# untitled.net
KiCad netlist of a schematic drawn in EAGLE
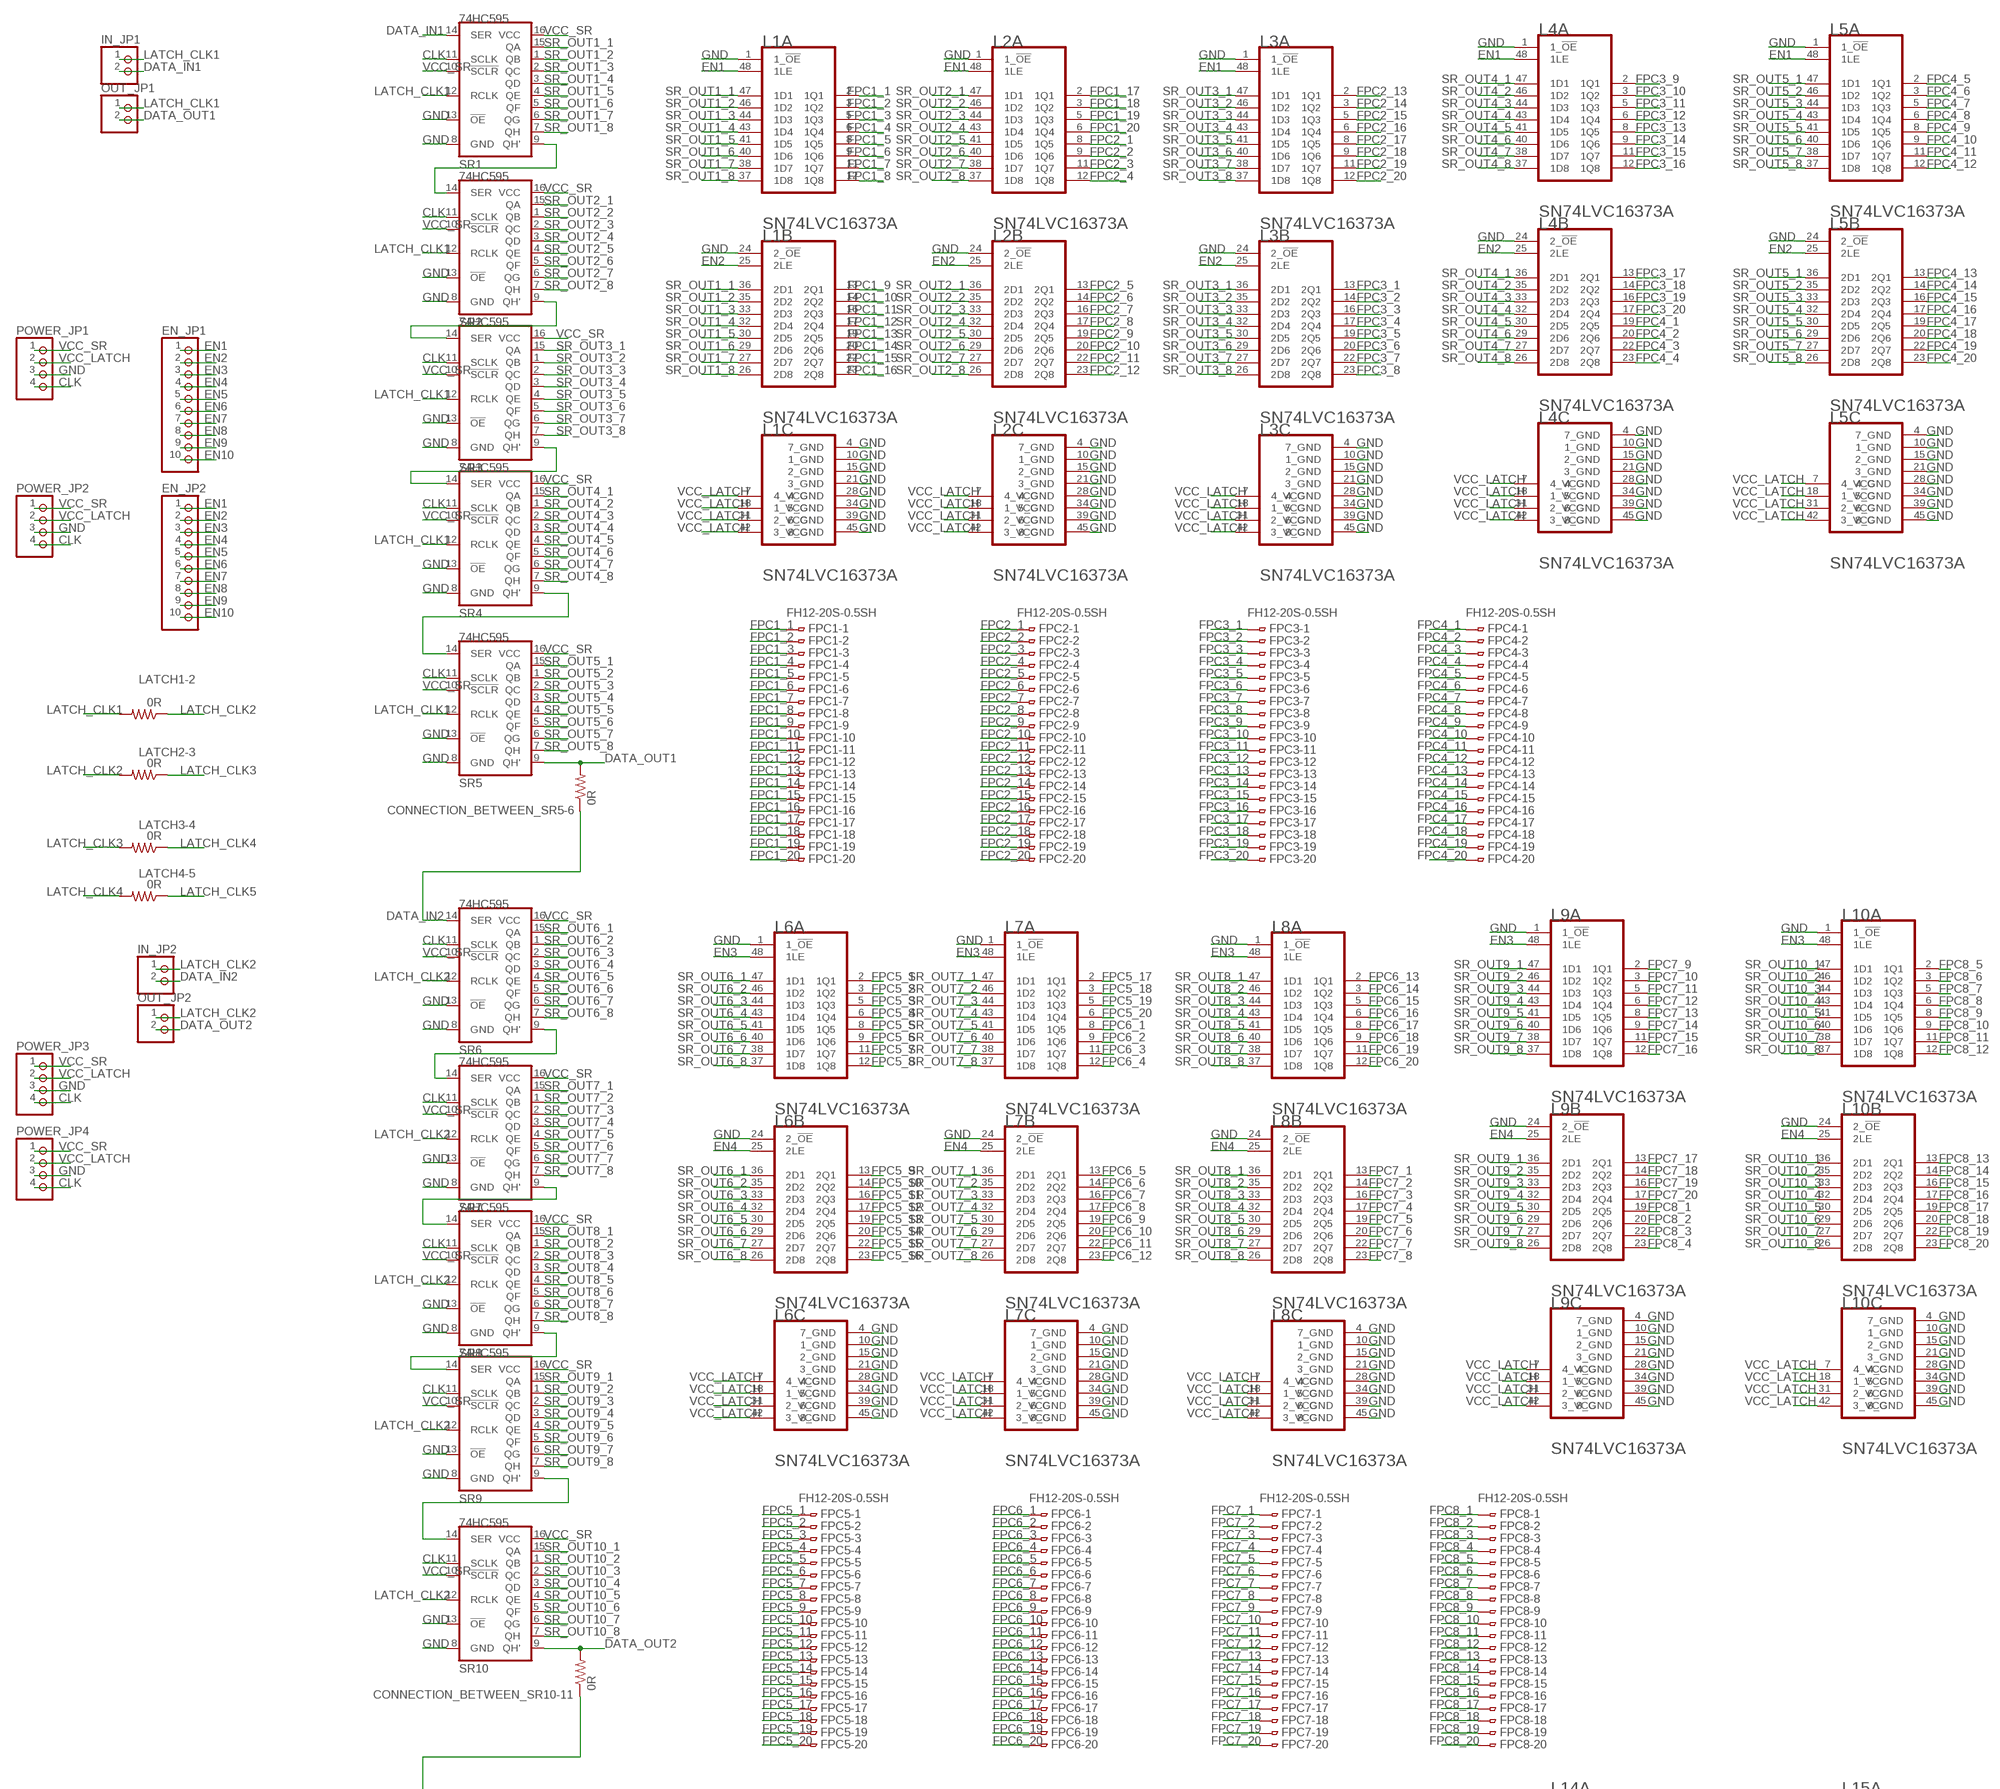
[diagram p0: schematic, sheet 1, part 1 of 3]
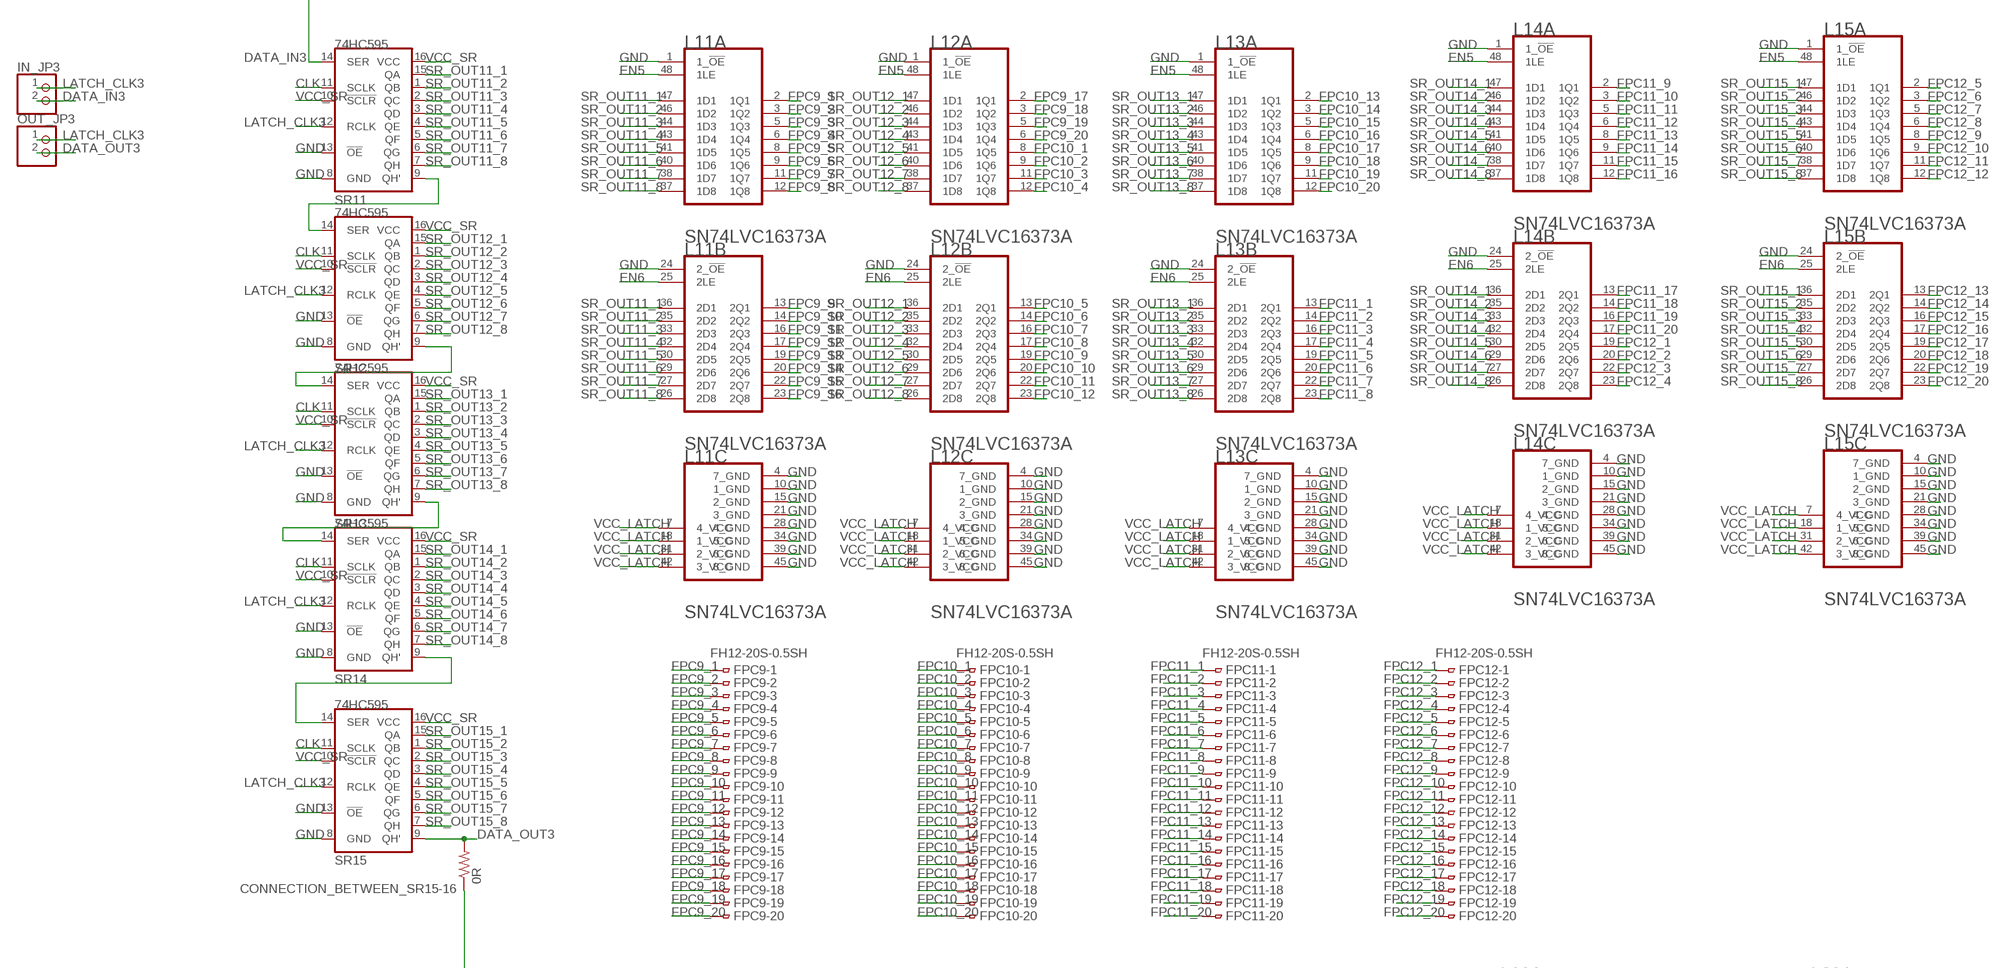
[diagram p1: schematic, sheet 1, part 2 of 3]
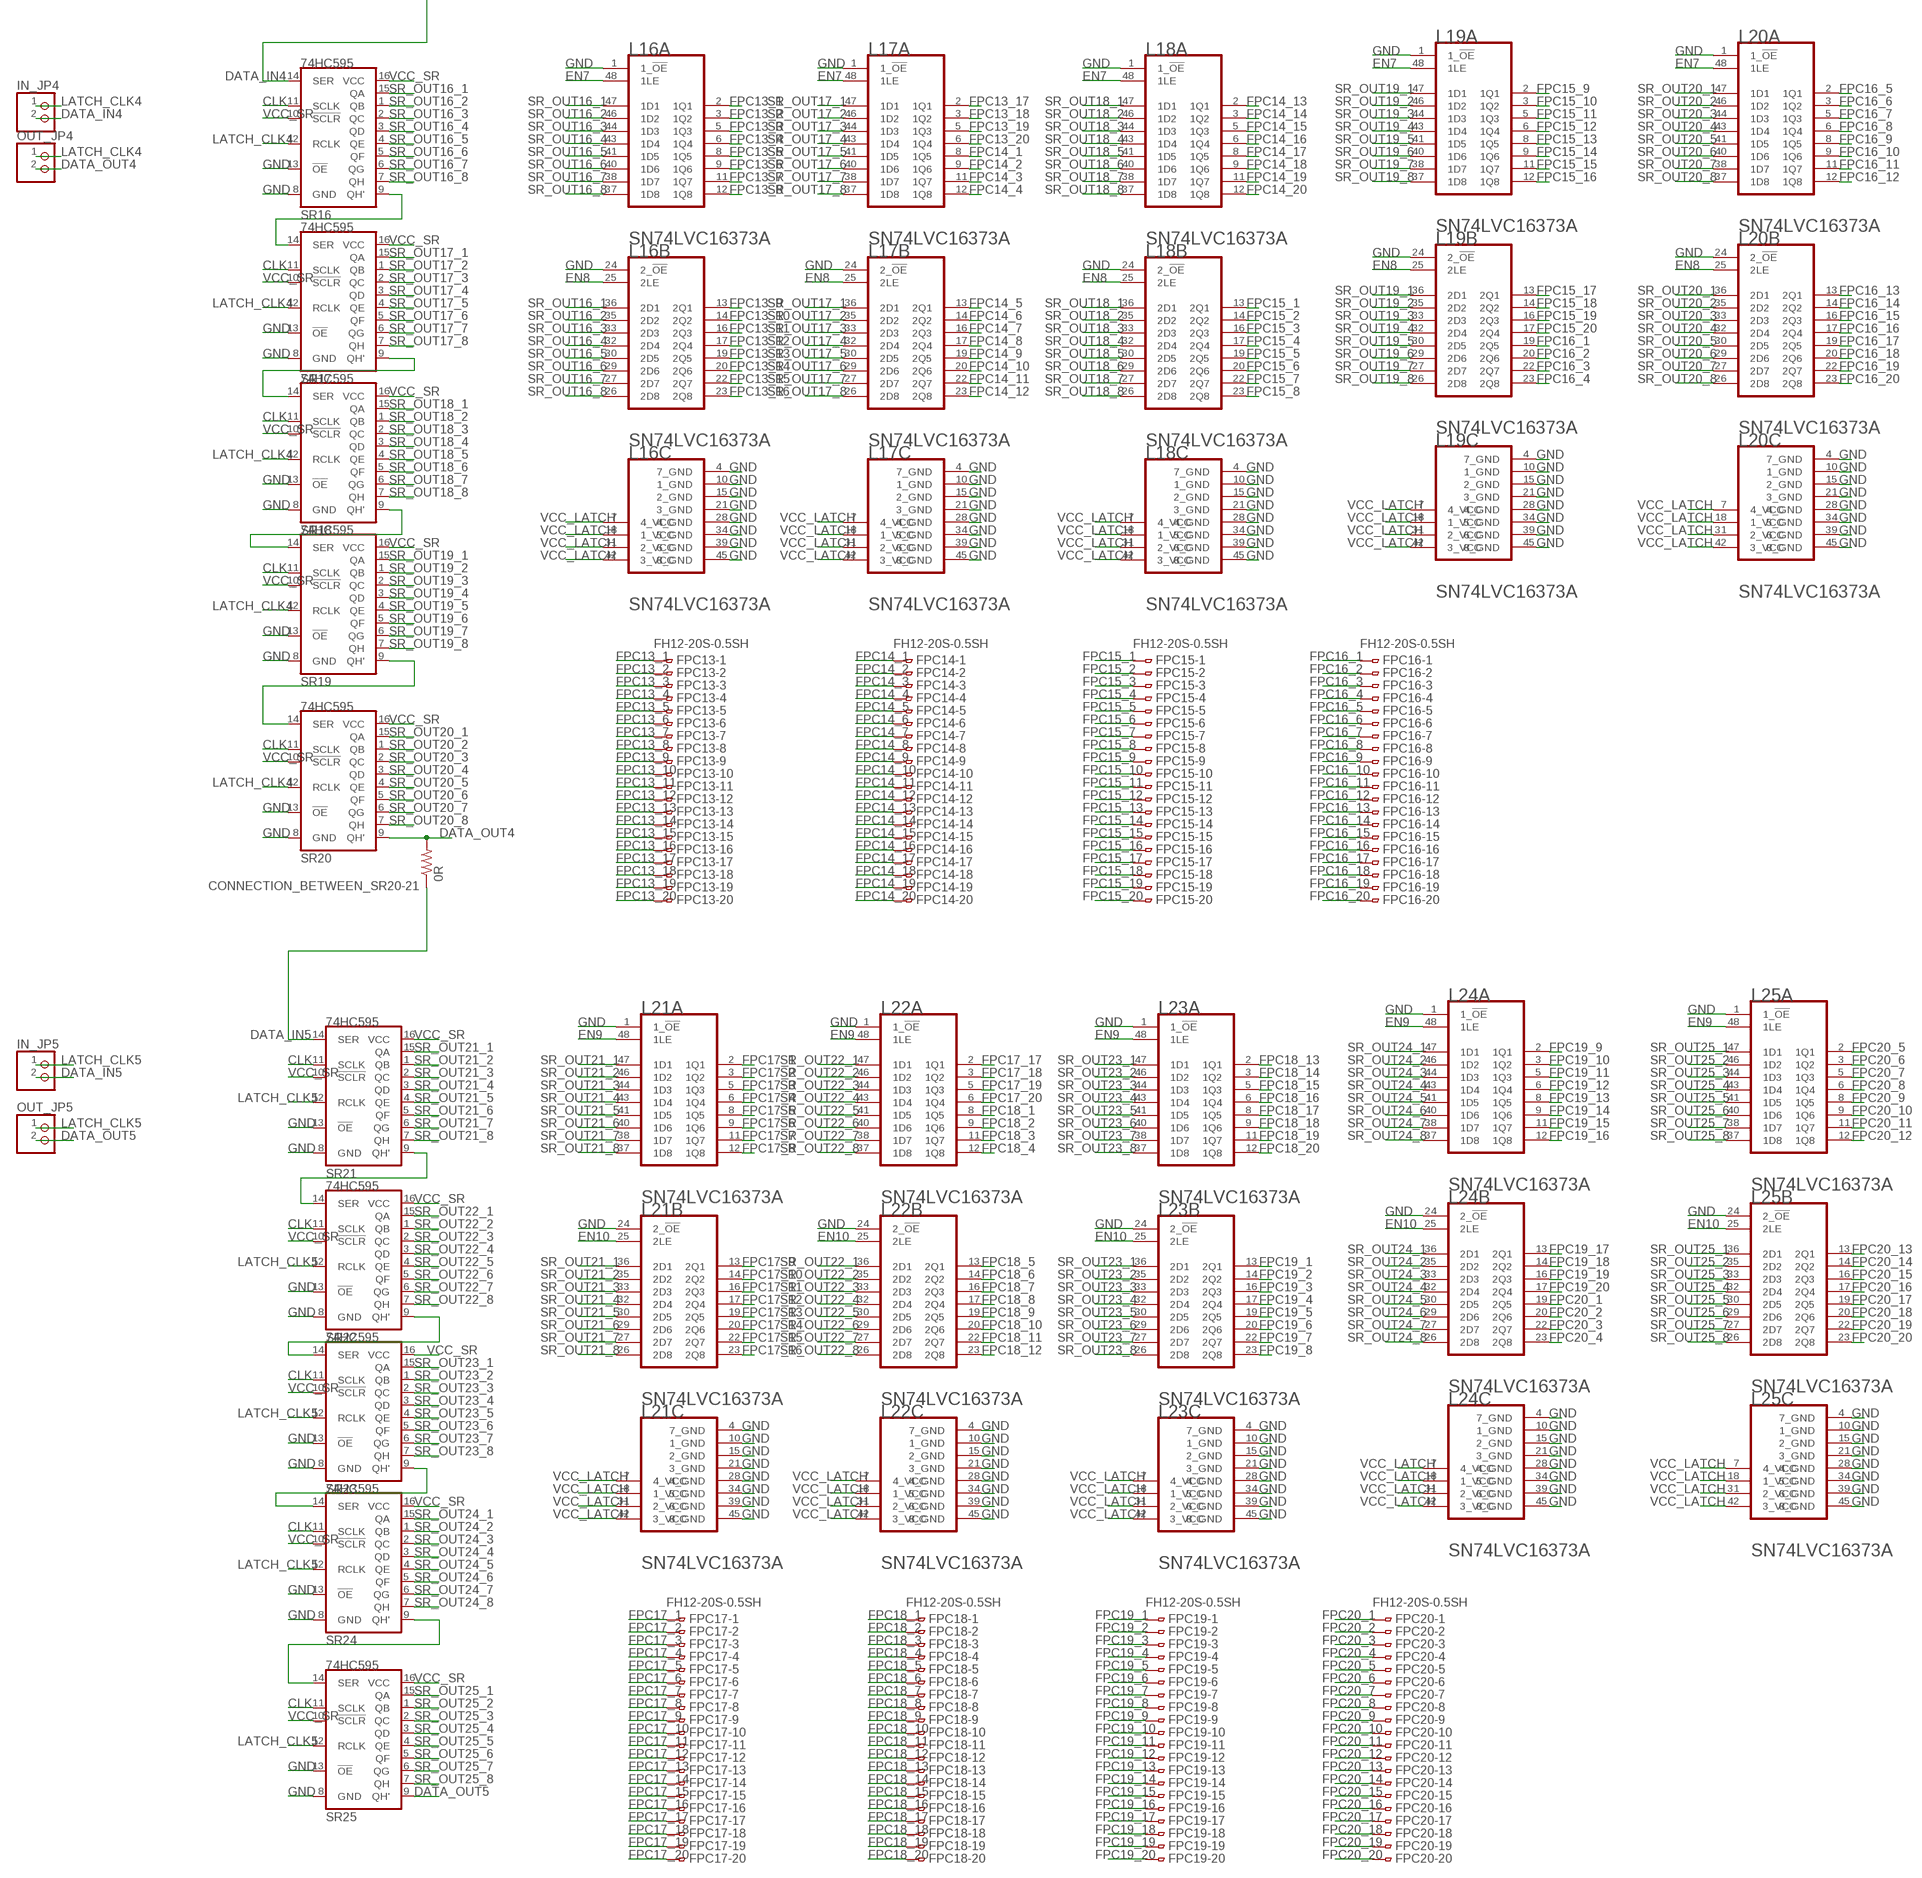
[diagram p2: schematic, sheet 1, part 3 of 3]

(export (version "E")
  (design (tool "Eeschema 10.0.6"))
  (components
    (comp (ref "CONNECTION_BETWEEN_SR5-6")
      (value "0R")
      (footprint "eagle-import:M0805")
      (libsource (lib "eagle-import") (part "R-US_M0805"))
    )
    (comp (ref "CONNECTION_BETWEEN_SR10-11")
      (value "0R")
      (footprint "eagle-import:M0805")
      (libsource (lib "eagle-import") (part "R-US_M0805"))
    )
    (comp (ref "CONNECTION_BETWEEN_SR15-16")
      (value "0R")
      (footprint "eagle-import:M0805")
      (libsource (lib "eagle-import") (part "R-US_M0805"))
    )
    (comp (ref "CONNECTION_BETWEEN_SR20-21")
      (value "0R")
      (footprint "eagle-import:M0805")
      (libsource (lib "eagle-import") (part "R-US_M0805"))
    )
    (comp (ref "EN_JP1")
      (value "PINHD-1X10")
      (footprint "eagle-import:1X10")
      (libsource (lib "eagle-import") (part "PINHD-1X10"))
    )
    (comp (ref "EN_JP2")
      (value "PINHD-1X10")
      (footprint "eagle-import:1X10")
      (libsource (lib "eagle-import") (part "PINHD-1X10"))
    )
    (comp (ref "FPC1")
      (value "FH12-20S-0.5SH")
      (footprint "eagle-import:FH12-20S-0.5SH")
      (fields (field (name "MPN") "FH12-20S-0.5SH(55)"))
      (libsource (lib "eagle-import") (part "FH12-20S-0.5SH"))
    )
    (comp (ref "FPC2")
      (value "FH12-20S-0.5SH")
      (footprint "eagle-import:FH12-20S-0.5SH")
      (fields (field (name "MPN") "FH12-20S-0.5SH(55)"))
      (libsource (lib "eagle-import") (part "FH12-20S-0.5SH"))
    )
    (comp (ref "FPC3")
      (value "FH12-20S-0.5SH")
      (footprint "eagle-import:FH12-20S-0.5SH")
      (fields (field (name "MPN") "FH12-20S-0.5SH(55)"))
      (libsource (lib "eagle-import") (part "FH12-20S-0.5SH"))
    )
    (comp (ref "FPC4")
      (value "FH12-20S-0.5SH")
      (footprint "eagle-import:FH12-20S-0.5SH")
      (fields (field (name "MPN") "FH12-20S-0.5SH(55)"))
      (libsource (lib "eagle-import") (part "FH12-20S-0.5SH"))
    )
    (comp (ref "FPC5")
      (value "FH12-20S-0.5SH")
      (footprint "eagle-import:FH12-20S-0.5SH")
      (fields (field (name "MPN") "FH12-20S-0.5SH(55)"))
      (libsource (lib "eagle-import") (part "FH12-20S-0.5SH"))
    )
    (comp (ref "FPC6")
      (value "FH12-20S-0.5SH")
      (footprint "eagle-import:FH12-20S-0.5SH")
      (fields (field (name "MPN") "FH12-20S-0.5SH(55)"))
      (libsource (lib "eagle-import") (part "FH12-20S-0.5SH"))
    )
    (comp (ref "FPC7")
      (value "FH12-20S-0.5SH")
      (footprint "eagle-import:FH12-20S-0.5SH")
      (fields (field (name "MPN") "FH12-20S-0.5SH(55)"))
      (libsource (lib "eagle-import") (part "FH12-20S-0.5SH"))
    )
    (comp (ref "FPC8")
      (value "FH12-20S-0.5SH")
      (footprint "eagle-import:FH12-20S-0.5SH")
      (fields (field (name "MPN") "FH12-20S-0.5SH(55)"))
      (libsource (lib "eagle-import") (part "FH12-20S-0.5SH"))
    )
    (comp (ref "FPC9")
      (value "FH12-20S-0.5SH")
      (footprint "eagle-import:FH12-20S-0.5SH")
      (fields (field (name "MPN") "FH12-20S-0.5SH(55)"))
      (libsource (lib "eagle-import") (part "FH12-20S-0.5SH"))
    )
    (comp (ref "FPC10")
      (value "FH12-20S-0.5SH")
      (footprint "eagle-import:FH12-20S-0.5SH")
      (fields (field (name "MPN") "FH12-20S-0.5SH(55)"))
      (libsource (lib "eagle-import") (part "FH12-20S-0.5SH"))
    )
    (comp (ref "FPC11")
      (value "FH12-20S-0.5SH")
      (footprint "eagle-import:FH12-20S-0.5SH")
      (fields (field (name "MPN") "FH12-20S-0.5SH(55)"))
      (libsource (lib "eagle-import") (part "FH12-20S-0.5SH"))
    )
    (comp (ref "FPC12")
      (value "FH12-20S-0.5SH")
      (footprint "eagle-import:FH12-20S-0.5SH")
      (fields (field (name "MPN") "FH12-20S-0.5SH(55)"))
      (libsource (lib "eagle-import") (part "FH12-20S-0.5SH"))
    )
    (comp (ref "FPC13")
      (value "FH12-20S-0.5SH")
      (footprint "eagle-import:FH12-20S-0.5SH")
      (fields (field (name "MPN") "FH12-20S-0.5SH(55)"))
      (libsource (lib "eagle-import") (part "FH12-20S-0.5SH"))
    )
    (comp (ref "FPC14")
      (value "FH12-20S-0.5SH")
      (footprint "eagle-import:FH12-20S-0.5SH")
      (fields (field (name "MPN") "FH12-20S-0.5SH(55)"))
      (libsource (lib "eagle-import") (part "FH12-20S-0.5SH"))
    )
    (comp (ref "FPC15")
      (value "FH12-20S-0.5SH")
      (footprint "eagle-import:FH12-20S-0.5SH")
      (fields (field (name "MPN") "FH12-20S-0.5SH(55)"))
      (libsource (lib "eagle-import") (part "FH12-20S-0.5SH"))
    )
    (comp (ref "FPC16")
      (value "FH12-20S-0.5SH")
      (footprint "eagle-import:FH12-20S-0.5SH")
      (fields (field (name "MPN") "FH12-20S-0.5SH(55)"))
      (libsource (lib "eagle-import") (part "FH12-20S-0.5SH"))
    )
    (comp (ref "FPC17")
      (value "FH12-20S-0.5SH")
      (footprint "eagle-import:FH12-20S-0.5SH")
      (fields (field (name "MPN") "FH12-20S-0.5SH(55)"))
      (libsource (lib "eagle-import") (part "FH12-20S-0.5SH"))
    )
    (comp (ref "FPC18")
      (value "FH12-20S-0.5SH")
      (footprint "eagle-import:FH12-20S-0.5SH")
      (fields (field (name "MPN") "FH12-20S-0.5SH(55)"))
      (libsource (lib "eagle-import") (part "FH12-20S-0.5SH"))
    )
    (comp (ref "FPC19")
      (value "FH12-20S-0.5SH")
      (footprint "eagle-import:FH12-20S-0.5SH")
      (fields (field (name "MPN") "FH12-20S-0.5SH(55)"))
      (libsource (lib "eagle-import") (part "FH12-20S-0.5SH"))
    )
    (comp (ref "FPC20")
      (value "FH12-20S-0.5SH")
      (footprint "eagle-import:FH12-20S-0.5SH")
      (fields (field (name "MPN") "FH12-20S-0.5SH(55)"))
      (libsource (lib "eagle-import") (part "FH12-20S-0.5SH"))
    )
    (comp (ref "IN_JP1")
      (value "PINHD-1X2")
      (footprint "eagle-import:1X02")
      (libsource (lib "eagle-import") (part "PINHD-1X2"))
    )
    (comp (ref "IN_JP2")
      (value "PINHD-1X2")
      (footprint "eagle-import:1X02")
      (libsource (lib "eagle-import") (part "PINHD-1X2"))
    )
    (comp (ref "IN_JP3")
      (value "PINHD-1X2")
      (footprint "eagle-import:1X02")
      (libsource (lib "eagle-import") (part "PINHD-1X2"))
    )
    (comp (ref "IN_JP4")
      (value "PINHD-1X2")
      (footprint "eagle-import:1X02")
      (libsource (lib "eagle-import") (part "PINHD-1X2"))
    )
    (comp (ref "IN_JP5")
      (value "PINHD-1X2")
      (footprint "eagle-import:1X02")
      (libsource (lib "eagle-import") (part "PINHD-1X2"))
    )
    (comp (ref "L1")
      (value "TEXAS_INSTRUMENTS_SN74LVC16373ATEXAS_INSTRUMENTS_SN74LVC16373A_0_2")
      (footprint "eagle-import:TEXAS_INSTRUMENTS_SN74LVC16373A_2")
      (fields (field (name "MF") "Texas Instruments") (field (name "MPN") "SN74LVC16373A"))
      (libsource (lib "eagle-import") (part "TEXAS_INSTRUMENTS_SN74LVC16373ATEXAS_INSTRUMENTS_SN74LVC16373A_0_2"))
    )
    (comp (ref "L2")
      (value "TEXAS_INSTRUMENTS_SN74LVC16373ATEXAS_INSTRUMENTS_SN74LVC16373A_0_2")
      (footprint "eagle-import:TEXAS_INSTRUMENTS_SN74LVC16373A_2")
      (fields (field (name "MF") "Texas Instruments") (field (name "MPN") "SN74LVC16373A"))
      (libsource (lib "eagle-import") (part "TEXAS_INSTRUMENTS_SN74LVC16373ATEXAS_INSTRUMENTS_SN74LVC16373A_0_2"))
    )
    (comp (ref "L3")
      (value "TEXAS_INSTRUMENTS_SN74LVC16373ATEXAS_INSTRUMENTS_SN74LVC16373A_0_2")
      (footprint "eagle-import:TEXAS_INSTRUMENTS_SN74LVC16373A_2")
      (fields (field (name "MF") "Texas Instruments") (field (name "MPN") "SN74LVC16373A"))
      (libsource (lib "eagle-import") (part "TEXAS_INSTRUMENTS_SN74LVC16373ATEXAS_INSTRUMENTS_SN74LVC16373A_0_2"))
    )
    (comp (ref "L4")
      (value "TEXAS_INSTRUMENTS_SN74LVC16373ATEXAS_INSTRUMENTS_SN74LVC16373A_0_2")
      (footprint "eagle-import:TEXAS_INSTRUMENTS_SN74LVC16373A_2")
      (fields (field (name "MF") "Texas Instruments") (field (name "MPN") "SN74LVC16373A"))
      (libsource (lib "eagle-import") (part "TEXAS_INSTRUMENTS_SN74LVC16373ATEXAS_INSTRUMENTS_SN74LVC16373A_0_2"))
    )
    (comp (ref "L5")
      (value "TEXAS_INSTRUMENTS_SN74LVC16373ATEXAS_INSTRUMENTS_SN74LVC16373A_0_2")
      (footprint "eagle-import:TEXAS_INSTRUMENTS_SN74LVC16373A_2")
      (fields (field (name "MF") "Texas Instruments") (field (name "MPN") "SN74LVC16373A"))
      (libsource (lib "eagle-import") (part "TEXAS_INSTRUMENTS_SN74LVC16373ATEXAS_INSTRUMENTS_SN74LVC16373A_0_2"))
    )
    (comp (ref "L6")
      (value "TEXAS_INSTRUMENTS_SN74LVC16373ATEXAS_INSTRUMENTS_SN74LVC16373A_0_2")
      (footprint "eagle-import:TEXAS_INSTRUMENTS_SN74LVC16373A_2")
      (fields (field (name "MF") "Texas Instruments") (field (name "MPN") "SN74LVC16373A"))
      (libsource (lib "eagle-import") (part "TEXAS_INSTRUMENTS_SN74LVC16373ATEXAS_INSTRUMENTS_SN74LVC16373A_0_2"))
    )
    (comp (ref "L7")
      (value "TEXAS_INSTRUMENTS_SN74LVC16373ATEXAS_INSTRUMENTS_SN74LVC16373A_0_2")
      (footprint "eagle-import:TEXAS_INSTRUMENTS_SN74LVC16373A_2")
      (fields (field (name "MF") "Texas Instruments") (field (name "MPN") "SN74LVC16373A"))
      (libsource (lib "eagle-import") (part "TEXAS_INSTRUMENTS_SN74LVC16373ATEXAS_INSTRUMENTS_SN74LVC16373A_0_2"))
    )
    (comp (ref "L8")
      (value "TEXAS_INSTRUMENTS_SN74LVC16373ATEXAS_INSTRUMENTS_SN74LVC16373A_0_2")
      (footprint "eagle-import:TEXAS_INSTRUMENTS_SN74LVC16373A_2")
      (fields (field (name "MF") "Texas Instruments") (field (name "MPN") "SN74LVC16373A"))
      (libsource (lib "eagle-import") (part "TEXAS_INSTRUMENTS_SN74LVC16373ATEXAS_INSTRUMENTS_SN74LVC16373A_0_2"))
    )
    (comp (ref "L9")
      (value "TEXAS_INSTRUMENTS_SN74LVC16373ATEXAS_INSTRUMENTS_SN74LVC16373A_0_2")
      (footprint "eagle-import:TEXAS_INSTRUMENTS_SN74LVC16373A_2")
      (fields (field (name "MF") "Texas Instruments") (field (name "MPN") "SN74LVC16373A"))
      (libsource (lib "eagle-import") (part "TEXAS_INSTRUMENTS_SN74LVC16373ATEXAS_INSTRUMENTS_SN74LVC16373A_0_2"))
    )
    (comp (ref "L10")
      (value "TEXAS_INSTRUMENTS_SN74LVC16373ATEXAS_INSTRUMENTS_SN74LVC16373A_0_2")
      (footprint "eagle-import:TEXAS_INSTRUMENTS_SN74LVC16373A_2")
      (fields (field (name "MF") "Texas Instruments") (field (name "MPN") "SN74LVC16373A"))
      (libsource (lib "eagle-import") (part "TEXAS_INSTRUMENTS_SN74LVC16373ATEXAS_INSTRUMENTS_SN74LVC16373A_0_2"))
    )
    (comp (ref "L11")
      (value "TEXAS_INSTRUMENTS_SN74LVC16373ATEXAS_INSTRUMENTS_SN74LVC16373A_0_2")
      (footprint "eagle-import:TEXAS_INSTRUMENTS_SN74LVC16373A_2")
      (fields (field (name "MF") "Texas Instruments") (field (name "MPN") "SN74LVC16373A"))
      (libsource (lib "eagle-import") (part "TEXAS_INSTRUMENTS_SN74LVC16373ATEXAS_INSTRUMENTS_SN74LVC16373A_0_2"))
    )
    (comp (ref "L12")
      (value "TEXAS_INSTRUMENTS_SN74LVC16373ATEXAS_INSTRUMENTS_SN74LVC16373A_0_2")
      (footprint "eagle-import:TEXAS_INSTRUMENTS_SN74LVC16373A_2")
      (fields (field (name "MF") "Texas Instruments") (field (name "MPN") "SN74LVC16373A"))
      (libsource (lib "eagle-import") (part "TEXAS_INSTRUMENTS_SN74LVC16373ATEXAS_INSTRUMENTS_SN74LVC16373A_0_2"))
    )
    (comp (ref "L13")
      (value "TEXAS_INSTRUMENTS_SN74LVC16373ATEXAS_INSTRUMENTS_SN74LVC16373A_0_2")
      (footprint "eagle-import:TEXAS_INSTRUMENTS_SN74LVC16373A_2")
      (fields (field (name "MF") "Texas Instruments") (field (name "MPN") "SN74LVC16373A"))
      (libsource (lib "eagle-import") (part "TEXAS_INSTRUMENTS_SN74LVC16373ATEXAS_INSTRUMENTS_SN74LVC16373A_0_2"))
    )
    (comp (ref "L14")
      (value "TEXAS_INSTRUMENTS_SN74LVC16373ATEXAS_INSTRUMENTS_SN74LVC16373A_0_2")
      (footprint "eagle-import:TEXAS_INSTRUMENTS_SN74LVC16373A_2")
      (fields (field (name "MF") "Texas Instruments") (field (name "MPN") "SN74LVC16373A"))
      (libsource (lib "eagle-import") (part "TEXAS_INSTRUMENTS_SN74LVC16373ATEXAS_INSTRUMENTS_SN74LVC16373A_0_2"))
    )
    (comp (ref "L15")
      (value "TEXAS_INSTRUMENTS_SN74LVC16373ATEXAS_INSTRUMENTS_SN74LVC16373A_0_2")
      (footprint "eagle-import:TEXAS_INSTRUMENTS_SN74LVC16373A_2")
      (fields (field (name "MF") "Texas Instruments") (field (name "MPN") "SN74LVC16373A"))
      (libsource (lib "eagle-import") (part "TEXAS_INSTRUMENTS_SN74LVC16373ATEXAS_INSTRUMENTS_SN74LVC16373A_0_2"))
    )
    (comp (ref "L16")
      (value "TEXAS_INSTRUMENTS_SN74LVC16373ATEXAS_INSTRUMENTS_SN74LVC16373A_0_2")
      (footprint "eagle-import:TEXAS_INSTRUMENTS_SN74LVC16373A_2")
      (fields (field (name "MF") "Texas Instruments") (field (name "MPN") "SN74LVC16373A"))
      (libsource (lib "eagle-import") (part "TEXAS_INSTRUMENTS_SN74LVC16373ATEXAS_INSTRUMENTS_SN74LVC16373A_0_2"))
    )
    (comp (ref "L17")
      (value "TEXAS_INSTRUMENTS_SN74LVC16373ATEXAS_INSTRUMENTS_SN74LVC16373A_0_2")
      (footprint "eagle-import:TEXAS_INSTRUMENTS_SN74LVC16373A_2")
      (fields (field (name "MF") "Texas Instruments") (field (name "MPN") "SN74LVC16373A"))
      (libsource (lib "eagle-import") (part "TEXAS_INSTRUMENTS_SN74LVC16373ATEXAS_INSTRUMENTS_SN74LVC16373A_0_2"))
    )
    (comp (ref "L18")
      (value "TEXAS_INSTRUMENTS_SN74LVC16373ATEXAS_INSTRUMENTS_SN74LVC16373A_0_2")
      (footprint "eagle-import:TEXAS_INSTRUMENTS_SN74LVC16373A_2")
      (fields (field (name "MF") "Texas Instruments") (field (name "MPN") "SN74LVC16373A"))
      (libsource (lib "eagle-import") (part "TEXAS_INSTRUMENTS_SN74LVC16373ATEXAS_INSTRUMENTS_SN74LVC16373A_0_2"))
    )
    (comp (ref "L19")
      (value "TEXAS_INSTRUMENTS_SN74LVC16373ATEXAS_INSTRUMENTS_SN74LVC16373A_0_2")
      (footprint "eagle-import:TEXAS_INSTRUMENTS_SN74LVC16373A_2")
      (fields (field (name "MF") "Texas Instruments") (field (name "MPN") "SN74LVC16373A"))
      (libsource (lib "eagle-import") (part "TEXAS_INSTRUMENTS_SN74LVC16373ATEXAS_INSTRUMENTS_SN74LVC16373A_0_2"))
    )
    (comp (ref "L20")
      (value "TEXAS_INSTRUMENTS_SN74LVC16373ATEXAS_INSTRUMENTS_SN74LVC16373A_0_2")
      (footprint "eagle-import:TEXAS_INSTRUMENTS_SN74LVC16373A_2")
      (fields (field (name "MF") "Texas Instruments") (field (name "MPN") "SN74LVC16373A"))
      (libsource (lib "eagle-import") (part "TEXAS_INSTRUMENTS_SN74LVC16373ATEXAS_INSTRUMENTS_SN74LVC16373A_0_2"))
    )
    (comp (ref "L21")
      (value "TEXAS_INSTRUMENTS_SN74LVC16373ATEXAS_INSTRUMENTS_SN74LVC16373A_0_2")
      (footprint "eagle-import:TEXAS_INSTRUMENTS_SN74LVC16373A_2")
      (fields (field (name "MF") "Texas Instruments") (field (name "MPN") "SN74LVC16373A"))
      (libsource (lib "eagle-import") (part "TEXAS_INSTRUMENTS_SN74LVC16373ATEXAS_INSTRUMENTS_SN74LVC16373A_0_2"))
    )
    (comp (ref "L22")
      (value "TEXAS_INSTRUMENTS_SN74LVC16373ATEXAS_INSTRUMENTS_SN74LVC16373A_0_2")
      (footprint "eagle-import:TEXAS_INSTRUMENTS_SN74LVC16373A_2")
      (fields (field (name "MF") "Texas Instruments") (field (name "MPN") "SN74LVC16373A"))
      (libsource (lib "eagle-import") (part "TEXAS_INSTRUMENTS_SN74LVC16373ATEXAS_INSTRUMENTS_SN74LVC16373A_0_2"))
    )
    (comp (ref "L23")
      (value "TEXAS_INSTRUMENTS_SN74LVC16373ATEXAS_INSTRUMENTS_SN74LVC16373A_0_2")
      (footprint "eagle-import:TEXAS_INSTRUMENTS_SN74LVC16373A_2")
      (fields (field (name "MF") "Texas Instruments") (field (name "MPN") "SN74LVC16373A"))
      (libsource (lib "eagle-import") (part "TEXAS_INSTRUMENTS_SN74LVC16373ATEXAS_INSTRUMENTS_SN74LVC16373A_0_2"))
    )
    (comp (ref "L24")
      (value "TEXAS_INSTRUMENTS_SN74LVC16373ATEXAS_INSTRUMENTS_SN74LVC16373A_0_2")
      (footprint "eagle-import:TEXAS_INSTRUMENTS_SN74LVC16373A_2")
      (fields (field (name "MF") "Texas Instruments") (field (name "MPN") "SN74LVC16373A"))
      (libsource (lib "eagle-import") (part "TEXAS_INSTRUMENTS_SN74LVC16373ATEXAS_INSTRUMENTS_SN74LVC16373A_0_2"))
    )
    (comp (ref "L25")
      (value "TEXAS_INSTRUMENTS_SN74LVC16373ATEXAS_INSTRUMENTS_SN74LVC16373A_0_2")
      (footprint "eagle-import:TEXAS_INSTRUMENTS_SN74LVC16373A_2")
      (fields (field (name "MF") "Texas Instruments") (field (name "MPN") "SN74LVC16373A"))
      (libsource (lib "eagle-import") (part "TEXAS_INSTRUMENTS_SN74LVC16373ATEXAS_INSTRUMENTS_SN74LVC16373A_0_2"))
    )
    (comp (ref "LATCH1-2")
      (value "0R")
      (footprint "eagle-import:M0805")
      (libsource (lib "eagle-import") (part "R-US_M0805"))
    )
    (comp (ref "LATCH2-3")
      (value "0R")
      (footprint "eagle-import:M0805")
      (libsource (lib "eagle-import") (part "R-US_M0805"))
    )
    (comp (ref "LATCH3-4")
      (value "0R")
      (footprint "eagle-import:M0805")
      (libsource (lib "eagle-import") (part "R-US_M0805"))
    )
    (comp (ref "LATCH4-5")
      (value "0R")
      (footprint "eagle-import:M0805")
      (libsource (lib "eagle-import") (part "R-US_M0805"))
    )
    (comp (ref "OUT_JP1")
      (value "PINHD-1X2")
      (footprint "eagle-import:1X02")
      (libsource (lib "eagle-import") (part "PINHD-1X2"))
    )
    (comp (ref "OUT_JP2")
      (value "PINHD-1X2")
      (footprint "eagle-import:1X02")
      (libsource (lib "eagle-import") (part "PINHD-1X2"))
    )
    (comp (ref "OUT_JP3")
      (value "PINHD-1X2")
      (footprint "eagle-import:1X02")
      (libsource (lib "eagle-import") (part "PINHD-1X2"))
    )
    (comp (ref "OUT_JP4")
      (value "PINHD-1X2")
      (footprint "eagle-import:1X02")
      (libsource (lib "eagle-import") (part "PINHD-1X2"))
    )
    (comp (ref "OUT_JP5")
      (value "PINHD-1X2")
      (footprint "eagle-import:1X02")
      (libsource (lib "eagle-import") (part "PINHD-1X2"))
    )
    (comp (ref "POWER_JP1")
      (value "PINHD-1X4")
      (footprint "eagle-import:1X04")
      (libsource (lib "eagle-import") (part "PINHD-1X4"))
    )
    (comp (ref "POWER_JP2")
      (value "PINHD-1X4")
      (footprint "eagle-import:1X04")
      (libsource (lib "eagle-import") (part "PINHD-1X4"))
    )
    (comp (ref "POWER_JP3")
      (value "PINHD-1X4")
      (footprint "eagle-import:1X04")
      (libsource (lib "eagle-import") (part "PINHD-1X4"))
    )
    (comp (ref "POWER_JP4")
      (value "PINHD-1X4")
      (footprint "eagle-import:1X04")
      (libsource (lib "eagle-import") (part "PINHD-1X4"))
    )
    (comp (ref "SR1")
      (value "74HC595")
      (footprint "eagle-import:SO16")
      (fields (field (name "MF") "Nexperia"))
      (libsource (lib "eagle-import") (part "74HC595"))
    )
    (comp (ref "SR2")
      (value "74HC595")
      (footprint "eagle-import:SO16")
      (fields (field (name "MF") "Nexperia"))
      (libsource (lib "eagle-import") (part "74HC595"))
    )
    (comp (ref "SR3")
      (value "74HC595")
      (footprint "eagle-import:SO16")
      (fields (field (name "MF") "Nexperia"))
      (libsource (lib "eagle-import") (part "74HC595"))
    )
    (comp (ref "SR4")
      (value "74HC595")
      (footprint "eagle-import:SO16")
      (fields (field (name "MF") "Nexperia"))
      (libsource (lib "eagle-import") (part "74HC595"))
    )
    (comp (ref "SR5")
      (value "74HC595")
      (footprint "eagle-import:SO16")
      (fields (field (name "MF") "Nexperia"))
      (libsource (lib "eagle-import") (part "74HC595"))
    )
    (comp (ref "SR6")
      (value "74HC595")
      (footprint "eagle-import:SO16")
      (fields (field (name "MF") "Nexperia"))
      (libsource (lib "eagle-import") (part "74HC595"))
    )
    (comp (ref "SR7")
      (value "74HC595")
      (footprint "eagle-import:SO16")
      (fields (field (name "MF") "Nexperia"))
      (libsource (lib "eagle-import") (part "74HC595"))
    )
    (comp (ref "SR8")
      (value "74HC595")
      (footprint "eagle-import:SO16")
      (fields (field (name "MF") "Nexperia"))
      (libsource (lib "eagle-import") (part "74HC595"))
    )
    (comp (ref "SR9")
      (value "74HC595")
      (footprint "eagle-import:SO16")
      (fields (field (name "MF") "Nexperia"))
      (libsource (lib "eagle-import") (part "74HC595"))
    )
    (comp (ref "SR10")
      (value "74HC595")
      (footprint "eagle-import:SO16")
      (fields (field (name "MF") "Nexperia"))
      (libsource (lib "eagle-import") (part "74HC595"))
    )
    (comp (ref "SR11")
      (value "74HC595")
      (footprint "eagle-import:SO16")
      (fields (field (name "MF") "Nexperia"))
      (libsource (lib "eagle-import") (part "74HC595"))
    )
    (comp (ref "SR12")
      (value "74HC595")
      (footprint "eagle-import:SO16")
      (fields (field (name "MF") "Nexperia"))
      (libsource (lib "eagle-import") (part "74HC595"))
    )
    (comp (ref "SR13")
      (value "74HC595")
      (footprint "eagle-import:SO16")
      (fields (field (name "MF") "Nexperia"))
      (libsource (lib "eagle-import") (part "74HC595"))
    )
    (comp (ref "SR14")
      (value "74HC595")
      (footprint "eagle-import:SO16")
      (fields (field (name "MF") "Nexperia"))
      (libsource (lib "eagle-import") (part "74HC595"))
    )
    (comp (ref "SR15")
      (value "74HC595")
      (footprint "eagle-import:SO16")
      (fields (field (name "MF") "Nexperia"))
      (libsource (lib "eagle-import") (part "74HC595"))
    )
    (comp (ref "SR16")
      (value "74HC595")
      (footprint "eagle-import:SO16")
      (fields (field (name "MF") "Nexperia"))
      (libsource (lib "eagle-import") (part "74HC595"))
    )
    (comp (ref "SR17")
      (value "74HC595")
      (footprint "eagle-import:SO16")
      (fields (field (name "MF") "Nexperia"))
      (libsource (lib "eagle-import") (part "74HC595"))
    )
    (comp (ref "SR18")
      (value "74HC595")
      (footprint "eagle-import:SO16")
      (fields (field (name "MF") "Nexperia"))
      (libsource (lib "eagle-import") (part "74HC595"))
    )
    (comp (ref "SR19")
      (value "74HC595")
      (footprint "eagle-import:SO16")
      (fields (field (name "MF") "Nexperia"))
      (libsource (lib "eagle-import") (part "74HC595"))
    )
    (comp (ref "SR20")
      (value "74HC595")
      (footprint "eagle-import:SO16")
      (fields (field (name "MF") "Nexperia"))
      (libsource (lib "eagle-import") (part "74HC595"))
    )
    (comp (ref "SR21")
      (value "74HC595")
      (footprint "eagle-import:SO16")
      (fields (field (name "MF") "Nexperia"))
      (libsource (lib "eagle-import") (part "74HC595"))
    )
    (comp (ref "SR22")
      (value "74HC595")
      (footprint "eagle-import:SO16")
      (fields (field (name "MF") "Nexperia"))
      (libsource (lib "eagle-import") (part "74HC595"))
    )
    (comp (ref "SR23")
      (value "74HC595")
      (footprint "eagle-import:SO16")
      (fields (field (name "MF") "Nexperia"))
      (libsource (lib "eagle-import") (part "74HC595"))
    )
    (comp (ref "SR24")
      (value "74HC595")
      (footprint "eagle-import:SO16")
      (fields (field (name "MF") "Nexperia"))
      (libsource (lib "eagle-import") (part "74HC595"))
    )
    (comp (ref "SR25")
      (value "74HC595")
      (footprint "eagle-import:SO16")
      (fields (field (name "MF") "Nexperia"))
      (libsource (lib "eagle-import") (part "74HC595"))
    )
  )
  (nets
    (net (code "1") (name "/CLK") (class "Default")
      (node (ref "POWER_JP1") (pin "4") (pinfunction "4_4") (pintype "passive"))
      (node (ref "POWER_JP2") (pin "4") (pinfunction "4_4") (pintype "passive"))
      (node (ref "POWER_JP3") (pin "4") (pinfunction "4_4") (pintype "passive"))
      (node (ref "POWER_JP4") (pin "4") (pinfunction "4_4") (pintype "passive"))
      (node (ref "SR1") (pin "11") (pinfunction "SCLK_11") (pintype "input"))
      (node (ref "SR10") (pin "11") (pinfunction "SCLK_11") (pintype "input"))
      (node (ref "SR11") (pin "11") (pinfunction "SCLK_11") (pintype "input"))
      (node (ref "SR12") (pin "11") (pinfunction "SCLK_11") (pintype "input"))
      (node (ref "SR13") (pin "11") (pinfunction "SCLK_11") (pintype "input"))
      (node (ref "SR14") (pin "11") (pinfunction "SCLK_11") (pintype "input"))
      (node (ref "SR15") (pin "11") (pinfunction "SCLK_11") (pintype "input"))
      (node (ref "SR16") (pin "11") (pinfunction "SCLK_11") (pintype "input"))
      (node (ref "SR17") (pin "11") (pinfunction "SCLK_11") (pintype "input"))
      (node (ref "SR18") (pin "11") (pinfunction "SCLK_11") (pintype "input"))
      (node (ref "SR19") (pin "11") (pinfunction "SCLK_11") (pintype "input"))
      (node (ref "SR2") (pin "11") (pinfunction "SCLK_11") (pintype "input"))
      (node (ref "SR20") (pin "11") (pinfunction "SCLK_11") (pintype "input"))
      (node (ref "SR21") (pin "11") (pinfunction "SCLK_11") (pintype "input"))
      (node (ref "SR22") (pin "11") (pinfunction "SCLK_11") (pintype "input"))
      (node (ref "SR23") (pin "11") (pinfunction "SCLK_11") (pintype "input"))
      (node (ref "SR24") (pin "11") (pinfunction "SCLK_11") (pintype "input"))
      (node (ref "SR25") (pin "11") (pinfunction "SCLK_11") (pintype "input"))
      (node (ref "SR3") (pin "11") (pinfunction "SCLK_11") (pintype "input"))
      (node (ref "SR4") (pin "11") (pinfunction "SCLK_11") (pintype "input"))
      (node (ref "SR5") (pin "11") (pinfunction "SCLK_11") (pintype "input"))
      (node (ref "SR6") (pin "11") (pinfunction "SCLK_11") (pintype "input"))
      (node (ref "SR7") (pin "11") (pinfunction "SCLK_11") (pintype "input"))
      (node (ref "SR8") (pin "11") (pinfunction "SCLK_11") (pintype "input"))
      (node (ref "SR9") (pin "11") (pinfunction "SCLK_11") (pintype "input"))
    )
    (net (code "2") (name "/DATA_IN1") (class "Default")
      (node (ref "IN_JP1") (pin "2") (pinfunction "2_2") (pintype "passive"))
      (node (ref "SR1") (pin "14") (pinfunction "SER_14") (pintype "input"))
    )
    (net (code "3") (name "/DATA_IN2") (class "Default")
      (node (ref "CONNECTION_BETWEEN_SR5-6") (pin "1") (pinfunction "1_1") (pintype "passive"))
      (node (ref "IN_JP2") (pin "2") (pinfunction "2_2") (pintype "passive"))
      (node (ref "SR6") (pin "14") (pinfunction "SER_14") (pintype "input"))
    )
    (net (code "4") (name "/DATA_IN3") (class "Default")
      (node (ref "CONNECTION_BETWEEN_SR10-11") (pin "1") (pinfunction "1_1") (pintype "passive"))
      (node (ref "IN_JP3") (pin "2") (pinfunction "2_2") (pintype "passive"))
      (node (ref "SR11") (pin "14") (pinfunction "SER_14") (pintype "input"))
    )
    (net (code "5") (name "/DATA_IN4") (class "Default")
      (node (ref "CONNECTION_BETWEEN_SR15-16") (pin "1") (pinfunction "1_1") (pintype "passive"))
      (node (ref "IN_JP4") (pin "2") (pinfunction "2_2") (pintype "passive"))
      (node (ref "SR16") (pin "14") (pinfunction "SER_14") (pintype "input"))
    )
    (net (code "6") (name "/DATA_IN5") (class "Default")
      (node (ref "CONNECTION_BETWEEN_SR20-21") (pin "1") (pinfunction "1_1") (pintype "passive"))
      (node (ref "IN_JP5") (pin "2") (pinfunction "2_2") (pintype "passive"))
      (node (ref "SR21") (pin "14") (pinfunction "SER_14") (pintype "input"))
    )
    (net (code "7") (name "/DATA_OUT1") (class "Default")
      (node (ref "CONNECTION_BETWEEN_SR5-6") (pin "2") (pinfunction "2_2") (pintype "passive"))
      (node (ref "OUT_JP1") (pin "2") (pinfunction "2_2") (pintype "passive"))
      (node (ref "SR5") (pin "9") (pinfunction "QH'_9") (pintype "tri_state"))
    )
    (net (code "8") (name "/DATA_OUT2") (class "Default")
      (node (ref "CONNECTION_BETWEEN_SR10-11") (pin "2") (pinfunction "2_2") (pintype "passive"))
      (node (ref "OUT_JP2") (pin "2") (pinfunction "2_2") (pintype "passive"))
      (node (ref "SR10") (pin "9") (pinfunction "QH'_9") (pintype "tri_state"))
    )
    (net (code "9") (name "/DATA_OUT3") (class "Default")
      (node (ref "CONNECTION_BETWEEN_SR15-16") (pin "2") (pinfunction "2_2") (pintype "passive"))
      (node (ref "OUT_JP3") (pin "2") (pinfunction "2_2") (pintype "passive"))
      (node (ref "SR15") (pin "9") (pinfunction "QH'_9") (pintype "tri_state"))
    )
    (net (code "10") (name "/DATA_OUT4") (class "Default")
      (node (ref "CONNECTION_BETWEEN_SR20-21") (pin "2") (pinfunction "2_2") (pintype "passive"))
      (node (ref "OUT_JP4") (pin "2") (pinfunction "2_2") (pintype "passive"))
      (node (ref "SR20") (pin "9") (pinfunction "QH'_9") (pintype "tri_state"))
    )
    (net (code "11") (name "/DATA_OUT5") (class "Default")
      (node (ref "OUT_JP5") (pin "2") (pinfunction "2_2") (pintype "passive"))
      (node (ref "SR25") (pin "9") (pinfunction "QH'_9") (pintype "tri_state"))
    )
    (net (code "12") (name "/EN1") (class "Default")
      (node (ref "EN_JP1") (pin "1") (pinfunction "1_1") (pintype "passive"))
      (node (ref "EN_JP2") (pin "1") (pinfunction "1_1") (pintype "passive"))
      (node (ref "L1") (pin "48") (pinfunction "1LE_48") (pintype "input"))
      (node (ref "L2") (pin "48") (pinfunction "1LE_48") (pintype "input"))
      (node (ref "L3") (pin "48") (pinfunction "1LE_48") (pintype "input"))
      (node (ref "L4") (pin "48") (pinfunction "1LE_48") (pintype "input"))
      (node (ref "L5") (pin "48") (pinfunction "1LE_48") (pintype "input"))
    )
    (net (code "13") (name "/EN2") (class "Default")
      (node (ref "EN_JP1") (pin "2") (pinfunction "2_2") (pintype "passive"))
      (node (ref "EN_JP2") (pin "2") (pinfunction "2_2") (pintype "passive"))
      (node (ref "L1") (pin "25") (pinfunction "2LE_25") (pintype "input"))
      (node (ref "L2") (pin "25") (pinfunction "2LE_25") (pintype "input"))
      (node (ref "L3") (pin "25") (pinfunction "2LE_25") (pintype "input"))
      (node (ref "L4") (pin "25") (pinfunction "2LE_25") (pintype "input"))
      (node (ref "L5") (pin "25") (pinfunction "2LE_25") (pintype "input"))
    )
    (net (code "14") (name "/EN3") (class "Default")
      (node (ref "EN_JP1") (pin "3") (pinfunction "3_3") (pintype "passive"))
      (node (ref "EN_JP2") (pin "3") (pinfunction "3_3") (pintype "passive"))
      (node (ref "L10") (pin "48") (pinfunction "1LE_48") (pintype "input"))
      (node (ref "L6") (pin "48") (pinfunction "1LE_48") (pintype "input"))
      (node (ref "L7") (pin "48") (pinfunction "1LE_48") (pintype "input"))
      (node (ref "L8") (pin "48") (pinfunction "1LE_48") (pintype "input"))
      (node (ref "L9") (pin "48") (pinfunction "1LE_48") (pintype "input"))
    )
    (net (code "15") (name "/EN4") (class "Default")
      (node (ref "EN_JP1") (pin "4") (pinfunction "4_4") (pintype "passive"))
      (node (ref "EN_JP2") (pin "4") (pinfunction "4_4") (pintype "passive"))
      (node (ref "L10") (pin "25") (pinfunction "2LE_25") (pintype "input"))
      (node (ref "L6") (pin "25") (pinfunction "2LE_25") (pintype "input"))
      (node (ref "L7") (pin "25") (pinfunction "2LE_25") (pintype "input"))
      (node (ref "L8") (pin "25") (pinfunction "2LE_25") (pintype "input"))
      (node (ref "L9") (pin "25") (pinfunction "2LE_25") (pintype "input"))
    )
    (net (code "16") (name "/EN5") (class "Default")
      (node (ref "EN_JP1") (pin "5") (pinfunction "5_5") (pintype "passive"))
      (node (ref "EN_JP2") (pin "5") (pinfunction "5_5") (pintype "passive"))
      (node (ref "L11") (pin "48") (pinfunction "1LE_48") (pintype "input"))
      (node (ref "L12") (pin "48") (pinfunction "1LE_48") (pintype "input"))
      (node (ref "L13") (pin "48") (pinfunction "1LE_48") (pintype "input"))
      (node (ref "L14") (pin "48") (pinfunction "1LE_48") (pintype "input"))
      (node (ref "L15") (pin "48") (pinfunction "1LE_48") (pintype "input"))
    )
    (net (code "17") (name "/EN6") (class "Default")
      (node (ref "EN_JP1") (pin "6") (pinfunction "6_6") (pintype "passive"))
      (node (ref "EN_JP2") (pin "6") (pinfunction "6_6") (pintype "passive"))
      (node (ref "L11") (pin "25") (pinfunction "2LE_25") (pintype "input"))
      (node (ref "L12") (pin "25") (pinfunction "2LE_25") (pintype "input"))
      (node (ref "L13") (pin "25") (pinfunction "2LE_25") (pintype "input"))
      (node (ref "L14") (pin "25") (pinfunction "2LE_25") (pintype "input"))
      (node (ref "L15") (pin "25") (pinfunction "2LE_25") (pintype "input"))
    )
    (net (code "18") (name "/EN7") (class "Default")
      (node (ref "EN_JP1") (pin "7") (pinfunction "7_7") (pintype "passive"))
      (node (ref "EN_JP2") (pin "7") (pinfunction "7_7") (pintype "passive"))
      (node (ref "L16") (pin "48") (pinfunction "1LE_48") (pintype "input"))
      (node (ref "L17") (pin "48") (pinfunction "1LE_48") (pintype "input"))
      (node (ref "L18") (pin "48") (pinfunction "1LE_48") (pintype "input"))
      (node (ref "L19") (pin "48") (pinfunction "1LE_48") (pintype "input"))
      (node (ref "L20") (pin "48") (pinfunction "1LE_48") (pintype "input"))
    )
    (net (code "19") (name "/EN8") (class "Default")
      (node (ref "EN_JP1") (pin "8") (pinfunction "8_8") (pintype "passive"))
      (node (ref "EN_JP2") (pin "8") (pinfunction "8_8") (pintype "passive"))
      (node (ref "L16") (pin "25") (pinfunction "2LE_25") (pintype "input"))
      (node (ref "L17") (pin "25") (pinfunction "2LE_25") (pintype "input"))
      (node (ref "L18") (pin "25") (pinfunction "2LE_25") (pintype "input"))
      (node (ref "L19") (pin "25") (pinfunction "2LE_25") (pintype "input"))
      (node (ref "L20") (pin "25") (pinfunction "2LE_25") (pintype "input"))
    )
    (net (code "20") (name "/EN9") (class "Default")
      (node (ref "EN_JP1") (pin "9") (pinfunction "9_9") (pintype "passive"))
      (node (ref "EN_JP2") (pin "9") (pinfunction "9_9") (pintype "passive"))
      (node (ref "L21") (pin "48") (pinfunction "1LE_48") (pintype "input"))
      (node (ref "L22") (pin "48") (pinfunction "1LE_48") (pintype "input"))
      (node (ref "L23") (pin "48") (pinfunction "1LE_48") (pintype "input"))
      (node (ref "L24") (pin "48") (pinfunction "1LE_48") (pintype "input"))
      (node (ref "L25") (pin "48") (pinfunction "1LE_48") (pintype "input"))
    )
    (net (code "21") (name "/EN10") (class "Default")
      (node (ref "EN_JP1") (pin "10") (pinfunction "10_10") (pintype "passive"))
      (node (ref "EN_JP2") (pin "10") (pinfunction "10_10") (pintype "passive"))
      (node (ref "L21") (pin "25") (pinfunction "2LE_25") (pintype "input"))
      (node (ref "L22") (pin "25") (pinfunction "2LE_25") (pintype "input"))
      (node (ref "L23") (pin "25") (pinfunction "2LE_25") (pintype "input"))
      (node (ref "L24") (pin "25") (pinfunction "2LE_25") (pintype "input"))
      (node (ref "L25") (pin "25") (pinfunction "2LE_25") (pintype "input"))
    )
    (net (code "22") (name "/FPC1_1") (class "Default")
      (node (ref "FPC1") (pin "1") (pinfunction "1_1") (pintype "passive"))
      (node (ref "L1") (pin "2") (pinfunction "1Q1_2") (pintype "tri_state"))
    )
    (net (code "23") (name "/FPC1_2") (class "Default")
      (node (ref "FPC1") (pin "2") (pinfunction "1_2") (pintype "passive"))
      (node (ref "L1") (pin "3") (pinfunction "1Q2_3") (pintype "tri_state"))
    )
    (net (code "24") (name "/FPC1_3") (class "Default")
      (node (ref "FPC1") (pin "3") (pinfunction "1_3") (pintype "passive"))
      (node (ref "L1") (pin "5") (pinfunction "1Q3_5") (pintype "tri_state"))
    )
    (net (code "25") (name "/FPC1_4") (class "Default")
      (node (ref "FPC1") (pin "4") (pinfunction "1_4") (pintype "passive"))
      (node (ref "L1") (pin "6") (pinfunction "1Q4_6") (pintype "tri_state"))
    )
    (net (code "26") (name "/FPC1_5") (class "Default")
      (node (ref "FPC1") (pin "5") (pinfunction "1_5") (pintype "passive"))
      (node (ref "L1") (pin "8") (pinfunction "1Q5_8") (pintype "tri_state"))
    )
    (net (code "27") (name "/FPC1_6") (class "Default")
      (node (ref "FPC1") (pin "6") (pinfunction "1_6") (pintype "passive"))
      (node (ref "L1") (pin "9") (pinfunction "1Q6_9") (pintype "tri_state"))
    )
    (net (code "28") (name "/FPC1_7") (class "Default")
      (node (ref "FPC1") (pin "7") (pinfunction "1_7") (pintype "passive"))
      (node (ref "L1") (pin "11") (pinfunction "1Q7_11") (pintype "tri_state"))
    )
    (net (code "29") (name "/FPC1_8") (class "Default")
      (node (ref "FPC1") (pin "8") (pinfunction "1_8") (pintype "passive"))
      (node (ref "L1") (pin "12") (pinfunction "1Q8_12") (pintype "tri_state"))
    )
    (net (code "30") (name "/FPC1_9") (class "Default")
      (node (ref "FPC1") (pin "9") (pinfunction "1_9") (pintype "passive"))
      (node (ref "L1") (pin "13") (pinfunction "2Q1_13") (pintype "tri_state"))
    )
    (net (code "31") (name "/FPC1_10") (class "Default")
      (node (ref "FPC1") (pin "10") (pinfunction "1_10") (pintype "passive"))
      (node (ref "L1") (pin "14") (pinfunction "2Q2_14") (pintype "tri_state"))
    )
    (net (code "32") (name "/FPC1_11") (class "Default")
      (node (ref "FPC1") (pin "11") (pinfunction "1_11") (pintype "passive"))
      (node (ref "L1") (pin "16") (pinfunction "2Q3_16") (pintype "tri_state"))
    )
    (net (code "33") (name "/FPC1_12") (class "Default")
      (node (ref "FPC1") (pin "12") (pinfunction "1_12") (pintype "passive"))
      (node (ref "L1") (pin "17") (pinfunction "2Q4_17") (pintype "tri_state"))
    )
    (net (code "34") (name "/FPC1_13") (class "Default")
      (node (ref "FPC1") (pin "13") (pinfunction "1_13") (pintype "passive"))
      (node (ref "L1") (pin "19") (pinfunction "2Q5_19") (pintype "tri_state"))
    )
    (net (code "35") (name "/FPC1_14") (class "Default")
      (node (ref "FPC1") (pin "14") (pinfunction "1_14") (pintype "passive"))
      (node (ref "L1") (pin "20") (pinfunction "2Q6_20") (pintype "tri_state"))
    )
    (net (code "36") (name "/FPC1_15") (class "Default")
      (node (ref "FPC1") (pin "15") (pinfunction "1_15") (pintype "passive"))
      (node (ref "L1") (pin "22") (pinfunction "2Q7_22") (pintype "tri_state"))
    )
    (net (code "37") (name "/FPC1_16") (class "Default")
      (node (ref "FPC1") (pin "16") (pinfunction "1_16") (pintype "passive"))
      (node (ref "L1") (pin "23") (pinfunction "2Q8_23") (pintype "tri_state"))
    )
    (net (code "38") (name "/FPC1_17") (class "Default")
      (node (ref "FPC1") (pin "17") (pinfunction "1_17") (pintype "passive"))
      (node (ref "L2") (pin "2") (pinfunction "1Q1_2") (pintype "tri_state"))
    )
    (net (code "39") (name "/FPC1_18") (class "Default")
      (node (ref "FPC1") (pin "18") (pinfunction "1_18") (pintype "passive"))
      (node (ref "L2") (pin "3") (pinfunction "1Q2_3") (pintype "tri_state"))
    )
    (net (code "40") (name "/FPC1_19") (class "Default")
      (node (ref "FPC1") (pin "19") (pinfunction "1_19") (pintype "passive"))
      (node (ref "L2") (pin "5") (pinfunction "1Q3_5") (pintype "tri_state"))
    )
    (net (code "41") (name "/FPC1_20") (class "Default")
      (node (ref "FPC1") (pin "20") (pinfunction "1_20") (pintype "passive"))
      (node (ref "L2") (pin "6") (pinfunction "1Q4_6") (pintype "tri_state"))
    )
    (net (code "42") (name "/FPC2_1") (class "Default")
      (node (ref "FPC2") (pin "1") (pinfunction "1_1") (pintype "passive"))
      (node (ref "L2") (pin "8") (pinfunction "1Q5_8") (pintype "tri_state"))
    )
    (net (code "43") (name "/FPC2_2") (class "Default")
      (node (ref "FPC2") (pin "2") (pinfunction "1_2") (pintype "passive"))
      (node (ref "L2") (pin "9") (pinfunction "1Q6_9") (pintype "tri_state"))
    )
    (net (code "44") (name "/FPC2_3") (class "Default")
      (node (ref "FPC2") (pin "3") (pinfunction "1_3") (pintype "passive"))
      (node (ref "L2") (pin "11") (pinfunction "1Q7_11") (pintype "tri_state"))
    )
    (net (code "45") (name "/FPC2_4") (class "Default")
      (node (ref "FPC2") (pin "4") (pinfunction "1_4") (pintype "passive"))
      (node (ref "L2") (pin "12") (pinfunction "1Q8_12") (pintype "tri_state"))
    )
    (net (code "46") (name "/FPC2_5") (class "Default")
      (node (ref "FPC2") (pin "5") (pinfunction "1_5") (pintype "passive"))
      (node (ref "L2") (pin "13") (pinfunction "2Q1_13") (pintype "tri_state"))
    )
    (net (code "47") (name "/FPC2_6") (class "Default")
      (node (ref "FPC2") (pin "6") (pinfunction "1_6") (pintype "passive"))
      (node (ref "L2") (pin "14") (pinfunction "2Q2_14") (pintype "tri_state"))
    )
    (net (code "48") (name "/FPC2_7") (class "Default")
      (node (ref "FPC2") (pin "7") (pinfunction "1_7") (pintype "passive"))
      (node (ref "L2") (pin "16") (pinfunction "2Q3_16") (pintype "tri_state"))
    )
    (net (code "49") (name "/FPC2_8") (class "Default")
      (node (ref "FPC2") (pin "8") (pinfunction "1_8") (pintype "passive"))
      (node (ref "L2") (pin "17") (pinfunction "2Q4_17") (pintype "tri_state"))
    )
    (net (code "50") (name "/FPC2_9") (class "Default")
      (node (ref "FPC2") (pin "9") (pinfunction "1_9") (pintype "passive"))
      (node (ref "L2") (pin "19") (pinfunction "2Q5_19") (pintype "tri_state"))
    )
    (net (code "51") (name "/FPC2_10") (class "Default")
      (node (ref "FPC2") (pin "10") (pinfunction "1_10") (pintype "passive"))
      (node (ref "L2") (pin "20") (pinfunction "2Q6_20") (pintype "tri_state"))
    )
    (net (code "52") (name "/FPC2_11") (class "Default")
      (node (ref "FPC2") (pin "11") (pinfunction "1_11") (pintype "passive"))
      (node (ref "L2") (pin "22") (pinfunction "2Q7_22") (pintype "tri_state"))
    )
    (net (code "53") (name "/FPC2_12") (class "Default")
      (node (ref "FPC2") (pin "12") (pinfunction "1_12") (pintype "passive"))
      (node (ref "L2") (pin "23") (pinfunction "2Q8_23") (pintype "tri_state"))
    )
    (net (code "54") (name "/FPC2_13") (class "Default")
      (node (ref "FPC2") (pin "13") (pinfunction "1_13") (pintype "passive"))
      (node (ref "L3") (pin "2") (pinfunction "1Q1_2") (pintype "tri_state"))
    )
    (net (code "55") (name "/FPC2_14") (class "Default")
      (node (ref "FPC2") (pin "14") (pinfunction "1_14") (pintype "passive"))
      (node (ref "L3") (pin "3") (pinfunction "1Q2_3") (pintype "tri_state"))
    )
    (net (code "56") (name "/FPC2_15") (class "Default")
      (node (ref "FPC2") (pin "15") (pinfunction "1_15") (pintype "passive"))
      (node (ref "L3") (pin "5") (pinfunction "1Q3_5") (pintype "tri_state"))
    )
    (net (code "57") (name "/FPC2_16") (class "Default")
      (node (ref "FPC2") (pin "16") (pinfunction "1_16") (pintype "passive"))
      (node (ref "L3") (pin "6") (pinfunction "1Q4_6") (pintype "tri_state"))
    )
    (net (code "58") (name "/FPC2_17") (class "Default")
      (node (ref "FPC2") (pin "17") (pinfunction "1_17") (pintype "passive"))
      (node (ref "L3") (pin "8") (pinfunction "1Q5_8") (pintype "tri_state"))
    )
    (net (code "59") (name "/FPC2_18") (class "Default")
      (node (ref "FPC2") (pin "18") (pinfunction "1_18") (pintype "passive"))
      (node (ref "L3") (pin "9") (pinfunction "1Q6_9") (pintype "tri_state"))
    )
    (net (code "60") (name "/FPC2_19") (class "Default")
      (node (ref "FPC2") (pin "19") (pinfunction "1_19") (pintype "passive"))
      (node (ref "L3") (pin "11") (pinfunction "1Q7_11") (pintype "tri_state"))
    )
    (net (code "61") (name "/FPC2_20") (class "Default")
      (node (ref "FPC2") (pin "20") (pinfunction "1_20") (pintype "passive"))
      (node (ref "L3") (pin "12") (pinfunction "1Q8_12") (pintype "tri_state"))
    )
    (net (code "62") (name "/FPC3_1") (class "Default")
      (node (ref "FPC3") (pin "1") (pinfunction "1_1") (pintype "passive"))
      (node (ref "L3") (pin "13") (pinfunction "2Q1_13") (pintype "tri_state"))
    )
    (net (code "63") (name "/FPC3_2") (class "Default")
      (node (ref "FPC3") (pin "2") (pinfunction "1_2") (pintype "passive"))
      (node (ref "L3") (pin "14") (pinfunction "2Q2_14") (pintype "tri_state"))
    )
    (net (code "64") (name "/FPC3_3") (class "Default")
      (node (ref "FPC3") (pin "3") (pinfunction "1_3") (pintype "passive"))
      (node (ref "L3") (pin "16") (pinfunction "2Q3_16") (pintype "tri_state"))
    )
    (net (code "65") (name "/FPC3_4") (class "Default")
      (node (ref "FPC3") (pin "4") (pinfunction "1_4") (pintype "passive"))
      (node (ref "L3") (pin "17") (pinfunction "2Q4_17") (pintype "tri_state"))
    )
    (net (code "66") (name "/FPC3_5") (class "Default")
      (node (ref "FPC3") (pin "5") (pinfunction "1_5") (pintype "passive"))
      (node (ref "L3") (pin "19") (pinfunction "2Q5_19") (pintype "tri_state"))
    )
    (net (code "67") (name "/FPC3_6") (class "Default")
      (node (ref "FPC3") (pin "6") (pinfunction "1_6") (pintype "passive"))
      (node (ref "L3") (pin "20") (pinfunction "2Q6_20") (pintype "tri_state"))
    )
    (net (code "68") (name "/FPC3_7") (class "Default")
      (node (ref "FPC3") (pin "7") (pinfunction "1_7") (pintype "passive"))
      (node (ref "L3") (pin "22") (pinfunction "2Q7_22") (pintype "tri_state"))
    )
    (net (code "69") (name "/FPC3_8") (class "Default")
      (node (ref "FPC3") (pin "8") (pinfunction "1_8") (pintype "passive"))
      (node (ref "L3") (pin "23") (pinfunction "2Q8_23") (pintype "tri_state"))
    )
    (net (code "70") (name "/FPC3_9") (class "Default")
      (node (ref "FPC3") (pin "9") (pinfunction "1_9") (pintype "passive"))
      (node (ref "L4") (pin "2") (pinfunction "1Q1_2") (pintype "tri_state"))
    )
    (net (code "71") (name "/FPC3_10") (class "Default")
      (node (ref "FPC3") (pin "10") (pinfunction "1_10") (pintype "passive"))
      (node (ref "L4") (pin "3") (pinfunction "1Q2_3") (pintype "tri_state"))
    )
    (net (code "72") (name "/FPC3_11") (class "Default")
      (node (ref "FPC3") (pin "11") (pinfunction "1_11") (pintype "passive"))
      (node (ref "L4") (pin "5") (pinfunction "1Q3_5") (pintype "tri_state"))
    )
    (net (code "73") (name "/FPC3_12") (class "Default")
      (node (ref "FPC3") (pin "12") (pinfunction "1_12") (pintype "passive"))
      (node (ref "L4") (pin "6") (pinfunction "1Q4_6") (pintype "tri_state"))
    )
    (net (code "74") (name "/FPC3_13") (class "Default")
      (node (ref "FPC3") (pin "13") (pinfunction "1_13") (pintype "passive"))
      (node (ref "L4") (pin "8") (pinfunction "1Q5_8") (pintype "tri_state"))
    )
    (net (code "75") (name "/FPC3_14") (class "Default")
      (node (ref "FPC3") (pin "14") (pinfunction "1_14") (pintype "passive"))
      (node (ref "L4") (pin "9") (pinfunction "1Q6_9") (pintype "tri_state"))
    )
    (net (code "76") (name "/FPC3_15") (class "Default")
      (node (ref "FPC3") (pin "15") (pinfunction "1_15") (pintype "passive"))
      (node (ref "L4") (pin "11") (pinfunction "1Q7_11") (pintype "tri_state"))
    )
    (net (code "77") (name "/FPC3_16") (class "Default")
      (node (ref "FPC3") (pin "16") (pinfunction "1_16") (pintype "passive"))
      (node (ref "L4") (pin "12") (pinfunction "1Q8_12") (pintype "tri_state"))
    )
    (net (code "78") (name "/FPC3_17") (class "Default")
      (node (ref "FPC3") (pin "17") (pinfunction "1_17") (pintype "passive"))
      (node (ref "L4") (pin "13") (pinfunction "2Q1_13") (pintype "tri_state"))
    )
    (net (code "79") (name "/FPC3_18") (class "Default")
      (node (ref "FPC3") (pin "18") (pinfunction "1_18") (pintype "passive"))
      (node (ref "L4") (pin "14") (pinfunction "2Q2_14") (pintype "tri_state"))
    )
    (net (code "80") (name "/FPC3_19") (class "Default")
      (node (ref "FPC3") (pin "19") (pinfunction "1_19") (pintype "passive"))
      (node (ref "L4") (pin "16") (pinfunction "2Q3_16") (pintype "tri_state"))
    )
    (net (code "81") (name "/FPC3_20") (class "Default")
      (node (ref "FPC3") (pin "20") (pinfunction "1_20") (pintype "passive"))
      (node (ref "L4") (pin "17") (pinfunction "2Q4_17") (pintype "tri_state"))
    )
    (net (code "82") (name "/FPC4_1") (class "Default")
      (node (ref "FPC4") (pin "1") (pinfunction "1_1") (pintype "passive"))
      (node (ref "L4") (pin "19") (pinfunction "2Q5_19") (pintype "tri_state"))
    )
    (net (code "83") (name "/FPC4_2") (class "Default")
      (node (ref "FPC4") (pin "2") (pinfunction "1_2") (pintype "passive"))
      (node (ref "L4") (pin "20") (pinfunction "2Q6_20") (pintype "tri_state"))
    )
    (net (code "84") (name "/FPC4_3") (class "Default")
      (node (ref "FPC4") (pin "3") (pinfunction "1_3") (pintype "passive"))
      (node (ref "L4") (pin "22") (pinfunction "2Q7_22") (pintype "tri_state"))
    )
    (net (code "85") (name "/FPC4_4") (class "Default")
      (node (ref "FPC4") (pin "4") (pinfunction "1_4") (pintype "passive"))
      (node (ref "L4") (pin "23") (pinfunction "2Q8_23") (pintype "tri_state"))
    )
    (net (code "86") (name "/FPC4_5") (class "Default")
      (node (ref "FPC4") (pin "5") (pinfunction "1_5") (pintype "passive"))
      (node (ref "L5") (pin "2") (pinfunction "1Q1_2") (pintype "tri_state"))
    )
    (net (code "87") (name "/FPC4_6") (class "Default")
      (node (ref "FPC4") (pin "6") (pinfunction "1_6") (pintype "passive"))
      (node (ref "L5") (pin "3") (pinfunction "1Q2_3") (pintype "tri_state"))
    )
    (net (code "88") (name "/FPC4_7") (class "Default")
      (node (ref "FPC4") (pin "7") (pinfunction "1_7") (pintype "passive"))
      (node (ref "L5") (pin "5") (pinfunction "1Q3_5") (pintype "tri_state"))
    )
    (net (code "89") (name "/FPC4_8") (class "Default")
      (node (ref "FPC4") (pin "8") (pinfunction "1_8") (pintype "passive"))
      (node (ref "L5") (pin "6") (pinfunction "1Q4_6") (pintype "tri_state"))
    )
    (net (code "90") (name "/FPC4_9") (class "Default")
      (node (ref "FPC4") (pin "9") (pinfunction "1_9") (pintype "passive"))
      (node (ref "L5") (pin "8") (pinfunction "1Q5_8") (pintype "tri_state"))
    )
    (net (code "91") (name "/FPC4_10") (class "Default")
      (node (ref "FPC4") (pin "10") (pinfunction "1_10") (pintype "passive"))
      (node (ref "L5") (pin "9") (pinfunction "1Q6_9") (pintype "tri_state"))
    )
    (net (code "92") (name "/FPC4_11") (class "Default")
      (node (ref "FPC4") (pin "11") (pinfunction "1_11") (pintype "passive"))
      (node (ref "L5") (pin "11") (pinfunction "1Q7_11") (pintype "tri_state"))
    )
    (net (code "93") (name "/FPC4_12") (class "Default")
      (node (ref "FPC4") (pin "12") (pinfunction "1_12") (pintype "passive"))
      (node (ref "L5") (pin "12") (pinfunction "1Q8_12") (pintype "tri_state"))
    )
    (net (code "94") (name "/FPC4_13") (class "Default")
      (node (ref "FPC4") (pin "13") (pinfunction "1_13") (pintype "passive"))
      (node (ref "L5") (pin "13") (pinfunction "2Q1_13") (pintype "tri_state"))
    )
    (net (code "95") (name "/FPC4_14") (class "Default")
      (node (ref "FPC4") (pin "14") (pinfunction "1_14") (pintype "passive"))
      (node (ref "L5") (pin "14") (pinfunction "2Q2_14") (pintype "tri_state"))
    )
    (net (code "96") (name "/FPC4_15") (class "Default")
      (node (ref "FPC4") (pin "15") (pinfunction "1_15") (pintype "passive"))
      (node (ref "L5") (pin "16") (pinfunction "2Q3_16") (pintype "tri_state"))
    )
    (net (code "97") (name "/FPC4_16") (class "Default")
      (node (ref "FPC4") (pin "16") (pinfunction "1_16") (pintype "passive"))
      (node (ref "L5") (pin "17") (pinfunction "2Q4_17") (pintype "tri_state"))
    )
    (net (code "98") (name "/FPC4_17") (class "Default")
      (node (ref "FPC4") (pin "17") (pinfunction "1_17") (pintype "passive"))
      (node (ref "L5") (pin "19") (pinfunction "2Q5_19") (pintype "tri_state"))
    )
    (net (code "99") (name "/FPC4_18") (class "Default")
      (node (ref "FPC4") (pin "18") (pinfunction "1_18") (pintype "passive"))
      (node (ref "L5") (pin "20") (pinfunction "2Q6_20") (pintype "tri_state"))
    )
    (net (code "100") (name "/FPC4_19") (class "Default")
      (node (ref "FPC4") (pin "19") (pinfunction "1_19") (pintype "passive"))
      (node (ref "L5") (pin "22") (pinfunction "2Q7_22") (pintype "tri_state"))
    )
    (net (code "101") (name "/FPC4_20") (class "Default")
      (node (ref "FPC4") (pin "20") (pinfunction "1_20") (pintype "passive"))
      (node (ref "L5") (pin "23") (pinfunction "2Q8_23") (pintype "tri_state"))
    )
    (net (code "102") (name "/FPC5_1") (class "Default")
      (node (ref "FPC5") (pin "1") (pinfunction "1_1") (pintype "passive"))
      (node (ref "L6") (pin "2") (pinfunction "1Q1_2") (pintype "tri_state"))
    )
    (net (code "103") (name "/FPC5_2") (class "Default")
      (node (ref "FPC5") (pin "2") (pinfunction "1_2") (pintype "passive"))
      (node (ref "L6") (pin "3") (pinfunction "1Q2_3") (pintype "tri_state"))
    )
    (net (code "104") (name "/FPC5_3") (class "Default")
      (node (ref "FPC5") (pin "3") (pinfunction "1_3") (pintype "passive"))
      (node (ref "L6") (pin "5") (pinfunction "1Q3_5") (pintype "tri_state"))
    )
    (net (code "105") (name "/FPC5_4") (class "Default")
      (node (ref "FPC5") (pin "4") (pinfunction "1_4") (pintype "passive"))
      (node (ref "L6") (pin "6") (pinfunction "1Q4_6") (pintype "tri_state"))
    )
    (net (code "106") (name "/FPC5_5") (class "Default")
      (node (ref "FPC5") (pin "5") (pinfunction "1_5") (pintype "passive"))
      (node (ref "L6") (pin "8") (pinfunction "1Q5_8") (pintype "tri_state"))
    )
    (net (code "107") (name "/FPC5_6") (class "Default")
      (node (ref "FPC5") (pin "6") (pinfunction "1_6") (pintype "passive"))
      (node (ref "L6") (pin "9") (pinfunction "1Q6_9") (pintype "tri_state"))
    )
    (net (code "108") (name "/FPC5_7") (class "Default")
      (node (ref "FPC5") (pin "7") (pinfunction "1_7") (pintype "passive"))
      (node (ref "L6") (pin "11") (pinfunction "1Q7_11") (pintype "tri_state"))
    )
    (net (code "109") (name "/FPC5_8") (class "Default")
      (node (ref "FPC5") (pin "8") (pinfunction "1_8") (pintype "passive"))
      (node (ref "L6") (pin "12") (pinfunction "1Q8_12") (pintype "tri_state"))
    )
    (net (code "110") (name "/FPC5_9") (class "Default")
      (node (ref "FPC5") (pin "9") (pinfunction "1_9") (pintype "passive"))
      (node (ref "L6") (pin "13") (pinfunction "2Q1_13") (pintype "tri_state"))
    )
    (net (code "111") (name "/FPC5_10") (class "Default")
      (node (ref "FPC5") (pin "10") (pinfunction "1_10") (pintype "passive"))
      (node (ref "L6") (pin "14") (pinfunction "2Q2_14") (pintype "tri_state"))
    )
    (net (code "112") (name "/FPC5_11") (class "Default")
      (node (ref "FPC5") (pin "11") (pinfunction "1_11") (pintype "passive"))
      (node (ref "L6") (pin "16") (pinfunction "2Q3_16") (pintype "tri_state"))
    )
    (net (code "113") (name "/FPC5_12") (class "Default")
      (node (ref "FPC5") (pin "12") (pinfunction "1_12") (pintype "passive"))
      (node (ref "L6") (pin "17") (pinfunction "2Q4_17") (pintype "tri_state"))
    )
    (net (code "114") (name "/FPC5_13") (class "Default")
      (node (ref "FPC5") (pin "13") (pinfunction "1_13") (pintype "passive"))
      (node (ref "L6") (pin "19") (pinfunction "2Q5_19") (pintype "tri_state"))
    )
    (net (code "115") (name "/FPC5_14") (class "Default")
      (node (ref "FPC5") (pin "14") (pinfunction "1_14") (pintype "passive"))
      (node (ref "L6") (pin "20") (pinfunction "2Q6_20") (pintype "tri_state"))
    )
    (net (code "116") (name "/FPC5_15") (class "Default")
      (node (ref "FPC5") (pin "15") (pinfunction "1_15") (pintype "passive"))
      (node (ref "L6") (pin "22") (pinfunction "2Q7_22") (pintype "tri_state"))
    )
    (net (code "117") (name "/FPC5_16") (class "Default")
      (node (ref "FPC5") (pin "16") (pinfunction "1_16") (pintype "passive"))
      (node (ref "L6") (pin "23") (pinfunction "2Q8_23") (pintype "tri_state"))
    )
    (net (code "118") (name "/FPC5_17") (class "Default")
      (node (ref "FPC5") (pin "17") (pinfunction "1_17") (pintype "passive"))
      (node (ref "L7") (pin "2") (pinfunction "1Q1_2") (pintype "tri_state"))
    )
    (net (code "119") (name "/FPC5_18") (class "Default")
      (node (ref "FPC5") (pin "18") (pinfunction "1_18") (pintype "passive"))
      (node (ref "L7") (pin "3") (pinfunction "1Q2_3") (pintype "tri_state"))
    )
    (net (code "120") (name "/FPC5_19") (class "Default")
      (node (ref "FPC5") (pin "19") (pinfunction "1_19") (pintype "passive"))
      (node (ref "L7") (pin "5") (pinfunction "1Q3_5") (pintype "tri_state"))
    )
    (net (code "121") (name "/FPC5_20") (class "Default")
      (node (ref "FPC5") (pin "20") (pinfunction "1_20") (pintype "passive"))
      (node (ref "L7") (pin "6") (pinfunction "1Q4_6") (pintype "tri_state"))
    )
    (net (code "122") (name "/FPC6_1") (class "Default")
      (node (ref "FPC6") (pin "1") (pinfunction "1_1") (pintype "passive"))
      (node (ref "L7") (pin "8") (pinfunction "1Q5_8") (pintype "tri_state"))
    )
    (net (code "123") (name "/FPC6_2") (class "Default")
      (node (ref "FPC6") (pin "2") (pinfunction "1_2") (pintype "passive"))
      (node (ref "L7") (pin "9") (pinfunction "1Q6_9") (pintype "tri_state"))
    )
    (net (code "124") (name "/FPC6_3") (class "Default")
      (node (ref "FPC6") (pin "3") (pinfunction "1_3") (pintype "passive"))
      (node (ref "L7") (pin "11") (pinfunction "1Q7_11") (pintype "tri_state"))
    )
    (net (code "125") (name "/FPC6_4") (class "Default")
      (node (ref "FPC6") (pin "4") (pinfunction "1_4") (pintype "passive"))
      (node (ref "L7") (pin "12") (pinfunction "1Q8_12") (pintype "tri_state"))
    )
    (net (code "126") (name "/FPC6_5") (class "Default")
      (node (ref "FPC6") (pin "5") (pinfunction "1_5") (pintype "passive"))
      (node (ref "L7") (pin "13") (pinfunction "2Q1_13") (pintype "tri_state"))
    )
    (net (code "127") (name "/FPC6_6") (class "Default")
      (node (ref "FPC6") (pin "6") (pinfunction "1_6") (pintype "passive"))
      (node (ref "L7") (pin "14") (pinfunction "2Q2_14") (pintype "tri_state"))
    )
    (net (code "128") (name "/FPC6_7") (class "Default")
      (node (ref "FPC6") (pin "7") (pinfunction "1_7") (pintype "passive"))
      (node (ref "L7") (pin "16") (pinfunction "2Q3_16") (pintype "tri_state"))
    )
    (net (code "129") (name "/FPC6_8") (class "Default")
      (node (ref "FPC6") (pin "8") (pinfunction "1_8") (pintype "passive"))
      (node (ref "L7") (pin "17") (pinfunction "2Q4_17") (pintype "tri_state"))
    )
    (net (code "130") (name "/FPC6_9") (class "Default")
      (node (ref "FPC6") (pin "9") (pinfunction "1_9") (pintype "passive"))
      (node (ref "L7") (pin "19") (pinfunction "2Q5_19") (pintype "tri_state"))
    )
    (net (code "131") (name "/FPC6_10") (class "Default")
      (node (ref "FPC6") (pin "10") (pinfunction "1_10") (pintype "passive"))
      (node (ref "L7") (pin "20") (pinfunction "2Q6_20") (pintype "tri_state"))
    )
    (net (code "132") (name "/FPC6_11") (class "Default")
      (node (ref "FPC6") (pin "11") (pinfunction "1_11") (pintype "passive"))
      (node (ref "L7") (pin "22") (pinfunction "2Q7_22") (pintype "tri_state"))
    )
    (net (code "133") (name "/FPC6_12") (class "Default")
      (node (ref "FPC6") (pin "12") (pinfunction "1_12") (pintype "passive"))
      (node (ref "L7") (pin "23") (pinfunction "2Q8_23") (pintype "tri_state"))
    )
    (net (code "134") (name "/FPC6_13") (class "Default")
      (node (ref "FPC6") (pin "13") (pinfunction "1_13") (pintype "passive"))
      (node (ref "L8") (pin "2") (pinfunction "1Q1_2") (pintype "tri_state"))
    )
    (net (code "135") (name "/FPC6_14") (class "Default")
      (node (ref "FPC6") (pin "14") (pinfunction "1_14") (pintype "passive"))
      (node (ref "L8") (pin "3") (pinfunction "1Q2_3") (pintype "tri_state"))
    )
    (net (code "136") (name "/FPC6_15") (class "Default")
      (node (ref "FPC6") (pin "15") (pinfunction "1_15") (pintype "passive"))
      (node (ref "L8") (pin "5") (pinfunction "1Q3_5") (pintype "tri_state"))
    )
    (net (code "137") (name "/FPC6_16") (class "Default")
      (node (ref "FPC6") (pin "16") (pinfunction "1_16") (pintype "passive"))
      (node (ref "L8") (pin "6") (pinfunction "1Q4_6") (pintype "tri_state"))
    )
    (net (code "138") (name "/FPC6_17") (class "Default")
      (node (ref "FPC6") (pin "17") (pinfunction "1_17") (pintype "passive"))
      (node (ref "L8") (pin "8") (pinfunction "1Q5_8") (pintype "tri_state"))
    )
    (net (code "139") (name "/FPC6_18") (class "Default")
      (node (ref "FPC6") (pin "18") (pinfunction "1_18") (pintype "passive"))
      (node (ref "L8") (pin "9") (pinfunction "1Q6_9") (pintype "tri_state"))
    )
    (net (code "140") (name "/FPC6_19") (class "Default")
      (node (ref "FPC6") (pin "19") (pinfunction "1_19") (pintype "passive"))
      (node (ref "L8") (pin "11") (pinfunction "1Q7_11") (pintype "tri_state"))
    )
    (net (code "141") (name "/FPC6_20") (class "Default")
      (node (ref "FPC6") (pin "20") (pinfunction "1_20") (pintype "passive"))
      (node (ref "L8") (pin "12") (pinfunction "1Q8_12") (pintype "tri_state"))
    )
    (net (code "142") (name "/FPC7_1") (class "Default")
      (node (ref "FPC7") (pin "1") (pinfunction "1_1") (pintype "passive"))
      (node (ref "L8") (pin "13") (pinfunction "2Q1_13") (pintype "tri_state"))
    )
    (net (code "143") (name "/FPC7_2") (class "Default")
      (node (ref "FPC7") (pin "2") (pinfunction "1_2") (pintype "passive"))
      (node (ref "L8") (pin "14") (pinfunction "2Q2_14") (pintype "tri_state"))
    )
    (net (code "144") (name "/FPC7_3") (class "Default")
      (node (ref "FPC7") (pin "3") (pinfunction "1_3") (pintype "passive"))
      (node (ref "L8") (pin "16") (pinfunction "2Q3_16") (pintype "tri_state"))
    )
    (net (code "145") (name "/FPC7_4") (class "Default")
      (node (ref "FPC7") (pin "4") (pinfunction "1_4") (pintype "passive"))
      (node (ref "L8") (pin "17") (pinfunction "2Q4_17") (pintype "tri_state"))
    )
    (net (code "146") (name "/FPC7_5") (class "Default")
      (node (ref "FPC7") (pin "5") (pinfunction "1_5") (pintype "passive"))
      (node (ref "L8") (pin "19") (pinfunction "2Q5_19") (pintype "tri_state"))
    )
    (net (code "147") (name "/FPC7_6") (class "Default")
      (node (ref "FPC7") (pin "6") (pinfunction "1_6") (pintype "passive"))
      (node (ref "L8") (pin "20") (pinfunction "2Q6_20") (pintype "tri_state"))
    )
    (net (code "148") (name "/FPC7_7") (class "Default")
      (node (ref "FPC7") (pin "7") (pinfunction "1_7") (pintype "passive"))
      (node (ref "L8") (pin "22") (pinfunction "2Q7_22") (pintype "tri_state"))
    )
    (net (code "149") (name "/FPC7_8") (class "Default")
      (node (ref "FPC7") (pin "8") (pinfunction "1_8") (pintype "passive"))
      (node (ref "L8") (pin "23") (pinfunction "2Q8_23") (pintype "tri_state"))
    )
    (net (code "150") (name "/FPC7_9") (class "Default")
      (node (ref "FPC7") (pin "9") (pinfunction "1_9") (pintype "passive"))
      (node (ref "L9") (pin "2") (pinfunction "1Q1_2") (pintype "tri_state"))
    )
    (net (code "151") (name "/FPC7_10") (class "Default")
      (node (ref "FPC7") (pin "10") (pinfunction "1_10") (pintype "passive"))
      (node (ref "L9") (pin "3") (pinfunction "1Q2_3") (pintype "tri_state"))
    )
    (net (code "152") (name "/FPC7_11") (class "Default")
      (node (ref "FPC7") (pin "11") (pinfunction "1_11") (pintype "passive"))
      (node (ref "L9") (pin "5") (pinfunction "1Q3_5") (pintype "tri_state"))
    )
    (net (code "153") (name "/FPC7_12") (class "Default")
      (node (ref "FPC7") (pin "12") (pinfunction "1_12") (pintype "passive"))
      (node (ref "L9") (pin "6") (pinfunction "1Q4_6") (pintype "tri_state"))
    )
    (net (code "154") (name "/FPC7_13") (class "Default")
      (node (ref "FPC7") (pin "13") (pinfunction "1_13") (pintype "passive"))
      (node (ref "L9") (pin "8") (pinfunction "1Q5_8") (pintype "tri_state"))
    )
    (net (code "155") (name "/FPC7_14") (class "Default")
      (node (ref "FPC7") (pin "14") (pinfunction "1_14") (pintype "passive"))
      (node (ref "L9") (pin "9") (pinfunction "1Q6_9") (pintype "tri_state"))
    )
    (net (code "156") (name "/FPC7_15") (class "Default")
      (node (ref "FPC7") (pin "15") (pinfunction "1_15") (pintype "passive"))
      (node (ref "L9") (pin "11") (pinfunction "1Q7_11") (pintype "tri_state"))
    )
    (net (code "157") (name "/FPC7_16") (class "Default")
      (node (ref "FPC7") (pin "16") (pinfunction "1_16") (pintype "passive"))
      (node (ref "L9") (pin "12") (pinfunction "1Q8_12") (pintype "tri_state"))
    )
    (net (code "158") (name "/FPC7_17") (class "Default")
      (node (ref "FPC7") (pin "17") (pinfunction "1_17") (pintype "passive"))
      (node (ref "L9") (pin "13") (pinfunction "2Q1_13") (pintype "tri_state"))
    )
    (net (code "159") (name "/FPC7_18") (class "Default")
      (node (ref "FPC7") (pin "18") (pinfunction "1_18") (pintype "passive"))
      (node (ref "L9") (pin "14") (pinfunction "2Q2_14") (pintype "tri_state"))
    )
    (net (code "160") (name "/FPC7_19") (class "Default")
      (node (ref "FPC7") (pin "19") (pinfunction "1_19") (pintype "passive"))
      (node (ref "L9") (pin "16") (pinfunction "2Q3_16") (pintype "tri_state"))
    )
    (net (code "161") (name "/FPC7_20") (class "Default")
      (node (ref "FPC7") (pin "20") (pinfunction "1_20") (pintype "passive"))
      (node (ref "L9") (pin "17") (pinfunction "2Q4_17") (pintype "tri_state"))
    )
    (net (code "162") (name "/FPC8_1") (class "Default")
      (node (ref "FPC8") (pin "1") (pinfunction "1_1") (pintype "passive"))
      (node (ref "L9") (pin "19") (pinfunction "2Q5_19") (pintype "tri_state"))
    )
    (net (code "163") (name "/FPC8_2") (class "Default")
      (node (ref "FPC8") (pin "2") (pinfunction "1_2") (pintype "passive"))
      (node (ref "L9") (pin "20") (pinfunction "2Q6_20") (pintype "tri_state"))
    )
    (net (code "164") (name "/FPC8_3") (class "Default")
      (node (ref "FPC8") (pin "3") (pinfunction "1_3") (pintype "passive"))
      (node (ref "L9") (pin "22") (pinfunction "2Q7_22") (pintype "tri_state"))
    )
    (net (code "165") (name "/FPC8_4") (class "Default")
      (node (ref "FPC8") (pin "4") (pinfunction "1_4") (pintype "passive"))
      (node (ref "L9") (pin "23") (pinfunction "2Q8_23") (pintype "tri_state"))
    )
    (net (code "166") (name "/FPC8_5") (class "Default")
      (node (ref "FPC8") (pin "5") (pinfunction "1_5") (pintype "passive"))
      (node (ref "L10") (pin "2") (pinfunction "1Q1_2") (pintype "tri_state"))
    )
    (net (code "167") (name "/FPC8_6") (class "Default")
      (node (ref "FPC8") (pin "6") (pinfunction "1_6") (pintype "passive"))
      (node (ref "L10") (pin "3") (pinfunction "1Q2_3") (pintype "tri_state"))
    )
    (net (code "168") (name "/FPC8_7") (class "Default")
      (node (ref "FPC8") (pin "7") (pinfunction "1_7") (pintype "passive"))
      (node (ref "L10") (pin "5") (pinfunction "1Q3_5") (pintype "tri_state"))
    )
    (net (code "169") (name "/FPC8_8") (class "Default")
      (node (ref "FPC8") (pin "8") (pinfunction "1_8") (pintype "passive"))
      (node (ref "L10") (pin "6") (pinfunction "1Q4_6") (pintype "tri_state"))
    )
    (net (code "170") (name "/FPC8_9") (class "Default")
      (node (ref "FPC8") (pin "9") (pinfunction "1_9") (pintype "passive"))
      (node (ref "L10") (pin "8") (pinfunction "1Q5_8") (pintype "tri_state"))
    )
    (net (code "171") (name "/FPC8_10") (class "Default")
      (node (ref "FPC8") (pin "10") (pinfunction "1_10") (pintype "passive"))
      (node (ref "L10") (pin "9") (pinfunction "1Q6_9") (pintype "tri_state"))
    )
    (net (code "172") (name "/FPC8_11") (class "Default")
      (node (ref "FPC8") (pin "11") (pinfunction "1_11") (pintype "passive"))
      (node (ref "L10") (pin "11") (pinfunction "1Q7_11") (pintype "tri_state"))
    )
    (net (code "173") (name "/FPC8_12") (class "Default")
      (node (ref "FPC8") (pin "12") (pinfunction "1_12") (pintype "passive"))
      (node (ref "L10") (pin "12") (pinfunction "1Q8_12") (pintype "tri_state"))
    )
    (net (code "174") (name "/FPC8_13") (class "Default")
      (node (ref "FPC8") (pin "13") (pinfunction "1_13") (pintype "passive"))
      (node (ref "L10") (pin "13") (pinfunction "2Q1_13") (pintype "tri_state"))
    )
    (net (code "175") (name "/FPC8_14") (class "Default")
      (node (ref "FPC8") (pin "14") (pinfunction "1_14") (pintype "passive"))
      (node (ref "L10") (pin "14") (pinfunction "2Q2_14") (pintype "tri_state"))
    )
    (net (code "176") (name "/FPC8_15") (class "Default")
      (node (ref "FPC8") (pin "15") (pinfunction "1_15") (pintype "passive"))
      (node (ref "L10") (pin "16") (pinfunction "2Q3_16") (pintype "tri_state"))
    )
    (net (code "177") (name "/FPC8_16") (class "Default")
      (node (ref "FPC8") (pin "16") (pinfunction "1_16") (pintype "passive"))
      (node (ref "L10") (pin "17") (pinfunction "2Q4_17") (pintype "tri_state"))
    )
    (net (code "178") (name "/FPC8_17") (class "Default")
      (node (ref "FPC8") (pin "17") (pinfunction "1_17") (pintype "passive"))
      (node (ref "L10") (pin "19") (pinfunction "2Q5_19") (pintype "tri_state"))
    )
    (net (code "179") (name "/FPC8_18") (class "Default")
      (node (ref "FPC8") (pin "18") (pinfunction "1_18") (pintype "passive"))
      (node (ref "L10") (pin "20") (pinfunction "2Q6_20") (pintype "tri_state"))
    )
    (net (code "180") (name "/FPC8_19") (class "Default")
      (node (ref "FPC8") (pin "19") (pinfunction "1_19") (pintype "passive"))
      (node (ref "L10") (pin "22") (pinfunction "2Q7_22") (pintype "tri_state"))
    )
    (net (code "181") (name "/FPC8_20") (class "Default")
      (node (ref "FPC8") (pin "20") (pinfunction "1_20") (pintype "passive"))
      (node (ref "L10") (pin "23") (pinfunction "2Q8_23") (pintype "tri_state"))
    )
    (net (code "182") (name "/FPC9_1") (class "Default")
      (node (ref "FPC9") (pin "1") (pinfunction "1_1") (pintype "passive"))
      (node (ref "L11") (pin "2") (pinfunction "1Q1_2") (pintype "tri_state"))
    )
    (net (code "183") (name "/FPC9_2") (class "Default")
      (node (ref "FPC9") (pin "2") (pinfunction "1_2") (pintype "passive"))
      (node (ref "L11") (pin "3") (pinfunction "1Q2_3") (pintype "tri_state"))
    )
    (net (code "184") (name "/FPC9_3") (class "Default")
      (node (ref "FPC9") (pin "3") (pinfunction "1_3") (pintype "passive"))
      (node (ref "L11") (pin "5") (pinfunction "1Q3_5") (pintype "tri_state"))
    )
    (net (code "185") (name "/FPC9_4") (class "Default")
      (node (ref "FPC9") (pin "4") (pinfunction "1_4") (pintype "passive"))
      (node (ref "L11") (pin "6") (pinfunction "1Q4_6") (pintype "tri_state"))
    )
    (net (code "186") (name "/FPC9_5") (class "Default")
      (node (ref "FPC9") (pin "5") (pinfunction "1_5") (pintype "passive"))
      (node (ref "L11") (pin "8") (pinfunction "1Q5_8") (pintype "tri_state"))
    )
    (net (code "187") (name "/FPC9_6") (class "Default")
      (node (ref "FPC9") (pin "6") (pinfunction "1_6") (pintype "passive"))
      (node (ref "L11") (pin "9") (pinfunction "1Q6_9") (pintype "tri_state"))
    )
    (net (code "188") (name "/FPC9_7") (class "Default")
      (node (ref "FPC9") (pin "7") (pinfunction "1_7") (pintype "passive"))
      (node (ref "L11") (pin "11") (pinfunction "1Q7_11") (pintype "tri_state"))
    )
    (net (code "189") (name "/FPC9_8") (class "Default")
      (node (ref "FPC9") (pin "8") (pinfunction "1_8") (pintype "passive"))
      (node (ref "L11") (pin "12") (pinfunction "1Q8_12") (pintype "tri_state"))
    )
    (net (code "190") (name "/FPC9_9") (class "Default")
      (node (ref "FPC9") (pin "9") (pinfunction "1_9") (pintype "passive"))
      (node (ref "L11") (pin "13") (pinfunction "2Q1_13") (pintype "tri_state"))
    )
    (net (code "191") (name "/FPC9_10") (class "Default")
      (node (ref "FPC9") (pin "10") (pinfunction "1_10") (pintype "passive"))
      (node (ref "L11") (pin "14") (pinfunction "2Q2_14") (pintype "tri_state"))
    )
    (net (code "192") (name "/FPC9_11") (class "Default")
      (node (ref "FPC9") (pin "11") (pinfunction "1_11") (pintype "passive"))
      (node (ref "L11") (pin "16") (pinfunction "2Q3_16") (pintype "tri_state"))
    )
    (net (code "193") (name "/FPC9_12") (class "Default")
      (node (ref "FPC9") (pin "12") (pinfunction "1_12") (pintype "passive"))
      (node (ref "L11") (pin "17") (pinfunction "2Q4_17") (pintype "tri_state"))
    )
    (net (code "194") (name "/FPC9_13") (class "Default")
      (node (ref "FPC9") (pin "13") (pinfunction "1_13") (pintype "passive"))
      (node (ref "L11") (pin "19") (pinfunction "2Q5_19") (pintype "tri_state"))
    )
    (net (code "195") (name "/FPC9_14") (class "Default")
      (node (ref "FPC9") (pin "14") (pinfunction "1_14") (pintype "passive"))
      (node (ref "L11") (pin "20") (pinfunction "2Q6_20") (pintype "tri_state"))
    )
    (net (code "196") (name "/FPC9_15") (class "Default")
      (node (ref "FPC9") (pin "15") (pinfunction "1_15") (pintype "passive"))
      (node (ref "L11") (pin "22") (pinfunction "2Q7_22") (pintype "tri_state"))
    )
    (net (code "197") (name "/FPC9_16") (class "Default")
      (node (ref "FPC9") (pin "16") (pinfunction "1_16") (pintype "passive"))
      (node (ref "L11") (pin "23") (pinfunction "2Q8_23") (pintype "tri_state"))
    )
    (net (code "198") (name "/FPC9_17") (class "Default")
      (node (ref "FPC9") (pin "17") (pinfunction "1_17") (pintype "passive"))
      (node (ref "L12") (pin "2") (pinfunction "1Q1_2") (pintype "tri_state"))
    )
    (net (code "199") (name "/FPC9_18") (class "Default")
      (node (ref "FPC9") (pin "18") (pinfunction "1_18") (pintype "passive"))
      (node (ref "L12") (pin "3") (pinfunction "1Q2_3") (pintype "tri_state"))
    )
    (net (code "200") (name "/FPC9_19") (class "Default")
      (node (ref "FPC9") (pin "19") (pinfunction "1_19") (pintype "passive"))
      (node (ref "L12") (pin "5") (pinfunction "1Q3_5") (pintype "tri_state"))
    )
    (net (code "201") (name "/FPC9_20") (class "Default")
      (node (ref "FPC9") (pin "20") (pinfunction "1_20") (pintype "passive"))
      (node (ref "L12") (pin "6") (pinfunction "1Q4_6") (pintype "tri_state"))
    )
    (net (code "202") (name "/FPC10_1") (class "Default")
      (node (ref "FPC10") (pin "1") (pinfunction "1_1") (pintype "passive"))
      (node (ref "L12") (pin "8") (pinfunction "1Q5_8") (pintype "tri_state"))
    )
    (net (code "203") (name "/FPC10_2") (class "Default")
      (node (ref "FPC10") (pin "2") (pinfunction "1_2") (pintype "passive"))
      (node (ref "L12") (pin "9") (pinfunction "1Q6_9") (pintype "tri_state"))
    )
    (net (code "204") (name "/FPC10_3") (class "Default")
      (node (ref "FPC10") (pin "3") (pinfunction "1_3") (pintype "passive"))
      (node (ref "L12") (pin "11") (pinfunction "1Q7_11") (pintype "tri_state"))
    )
    (net (code "205") (name "/FPC10_4") (class "Default")
      (node (ref "FPC10") (pin "4") (pinfunction "1_4") (pintype "passive"))
      (node (ref "L12") (pin "12") (pinfunction "1Q8_12") (pintype "tri_state"))
    )
    (net (code "206") (name "/FPC10_5") (class "Default")
      (node (ref "FPC10") (pin "5") (pinfunction "1_5") (pintype "passive"))
      (node (ref "L12") (pin "13") (pinfunction "2Q1_13") (pintype "tri_state"))
    )
    (net (code "207") (name "/FPC10_6") (class "Default")
      (node (ref "FPC10") (pin "6") (pinfunction "1_6") (pintype "passive"))
      (node (ref "L12") (pin "14") (pinfunction "2Q2_14") (pintype "tri_state"))
    )
    (net (code "208") (name "/FPC10_7") (class "Default")
      (node (ref "FPC10") (pin "7") (pinfunction "1_7") (pintype "passive"))
      (node (ref "L12") (pin "16") (pinfunction "2Q3_16") (pintype "tri_state"))
    )
    (net (code "209") (name "/FPC10_8") (class "Default")
      (node (ref "FPC10") (pin "8") (pinfunction "1_8") (pintype "passive"))
      (node (ref "L12") (pin "17") (pinfunction "2Q4_17") (pintype "tri_state"))
    )
    (net (code "210") (name "/FPC10_9") (class "Default")
      (node (ref "FPC10") (pin "9") (pinfunction "1_9") (pintype "passive"))
      (node (ref "L12") (pin "19") (pinfunction "2Q5_19") (pintype "tri_state"))
    )
    (net (code "211") (name "/FPC10_10") (class "Default")
      (node (ref "FPC10") (pin "10") (pinfunction "1_10") (pintype "passive"))
      (node (ref "L12") (pin "20") (pinfunction "2Q6_20") (pintype "tri_state"))
    )
    (net (code "212") (name "/FPC10_11") (class "Default")
      (node (ref "FPC10") (pin "11") (pinfunction "1_11") (pintype "passive"))
      (node (ref "L12") (pin "22") (pinfunction "2Q7_22") (pintype "tri_state"))
    )
    (net (code "213") (name "/FPC10_12") (class "Default")
      (node (ref "FPC10") (pin "12") (pinfunction "1_12") (pintype "passive"))
      (node (ref "L12") (pin "23") (pinfunction "2Q8_23") (pintype "tri_state"))
    )
    (net (code "214") (name "/FPC10_13") (class "Default")
      (node (ref "FPC10") (pin "13") (pinfunction "1_13") (pintype "passive"))
      (node (ref "L13") (pin "2") (pinfunction "1Q1_2") (pintype "tri_state"))
    )
    (net (code "215") (name "/FPC10_14") (class "Default")
      (node (ref "FPC10") (pin "14") (pinfunction "1_14") (pintype "passive"))
      (node (ref "L13") (pin "3") (pinfunction "1Q2_3") (pintype "tri_state"))
    )
    (net (code "216") (name "/FPC10_15") (class "Default")
      (node (ref "FPC10") (pin "15") (pinfunction "1_15") (pintype "passive"))
      (node (ref "L13") (pin "5") (pinfunction "1Q3_5") (pintype "tri_state"))
    )
    (net (code "217") (name "/FPC10_16") (class "Default")
      (node (ref "FPC10") (pin "16") (pinfunction "1_16") (pintype "passive"))
      (node (ref "L13") (pin "6") (pinfunction "1Q4_6") (pintype "tri_state"))
    )
    (net (code "218") (name "/FPC10_17") (class "Default")
      (node (ref "FPC10") (pin "17") (pinfunction "1_17") (pintype "passive"))
      (node (ref "L13") (pin "8") (pinfunction "1Q5_8") (pintype "tri_state"))
    )
    (net (code "219") (name "/FPC10_18") (class "Default")
      (node (ref "FPC10") (pin "18") (pinfunction "1_18") (pintype "passive"))
      (node (ref "L13") (pin "9") (pinfunction "1Q6_9") (pintype "tri_state"))
    )
    (net (code "220") (name "/FPC10_19") (class "Default")
      (node (ref "FPC10") (pin "19") (pinfunction "1_19") (pintype "passive"))
      (node (ref "L13") (pin "11") (pinfunction "1Q7_11") (pintype "tri_state"))
    )
    (net (code "221") (name "/FPC10_20") (class "Default")
      (node (ref "FPC10") (pin "20") (pinfunction "1_20") (pintype "passive"))
      (node (ref "L13") (pin "12") (pinfunction "1Q8_12") (pintype "tri_state"))
    )
    (net (code "222") (name "/FPC11_1") (class "Default")
      (node (ref "FPC11") (pin "1") (pinfunction "1_1") (pintype "passive"))
      (node (ref "L13") (pin "13") (pinfunction "2Q1_13") (pintype "tri_state"))
    )
    (net (code "223") (name "/FPC11_2") (class "Default")
      (node (ref "FPC11") (pin "2") (pinfunction "1_2") (pintype "passive"))
      (node (ref "L13") (pin "14") (pinfunction "2Q2_14") (pintype "tri_state"))
    )
    (net (code "224") (name "/FPC11_3") (class "Default")
      (node (ref "FPC11") (pin "3") (pinfunction "1_3") (pintype "passive"))
      (node (ref "L13") (pin "16") (pinfunction "2Q3_16") (pintype "tri_state"))
    )
    (net (code "225") (name "/FPC11_4") (class "Default")
      (node (ref "FPC11") (pin "4") (pinfunction "1_4") (pintype "passive"))
      (node (ref "L13") (pin "17") (pinfunction "2Q4_17") (pintype "tri_state"))
    )
    (net (code "226") (name "/FPC11_5") (class "Default")
      (node (ref "FPC11") (pin "5") (pinfunction "1_5") (pintype "passive"))
      (node (ref "L13") (pin "19") (pinfunction "2Q5_19") (pintype "tri_state"))
    )
    (net (code "227") (name "/FPC11_6") (class "Default")
      (node (ref "FPC11") (pin "6") (pinfunction "1_6") (pintype "passive"))
      (node (ref "L13") (pin "20") (pinfunction "2Q6_20") (pintype "tri_state"))
    )
    (net (code "228") (name "/FPC11_7") (class "Default")
      (node (ref "FPC11") (pin "7") (pinfunction "1_7") (pintype "passive"))
      (node (ref "L13") (pin "22") (pinfunction "2Q7_22") (pintype "tri_state"))
    )
    (net (code "229") (name "/FPC11_8") (class "Default")
      (node (ref "FPC11") (pin "8") (pinfunction "1_8") (pintype "passive"))
      (node (ref "L13") (pin "23") (pinfunction "2Q8_23") (pintype "tri_state"))
    )
    (net (code "230") (name "/FPC11_9") (class "Default")
      (node (ref "FPC11") (pin "9") (pinfunction "1_9") (pintype "passive"))
      (node (ref "L14") (pin "2") (pinfunction "1Q1_2") (pintype "tri_state"))
    )
    (net (code "231") (name "/FPC11_10") (class "Default")
      (node (ref "FPC11") (pin "10") (pinfunction "1_10") (pintype "passive"))
      (node (ref "L14") (pin "3") (pinfunction "1Q2_3") (pintype "tri_state"))
    )
    (net (code "232") (name "/FPC11_11") (class "Default")
      (node (ref "FPC11") (pin "11") (pinfunction "1_11") (pintype "passive"))
      (node (ref "L14") (pin "5") (pinfunction "1Q3_5") (pintype "tri_state"))
    )
    (net (code "233") (name "/FPC11_12") (class "Default")
      (node (ref "FPC11") (pin "12") (pinfunction "1_12") (pintype "passive"))
      (node (ref "L14") (pin "6") (pinfunction "1Q4_6") (pintype "tri_state"))
    )
    (net (code "234") (name "/FPC11_13") (class "Default")
      (node (ref "FPC11") (pin "13") (pinfunction "1_13") (pintype "passive"))
      (node (ref "L14") (pin "8") (pinfunction "1Q5_8") (pintype "tri_state"))
    )
    (net (code "235") (name "/FPC11_14") (class "Default")
      (node (ref "FPC11") (pin "14") (pinfunction "1_14") (pintype "passive"))
      (node (ref "L14") (pin "9") (pinfunction "1Q6_9") (pintype "tri_state"))
    )
    (net (code "236") (name "/FPC11_15") (class "Default")
      (node (ref "FPC11") (pin "15") (pinfunction "1_15") (pintype "passive"))
      (node (ref "L14") (pin "11") (pinfunction "1Q7_11") (pintype "tri_state"))
    )
    (net (code "237") (name "/FPC11_16") (class "Default")
      (node (ref "FPC11") (pin "16") (pinfunction "1_16") (pintype "passive"))
      (node (ref "L14") (pin "12") (pinfunction "1Q8_12") (pintype "tri_state"))
    )
    (net (code "238") (name "/FPC11_17") (class "Default")
      (node (ref "FPC11") (pin "17") (pinfunction "1_17") (pintype "passive"))
      (node (ref "L14") (pin "13") (pinfunction "2Q1_13") (pintype "tri_state"))
    )
    (net (code "239") (name "/FPC11_18") (class "Default")
      (node (ref "FPC11") (pin "18") (pinfunction "1_18") (pintype "passive"))
      (node (ref "L14") (pin "14") (pinfunction "2Q2_14") (pintype "tri_state"))
    )
    (net (code "240") (name "/FPC11_19") (class "Default")
      (node (ref "FPC11") (pin "19") (pinfunction "1_19") (pintype "passive"))
      (node (ref "L14") (pin "16") (pinfunction "2Q3_16") (pintype "tri_state"))
    )
    (net (code "241") (name "/FPC11_20") (class "Default")
      (node (ref "FPC11") (pin "20") (pinfunction "1_20") (pintype "passive"))
      (node (ref "L14") (pin "17") (pinfunction "2Q4_17") (pintype "tri_state"))
    )
    (net (code "242") (name "/FPC12_1") (class "Default")
      (node (ref "FPC12") (pin "1") (pinfunction "1_1") (pintype "passive"))
      (node (ref "L14") (pin "19") (pinfunction "2Q5_19") (pintype "tri_state"))
    )
    (net (code "243") (name "/FPC12_2") (class "Default")
      (node (ref "FPC12") (pin "2") (pinfunction "1_2") (pintype "passive"))
      (node (ref "L14") (pin "20") (pinfunction "2Q6_20") (pintype "tri_state"))
    )
    (net (code "244") (name "/FPC12_3") (class "Default")
      (node (ref "FPC12") (pin "3") (pinfunction "1_3") (pintype "passive"))
      (node (ref "L14") (pin "22") (pinfunction "2Q7_22") (pintype "tri_state"))
    )
    (net (code "245") (name "/FPC12_4") (class "Default")
      (node (ref "FPC12") (pin "4") (pinfunction "1_4") (pintype "passive"))
      (node (ref "L14") (pin "23") (pinfunction "2Q8_23") (pintype "tri_state"))
    )
    (net (code "246") (name "/FPC12_5") (class "Default")
      (node (ref "FPC12") (pin "5") (pinfunction "1_5") (pintype "passive"))
      (node (ref "L15") (pin "2") (pinfunction "1Q1_2") (pintype "tri_state"))
    )
    (net (code "247") (name "/FPC12_6") (class "Default")
      (node (ref "FPC12") (pin "6") (pinfunction "1_6") (pintype "passive"))
      (node (ref "L15") (pin "3") (pinfunction "1Q2_3") (pintype "tri_state"))
    )
    (net (code "248") (name "/FPC12_7") (class "Default")
      (node (ref "FPC12") (pin "7") (pinfunction "1_7") (pintype "passive"))
      (node (ref "L15") (pin "5") (pinfunction "1Q3_5") (pintype "tri_state"))
    )
    (net (code "249") (name "/FPC12_8") (class "Default")
      (node (ref "FPC12") (pin "8") (pinfunction "1_8") (pintype "passive"))
      (node (ref "L15") (pin "6") (pinfunction "1Q4_6") (pintype "tri_state"))
    )
    (net (code "250") (name "/FPC12_9") (class "Default")
      (node (ref "FPC12") (pin "9") (pinfunction "1_9") (pintype "passive"))
      (node (ref "L15") (pin "8") (pinfunction "1Q5_8") (pintype "tri_state"))
    )
    (net (code "251") (name "/FPC12_10") (class "Default")
      (node (ref "FPC12") (pin "10") (pinfunction "1_10") (pintype "passive"))
      (node (ref "L15") (pin "9") (pinfunction "1Q6_9") (pintype "tri_state"))
    )
    (net (code "252") (name "/FPC12_11") (class "Default")
      (node (ref "FPC12") (pin "11") (pinfunction "1_11") (pintype "passive"))
      (node (ref "L15") (pin "11") (pinfunction "1Q7_11") (pintype "tri_state"))
    )
    (net (code "253") (name "/FPC12_12") (class "Default")
      (node (ref "FPC12") (pin "12") (pinfunction "1_12") (pintype "passive"))
      (node (ref "L15") (pin "12") (pinfunction "1Q8_12") (pintype "tri_state"))
    )
    (net (code "254") (name "/FPC12_13") (class "Default")
      (node (ref "FPC12") (pin "13") (pinfunction "1_13") (pintype "passive"))
      (node (ref "L15") (pin "13") (pinfunction "2Q1_13") (pintype "tri_state"))
    )
    (net (code "255") (name "/FPC12_14") (class "Default")
      (node (ref "FPC12") (pin "14") (pinfunction "1_14") (pintype "passive"))
      (node (ref "L15") (pin "14") (pinfunction "2Q2_14") (pintype "tri_state"))
    )
    (net (code "256") (name "/FPC12_15") (class "Default")
      (node (ref "FPC12") (pin "15") (pinfunction "1_15") (pintype "passive"))
      (node (ref "L15") (pin "16") (pinfunction "2Q3_16") (pintype "tri_state"))
    )
    (net (code "257") (name "/FPC12_16") (class "Default")
      (node (ref "FPC12") (pin "16") (pinfunction "1_16") (pintype "passive"))
      (node (ref "L15") (pin "17") (pinfunction "2Q4_17") (pintype "tri_state"))
    )
    (net (code "258") (name "/FPC12_17") (class "Default")
      (node (ref "FPC12") (pin "17") (pinfunction "1_17") (pintype "passive"))
      (node (ref "L15") (pin "19") (pinfunction "2Q5_19") (pintype "tri_state"))
    )
    (net (code "259") (name "/FPC12_18") (class "Default")
      (node (ref "FPC12") (pin "18") (pinfunction "1_18") (pintype "passive"))
      (node (ref "L15") (pin "20") (pinfunction "2Q6_20") (pintype "tri_state"))
    )
    (net (code "260") (name "/FPC12_19") (class "Default")
      (node (ref "FPC12") (pin "19") (pinfunction "1_19") (pintype "passive"))
      (node (ref "L15") (pin "22") (pinfunction "2Q7_22") (pintype "tri_state"))
    )
    (net (code "261") (name "/FPC12_20") (class "Default")
      (node (ref "FPC12") (pin "20") (pinfunction "1_20") (pintype "passive"))
      (node (ref "L15") (pin "23") (pinfunction "2Q8_23") (pintype "tri_state"))
    )
    (net (code "262") (name "/FPC13_1") (class "Default")
      (node (ref "FPC13") (pin "1") (pinfunction "1_1") (pintype "passive"))
      (node (ref "L16") (pin "2") (pinfunction "1Q1_2") (pintype "tri_state"))
    )
    (net (code "263") (name "/FPC13_2") (class "Default")
      (node (ref "FPC13") (pin "2") (pinfunction "1_2") (pintype "passive"))
      (node (ref "L16") (pin "3") (pinfunction "1Q2_3") (pintype "tri_state"))
    )
    (net (code "264") (name "/FPC13_3") (class "Default")
      (node (ref "FPC13") (pin "3") (pinfunction "1_3") (pintype "passive"))
      (node (ref "L16") (pin "5") (pinfunction "1Q3_5") (pintype "tri_state"))
    )
    (net (code "265") (name "/FPC13_4") (class "Default")
      (node (ref "FPC13") (pin "4") (pinfunction "1_4") (pintype "passive"))
      (node (ref "L16") (pin "6") (pinfunction "1Q4_6") (pintype "tri_state"))
    )
    (net (code "266") (name "/FPC13_5") (class "Default")
      (node (ref "FPC13") (pin "5") (pinfunction "1_5") (pintype "passive"))
      (node (ref "L16") (pin "8") (pinfunction "1Q5_8") (pintype "tri_state"))
    )
    (net (code "267") (name "/FPC13_6") (class "Default")
      (node (ref "FPC13") (pin "6") (pinfunction "1_6") (pintype "passive"))
      (node (ref "L16") (pin "9") (pinfunction "1Q6_9") (pintype "tri_state"))
    )
    (net (code "268") (name "/FPC13_7") (class "Default")
      (node (ref "FPC13") (pin "7") (pinfunction "1_7") (pintype "passive"))
      (node (ref "L16") (pin "11") (pinfunction "1Q7_11") (pintype "tri_state"))
    )
    (net (code "269") (name "/FPC13_8") (class "Default")
      (node (ref "FPC13") (pin "8") (pinfunction "1_8") (pintype "passive"))
      (node (ref "L16") (pin "12") (pinfunction "1Q8_12") (pintype "tri_state"))
    )
    (net (code "270") (name "/FPC13_9") (class "Default")
      (node (ref "FPC13") (pin "9") (pinfunction "1_9") (pintype "passive"))
      (node (ref "L16") (pin "13") (pinfunction "2Q1_13") (pintype "tri_state"))
    )
    (net (code "271") (name "/FPC13_10") (class "Default")
      (node (ref "FPC13") (pin "10") (pinfunction "1_10") (pintype "passive"))
      (node (ref "L16") (pin "14") (pinfunction "2Q2_14") (pintype "tri_state"))
    )
    (net (code "272") (name "/FPC13_11") (class "Default")
      (node (ref "FPC13") (pin "11") (pinfunction "1_11") (pintype "passive"))
      (node (ref "L16") (pin "16") (pinfunction "2Q3_16") (pintype "tri_state"))
    )
    (net (code "273") (name "/FPC13_12") (class "Default")
      (node (ref "FPC13") (pin "12") (pinfunction "1_12") (pintype "passive"))
      (node (ref "L16") (pin "17") (pinfunction "2Q4_17") (pintype "tri_state"))
    )
    (net (code "274") (name "/FPC13_13") (class "Default")
      (node (ref "FPC13") (pin "13") (pinfunction "1_13") (pintype "passive"))
      (node (ref "L16") (pin "19") (pinfunction "2Q5_19") (pintype "tri_state"))
    )
    (net (code "275") (name "/FPC13_14") (class "Default")
      (node (ref "FPC13") (pin "14") (pinfunction "1_14") (pintype "passive"))
      (node (ref "L16") (pin "20") (pinfunction "2Q6_20") (pintype "tri_state"))
    )
    (net (code "276") (name "/FPC13_15") (class "Default")
      (node (ref "FPC13") (pin "15") (pinfunction "1_15") (pintype "passive"))
      (node (ref "L16") (pin "22") (pinfunction "2Q7_22") (pintype "tri_state"))
    )
    (net (code "277") (name "/FPC13_16") (class "Default")
      (node (ref "FPC13") (pin "16") (pinfunction "1_16") (pintype "passive"))
      (node (ref "L16") (pin "23") (pinfunction "2Q8_23") (pintype "tri_state"))
    )
    (net (code "278") (name "/FPC13_17") (class "Default")
      (node (ref "FPC13") (pin "17") (pinfunction "1_17") (pintype "passive"))
      (node (ref "L17") (pin "2") (pinfunction "1Q1_2") (pintype "tri_state"))
    )
    (net (code "279") (name "/FPC13_18") (class "Default")
      (node (ref "FPC13") (pin "18") (pinfunction "1_18") (pintype "passive"))
      (node (ref "L17") (pin "3") (pinfunction "1Q2_3") (pintype "tri_state"))
    )
    (net (code "280") (name "/FPC13_19") (class "Default")
      (node (ref "FPC13") (pin "19") (pinfunction "1_19") (pintype "passive"))
      (node (ref "L17") (pin "5") (pinfunction "1Q3_5") (pintype "tri_state"))
    )
    (net (code "281") (name "/FPC13_20") (class "Default")
      (node (ref "FPC13") (pin "20") (pinfunction "1_20") (pintype "passive"))
      (node (ref "L17") (pin "6") (pinfunction "1Q4_6") (pintype "tri_state"))
    )
    (net (code "282") (name "/FPC14_1") (class "Default")
      (node (ref "FPC14") (pin "1") (pinfunction "1_1") (pintype "passive"))
      (node (ref "L17") (pin "8") (pinfunction "1Q5_8") (pintype "tri_state"))
    )
    (net (code "283") (name "/FPC14_2") (class "Default")
      (node (ref "FPC14") (pin "2") (pinfunction "1_2") (pintype "passive"))
      (node (ref "L17") (pin "9") (pinfunction "1Q6_9") (pintype "tri_state"))
    )
    (net (code "284") (name "/FPC14_3") (class "Default")
      (node (ref "FPC14") (pin "3") (pinfunction "1_3") (pintype "passive"))
      (node (ref "L17") (pin "11") (pinfunction "1Q7_11") (pintype "tri_state"))
    )
    (net (code "285") (name "/FPC14_4") (class "Default")
      (node (ref "FPC14") (pin "4") (pinfunction "1_4") (pintype "passive"))
      (node (ref "L17") (pin "12") (pinfunction "1Q8_12") (pintype "tri_state"))
    )
    (net (code "286") (name "/FPC14_5") (class "Default")
      (node (ref "FPC14") (pin "5") (pinfunction "1_5") (pintype "passive"))
      (node (ref "L17") (pin "13") (pinfunction "2Q1_13") (pintype "tri_state"))
    )
    (net (code "287") (name "/FPC14_6") (class "Default")
      (node (ref "FPC14") (pin "6") (pinfunction "1_6") (pintype "passive"))
      (node (ref "L17") (pin "14") (pinfunction "2Q2_14") (pintype "tri_state"))
    )
    (net (code "288") (name "/FPC14_7") (class "Default")
      (node (ref "FPC14") (pin "7") (pinfunction "1_7") (pintype "passive"))
      (node (ref "L17") (pin "16") (pinfunction "2Q3_16") (pintype "tri_state"))
    )
    (net (code "289") (name "/FPC14_8") (class "Default")
      (node (ref "FPC14") (pin "8") (pinfunction "1_8") (pintype "passive"))
      (node (ref "L17") (pin "17") (pinfunction "2Q4_17") (pintype "tri_state"))
    )
    (net (code "290") (name "/FPC14_9") (class "Default")
      (node (ref "FPC14") (pin "9") (pinfunction "1_9") (pintype "passive"))
      (node (ref "L17") (pin "19") (pinfunction "2Q5_19") (pintype "tri_state"))
    )
    (net (code "291") (name "/FPC14_10") (class "Default")
      (node (ref "FPC14") (pin "10") (pinfunction "1_10") (pintype "passive"))
      (node (ref "L17") (pin "20") (pinfunction "2Q6_20") (pintype "tri_state"))
    )
    (net (code "292") (name "/FPC14_11") (class "Default")
      (node (ref "FPC14") (pin "11") (pinfunction "1_11") (pintype "passive"))
      (node (ref "L17") (pin "22") (pinfunction "2Q7_22") (pintype "tri_state"))
    )
    (net (code "293") (name "/FPC14_12") (class "Default")
      (node (ref "FPC14") (pin "12") (pinfunction "1_12") (pintype "passive"))
      (node (ref "L17") (pin "23") (pinfunction "2Q8_23") (pintype "tri_state"))
    )
    (net (code "294") (name "/FPC14_13") (class "Default")
      (node (ref "FPC14") (pin "13") (pinfunction "1_13") (pintype "passive"))
      (node (ref "L18") (pin "2") (pinfunction "1Q1_2") (pintype "tri_state"))
    )
    (net (code "295") (name "/FPC14_14") (class "Default")
      (node (ref "FPC14") (pin "14") (pinfunction "1_14") (pintype "passive"))
      (node (ref "L18") (pin "3") (pinfunction "1Q2_3") (pintype "tri_state"))
    )
    (net (code "296") (name "/FPC14_15") (class "Default")
      (node (ref "FPC14") (pin "15") (pinfunction "1_15") (pintype "passive"))
      (node (ref "L18") (pin "5") (pinfunction "1Q3_5") (pintype "tri_state"))
    )
    (net (code "297") (name "/FPC14_16") (class "Default")
      (node (ref "FPC14") (pin "16") (pinfunction "1_16") (pintype "passive"))
      (node (ref "L18") (pin "6") (pinfunction "1Q4_6") (pintype "tri_state"))
    )
    (net (code "298") (name "/FPC14_17") (class "Default")
      (node (ref "FPC14") (pin "17") (pinfunction "1_17") (pintype "passive"))
      (node (ref "L18") (pin "8") (pinfunction "1Q5_8") (pintype "tri_state"))
    )
    (net (code "299") (name "/FPC14_18") (class "Default")
      (node (ref "FPC14") (pin "18") (pinfunction "1_18") (pintype "passive"))
      (node (ref "L18") (pin "9") (pinfunction "1Q6_9") (pintype "tri_state"))
    )
    (net (code "300") (name "/FPC14_19") (class "Default")
      (node (ref "FPC14") (pin "19") (pinfunction "1_19") (pintype "passive"))
      (node (ref "L18") (pin "11") (pinfunction "1Q7_11") (pintype "tri_state"))
    )
    (net (code "301") (name "/FPC14_20") (class "Default")
      (node (ref "FPC14") (pin "20") (pinfunction "1_20") (pintype "passive"))
      (node (ref "L18") (pin "12") (pinfunction "1Q8_12") (pintype "tri_state"))
    )
    (net (code "302") (name "/FPC15_1") (class "Default")
      (node (ref "FPC15") (pin "1") (pinfunction "1_1") (pintype "passive"))
      (node (ref "L18") (pin "13") (pinfunction "2Q1_13") (pintype "tri_state"))
    )
    (net (code "303") (name "/FPC15_2") (class "Default")
      (node (ref "FPC15") (pin "2") (pinfunction "1_2") (pintype "passive"))
      (node (ref "L18") (pin "14") (pinfunction "2Q2_14") (pintype "tri_state"))
    )
    (net (code "304") (name "/FPC15_3") (class "Default")
      (node (ref "FPC15") (pin "3") (pinfunction "1_3") (pintype "passive"))
      (node (ref "L18") (pin "16") (pinfunction "2Q3_16") (pintype "tri_state"))
    )
    (net (code "305") (name "/FPC15_4") (class "Default")
      (node (ref "FPC15") (pin "4") (pinfunction "1_4") (pintype "passive"))
      (node (ref "L18") (pin "17") (pinfunction "2Q4_17") (pintype "tri_state"))
    )
    (net (code "306") (name "/FPC15_5") (class "Default")
      (node (ref "FPC15") (pin "5") (pinfunction "1_5") (pintype "passive"))
      (node (ref "L18") (pin "19") (pinfunction "2Q5_19") (pintype "tri_state"))
    )
    (net (code "307") (name "/FPC15_6") (class "Default")
      (node (ref "FPC15") (pin "6") (pinfunction "1_6") (pintype "passive"))
      (node (ref "L18") (pin "20") (pinfunction "2Q6_20") (pintype "tri_state"))
    )
    (net (code "308") (name "/FPC15_7") (class "Default")
      (node (ref "FPC15") (pin "7") (pinfunction "1_7") (pintype "passive"))
      (node (ref "L18") (pin "22") (pinfunction "2Q7_22") (pintype "tri_state"))
    )
    (net (code "309") (name "/FPC15_8") (class "Default")
      (node (ref "FPC15") (pin "8") (pinfunction "1_8") (pintype "passive"))
      (node (ref "L18") (pin "23") (pinfunction "2Q8_23") (pintype "tri_state"))
    )
    (net (code "310") (name "/FPC15_9") (class "Default")
      (node (ref "FPC15") (pin "9") (pinfunction "1_9") (pintype "passive"))
      (node (ref "L19") (pin "2") (pinfunction "1Q1_2") (pintype "tri_state"))
    )
    (net (code "311") (name "/FPC15_10") (class "Default")
      (node (ref "FPC15") (pin "10") (pinfunction "1_10") (pintype "passive"))
      (node (ref "L19") (pin "3") (pinfunction "1Q2_3") (pintype "tri_state"))
    )
    (net (code "312") (name "/FPC15_11") (class "Default")
      (node (ref "FPC15") (pin "11") (pinfunction "1_11") (pintype "passive"))
      (node (ref "L19") (pin "5") (pinfunction "1Q3_5") (pintype "tri_state"))
    )
    (net (code "313") (name "/FPC15_12") (class "Default")
      (node (ref "FPC15") (pin "12") (pinfunction "1_12") (pintype "passive"))
      (node (ref "L19") (pin "6") (pinfunction "1Q4_6") (pintype "tri_state"))
    )
    (net (code "314") (name "/FPC15_13") (class "Default")
      (node (ref "FPC15") (pin "13") (pinfunction "1_13") (pintype "passive"))
      (node (ref "L19") (pin "8") (pinfunction "1Q5_8") (pintype "tri_state"))
    )
    (net (code "315") (name "/FPC15_14") (class "Default")
      (node (ref "FPC15") (pin "14") (pinfunction "1_14") (pintype "passive"))
      (node (ref "L19") (pin "9") (pinfunction "1Q6_9") (pintype "tri_state"))
    )
    (net (code "316") (name "/FPC15_15") (class "Default")
      (node (ref "FPC15") (pin "15") (pinfunction "1_15") (pintype "passive"))
      (node (ref "L19") (pin "11") (pinfunction "1Q7_11") (pintype "tri_state"))
    )
    (net (code "317") (name "/FPC15_16") (class "Default")
      (node (ref "FPC15") (pin "16") (pinfunction "1_16") (pintype "passive"))
      (node (ref "L19") (pin "12") (pinfunction "1Q8_12") (pintype "tri_state"))
    )
    (net (code "318") (name "/FPC15_17") (class "Default")
      (node (ref "FPC15") (pin "17") (pinfunction "1_17") (pintype "passive"))
      (node (ref "L19") (pin "13") (pinfunction "2Q1_13") (pintype "tri_state"))
    )
    (net (code "319") (name "/FPC15_18") (class "Default")
      (node (ref "FPC15") (pin "18") (pinfunction "1_18") (pintype "passive"))
      (node (ref "L19") (pin "14") (pinfunction "2Q2_14") (pintype "tri_state"))
    )
    (net (code "320") (name "/FPC15_19") (class "Default")
      (node (ref "FPC15") (pin "19") (pinfunction "1_19") (pintype "passive"))
      (node (ref "L19") (pin "16") (pinfunction "2Q3_16") (pintype "tri_state"))
    )
    (net (code "321") (name "/FPC15_20") (class "Default")
      (node (ref "FPC15") (pin "20") (pinfunction "1_20") (pintype "passive"))
      (node (ref "L19") (pin "17") (pinfunction "2Q4_17") (pintype "tri_state"))
    )
    (net (code "322") (name "/FPC16_1") (class "Default")
      (node (ref "FPC16") (pin "1") (pinfunction "1_1") (pintype "passive"))
      (node (ref "L19") (pin "19") (pinfunction "2Q5_19") (pintype "tri_state"))
    )
    (net (code "323") (name "/FPC16_2") (class "Default")
      (node (ref "FPC16") (pin "2") (pinfunction "1_2") (pintype "passive"))
      (node (ref "L19") (pin "20") (pinfunction "2Q6_20") (pintype "tri_state"))
    )
    (net (code "324") (name "/FPC16_3") (class "Default")
      (node (ref "FPC16") (pin "3") (pinfunction "1_3") (pintype "passive"))
      (node (ref "L19") (pin "22") (pinfunction "2Q7_22") (pintype "tri_state"))
    )
    (net (code "325") (name "/FPC16_4") (class "Default")
      (node (ref "FPC16") (pin "4") (pinfunction "1_4") (pintype "passive"))
      (node (ref "L19") (pin "23") (pinfunction "2Q8_23") (pintype "tri_state"))
    )
    (net (code "326") (name "/FPC16_5") (class "Default")
      (node (ref "FPC16") (pin "5") (pinfunction "1_5") (pintype "passive"))
      (node (ref "L20") (pin "2") (pinfunction "1Q1_2") (pintype "tri_state"))
    )
    (net (code "327") (name "/FPC16_6") (class "Default")
      (node (ref "FPC16") (pin "6") (pinfunction "1_6") (pintype "passive"))
      (node (ref "L20") (pin "3") (pinfunction "1Q2_3") (pintype "tri_state"))
    )
    (net (code "328") (name "/FPC16_7") (class "Default")
      (node (ref "FPC16") (pin "7") (pinfunction "1_7") (pintype "passive"))
      (node (ref "L20") (pin "5") (pinfunction "1Q3_5") (pintype "tri_state"))
    )
    (net (code "329") (name "/FPC16_8") (class "Default")
      (node (ref "FPC16") (pin "8") (pinfunction "1_8") (pintype "passive"))
      (node (ref "L20") (pin "6") (pinfunction "1Q4_6") (pintype "tri_state"))
    )
    (net (code "330") (name "/FPC16_9") (class "Default")
      (node (ref "FPC16") (pin "9") (pinfunction "1_9") (pintype "passive"))
      (node (ref "L20") (pin "8") (pinfunction "1Q5_8") (pintype "tri_state"))
    )
    (net (code "331") (name "/FPC16_10") (class "Default")
      (node (ref "FPC16") (pin "10") (pinfunction "1_10") (pintype "passive"))
      (node (ref "L20") (pin "9") (pinfunction "1Q6_9") (pintype "tri_state"))
    )
    (net (code "332") (name "/FPC16_11") (class "Default")
      (node (ref "FPC16") (pin "11") (pinfunction "1_11") (pintype "passive"))
      (node (ref "L20") (pin "11") (pinfunction "1Q7_11") (pintype "tri_state"))
    )
    (net (code "333") (name "/FPC16_12") (class "Default")
      (node (ref "FPC16") (pin "12") (pinfunction "1_12") (pintype "passive"))
      (node (ref "L20") (pin "12") (pinfunction "1Q8_12") (pintype "tri_state"))
    )
    (net (code "334") (name "/FPC16_13") (class "Default")
      (node (ref "FPC16") (pin "13") (pinfunction "1_13") (pintype "passive"))
      (node (ref "L20") (pin "13") (pinfunction "2Q1_13") (pintype "tri_state"))
    )
    (net (code "335") (name "/FPC16_14") (class "Default")
      (node (ref "FPC16") (pin "14") (pinfunction "1_14") (pintype "passive"))
      (node (ref "L20") (pin "14") (pinfunction "2Q2_14") (pintype "tri_state"))
    )
    (net (code "336") (name "/FPC16_15") (class "Default")
      (node (ref "FPC16") (pin "15") (pinfunction "1_15") (pintype "passive"))
      (node (ref "L20") (pin "16") (pinfunction "2Q3_16") (pintype "tri_state"))
    )
    (net (code "337") (name "/FPC16_16") (class "Default")
      (node (ref "FPC16") (pin "16") (pinfunction "1_16") (pintype "passive"))
      (node (ref "L20") (pin "17") (pinfunction "2Q4_17") (pintype "tri_state"))
    )
    (net (code "338") (name "/FPC16_17") (class "Default")
      (node (ref "FPC16") (pin "17") (pinfunction "1_17") (pintype "passive"))
      (node (ref "L20") (pin "19") (pinfunction "2Q5_19") (pintype "tri_state"))
    )
    (net (code "339") (name "/FPC16_18") (class "Default")
      (node (ref "FPC16") (pin "18") (pinfunction "1_18") (pintype "passive"))
      (node (ref "L20") (pin "20") (pinfunction "2Q6_20") (pintype "tri_state"))
    )
    (net (code "340") (name "/FPC16_19") (class "Default")
      (node (ref "FPC16") (pin "19") (pinfunction "1_19") (pintype "passive"))
      (node (ref "L20") (pin "22") (pinfunction "2Q7_22") (pintype "tri_state"))
    )
    (net (code "341") (name "/FPC16_20") (class "Default")
      (node (ref "FPC16") (pin "20") (pinfunction "1_20") (pintype "passive"))
      (node (ref "L20") (pin "23") (pinfunction "2Q8_23") (pintype "tri_state"))
    )
    (net (code "342") (name "/FPC17_1") (class "Default")
      (node (ref "FPC17") (pin "1") (pinfunction "1_1") (pintype "passive"))
      (node (ref "L21") (pin "2") (pinfunction "1Q1_2") (pintype "tri_state"))
    )
    (net (code "343") (name "/FPC17_2") (class "Default")
      (node (ref "FPC17") (pin "2") (pinfunction "1_2") (pintype "passive"))
      (node (ref "L21") (pin "3") (pinfunction "1Q2_3") (pintype "tri_state"))
    )
    (net (code "344") (name "/FPC17_3") (class "Default")
      (node (ref "FPC17") (pin "3") (pinfunction "1_3") (pintype "passive"))
      (node (ref "L21") (pin "5") (pinfunction "1Q3_5") (pintype "tri_state"))
    )
    (net (code "345") (name "/FPC17_4") (class "Default")
      (node (ref "FPC17") (pin "4") (pinfunction "1_4") (pintype "passive"))
      (node (ref "L21") (pin "6") (pinfunction "1Q4_6") (pintype "tri_state"))
    )
    (net (code "346") (name "/FPC17_5") (class "Default")
      (node (ref "FPC17") (pin "5") (pinfunction "1_5") (pintype "passive"))
      (node (ref "L21") (pin "8") (pinfunction "1Q5_8") (pintype "tri_state"))
    )
    (net (code "347") (name "/FPC17_6") (class "Default")
      (node (ref "FPC17") (pin "6") (pinfunction "1_6") (pintype "passive"))
      (node (ref "L21") (pin "9") (pinfunction "1Q6_9") (pintype "tri_state"))
    )
    (net (code "348") (name "/FPC17_7") (class "Default")
      (node (ref "FPC17") (pin "7") (pinfunction "1_7") (pintype "passive"))
      (node (ref "L21") (pin "11") (pinfunction "1Q7_11") (pintype "tri_state"))
    )
    (net (code "349") (name "/FPC17_8") (class "Default")
      (node (ref "FPC17") (pin "8") (pinfunction "1_8") (pintype "passive"))
      (node (ref "L21") (pin "12") (pinfunction "1Q8_12") (pintype "tri_state"))
    )
    (net (code "350") (name "/FPC17_9") (class "Default")
      (node (ref "FPC17") (pin "9") (pinfunction "1_9") (pintype "passive"))
      (node (ref "L21") (pin "13") (pinfunction "2Q1_13") (pintype "tri_state"))
    )
    (net (code "351") (name "/FPC17_10") (class "Default")
      (node (ref "FPC17") (pin "10") (pinfunction "1_10") (pintype "passive"))
      (node (ref "L21") (pin "14") (pinfunction "2Q2_14") (pintype "tri_state"))
    )
    (net (code "352") (name "/FPC17_11") (class "Default")
      (node (ref "FPC17") (pin "11") (pinfunction "1_11") (pintype "passive"))
      (node (ref "L21") (pin "16") (pinfunction "2Q3_16") (pintype "tri_state"))
    )
    (net (code "353") (name "/FPC17_12") (class "Default")
      (node (ref "FPC17") (pin "12") (pinfunction "1_12") (pintype "passive"))
      (node (ref "L21") (pin "17") (pinfunction "2Q4_17") (pintype "tri_state"))
    )
    (net (code "354") (name "/FPC17_13") (class "Default")
      (node (ref "FPC17") (pin "13") (pinfunction "1_13") (pintype "passive"))
      (node (ref "L21") (pin "19") (pinfunction "2Q5_19") (pintype "tri_state"))
    )
    (net (code "355") (name "/FPC17_14") (class "Default")
      (node (ref "FPC17") (pin "14") (pinfunction "1_14") (pintype "passive"))
      (node (ref "L21") (pin "20") (pinfunction "2Q6_20") (pintype "tri_state"))
    )
    (net (code "356") (name "/FPC17_15") (class "Default")
      (node (ref "FPC17") (pin "15") (pinfunction "1_15") (pintype "passive"))
      (node (ref "L21") (pin "22") (pinfunction "2Q7_22") (pintype "tri_state"))
    )
    (net (code "357") (name "/FPC17_16") (class "Default")
      (node (ref "FPC17") (pin "16") (pinfunction "1_16") (pintype "passive"))
      (node (ref "L21") (pin "23") (pinfunction "2Q8_23") (pintype "tri_state"))
    )
    (net (code "358") (name "/FPC17_17") (class "Default")
      (node (ref "FPC17") (pin "17") (pinfunction "1_17") (pintype "passive"))
      (node (ref "L22") (pin "2") (pinfunction "1Q1_2") (pintype "tri_state"))
    )
    (net (code "359") (name "/FPC17_18") (class "Default")
      (node (ref "FPC17") (pin "18") (pinfunction "1_18") (pintype "passive"))
      (node (ref "L22") (pin "3") (pinfunction "1Q2_3") (pintype "tri_state"))
    )
    (net (code "360") (name "/FPC17_19") (class "Default")
      (node (ref "FPC17") (pin "19") (pinfunction "1_19") (pintype "passive"))
      (node (ref "L22") (pin "5") (pinfunction "1Q3_5") (pintype "tri_state"))
    )
    (net (code "361") (name "/FPC17_20") (class "Default")
      (node (ref "FPC17") (pin "20") (pinfunction "1_20") (pintype "passive"))
      (node (ref "L22") (pin "6") (pinfunction "1Q4_6") (pintype "tri_state"))
    )
    (net (code "362") (name "/FPC18_1") (class "Default")
      (node (ref "FPC18") (pin "1") (pinfunction "1_1") (pintype "passive"))
      (node (ref "L22") (pin "8") (pinfunction "1Q5_8") (pintype "tri_state"))
    )
    (net (code "363") (name "/FPC18_2") (class "Default")
      (node (ref "FPC18") (pin "2") (pinfunction "1_2") (pintype "passive"))
      (node (ref "L22") (pin "9") (pinfunction "1Q6_9") (pintype "tri_state"))
    )
    (net (code "364") (name "/FPC18_3") (class "Default")
      (node (ref "FPC18") (pin "3") (pinfunction "1_3") (pintype "passive"))
      (node (ref "L22") (pin "11") (pinfunction "1Q7_11") (pintype "tri_state"))
    )
    (net (code "365") (name "/FPC18_4") (class "Default")
      (node (ref "FPC18") (pin "4") (pinfunction "1_4") (pintype "passive"))
      (node (ref "L22") (pin "12") (pinfunction "1Q8_12") (pintype "tri_state"))
    )
    (net (code "366") (name "/FPC18_5") (class "Default")
      (node (ref "FPC18") (pin "5") (pinfunction "1_5") (pintype "passive"))
      (node (ref "L22") (pin "13") (pinfunction "2Q1_13") (pintype "tri_state"))
    )
    (net (code "367") (name "/FPC18_6") (class "Default")
      (node (ref "FPC18") (pin "6") (pinfunction "1_6") (pintype "passive"))
      (node (ref "L22") (pin "14") (pinfunction "2Q2_14") (pintype "tri_state"))
    )
    (net (code "368") (name "/FPC18_7") (class "Default")
      (node (ref "FPC18") (pin "7") (pinfunction "1_7") (pintype "passive"))
      (node (ref "L22") (pin "16") (pinfunction "2Q3_16") (pintype "tri_state"))
    )
    (net (code "369") (name "/FPC18_8") (class "Default")
      (node (ref "FPC18") (pin "8") (pinfunction "1_8") (pintype "passive"))
      (node (ref "L22") (pin "17") (pinfunction "2Q4_17") (pintype "tri_state"))
    )
    (net (code "370") (name "/FPC18_9") (class "Default")
      (node (ref "FPC18") (pin "9") (pinfunction "1_9") (pintype "passive"))
      (node (ref "L22") (pin "19") (pinfunction "2Q5_19") (pintype "tri_state"))
    )
    (net (code "371") (name "/FPC18_10") (class "Default")
      (node (ref "FPC18") (pin "10") (pinfunction "1_10") (pintype "passive"))
      (node (ref "L22") (pin "20") (pinfunction "2Q6_20") (pintype "tri_state"))
    )
    (net (code "372") (name "/FPC18_11") (class "Default")
      (node (ref "FPC18") (pin "11") (pinfunction "1_11") (pintype "passive"))
      (node (ref "L22") (pin "22") (pinfunction "2Q7_22") (pintype "tri_state"))
    )
    (net (code "373") (name "/FPC18_12") (class "Default")
      (node (ref "FPC18") (pin "12") (pinfunction "1_12") (pintype "passive"))
      (node (ref "L22") (pin "23") (pinfunction "2Q8_23") (pintype "tri_state"))
    )
    (net (code "374") (name "/FPC18_13") (class "Default")
      (node (ref "FPC18") (pin "13") (pinfunction "1_13") (pintype "passive"))
      (node (ref "L23") (pin "2") (pinfunction "1Q1_2") (pintype "tri_state"))
    )
    (net (code "375") (name "/FPC18_14") (class "Default")
      (node (ref "FPC18") (pin "14") (pinfunction "1_14") (pintype "passive"))
      (node (ref "L23") (pin "3") (pinfunction "1Q2_3") (pintype "tri_state"))
    )
    (net (code "376") (name "/FPC18_15") (class "Default")
      (node (ref "FPC18") (pin "15") (pinfunction "1_15") (pintype "passive"))
      (node (ref "L23") (pin "5") (pinfunction "1Q3_5") (pintype "tri_state"))
    )
    (net (code "377") (name "/FPC18_16") (class "Default")
      (node (ref "FPC18") (pin "16") (pinfunction "1_16") (pintype "passive"))
      (node (ref "L23") (pin "6") (pinfunction "1Q4_6") (pintype "tri_state"))
    )
    (net (code "378") (name "/FPC18_17") (class "Default")
      (node (ref "FPC18") (pin "17") (pinfunction "1_17") (pintype "passive"))
      (node (ref "L23") (pin "8") (pinfunction "1Q5_8") (pintype "tri_state"))
    )
    (net (code "379") (name "/FPC18_18") (class "Default")
      (node (ref "FPC18") (pin "18") (pinfunction "1_18") (pintype "passive"))
      (node (ref "L23") (pin "9") (pinfunction "1Q6_9") (pintype "tri_state"))
    )
    (net (code "380") (name "/FPC18_19") (class "Default")
      (node (ref "FPC18") (pin "19") (pinfunction "1_19") (pintype "passive"))
      (node (ref "L23") (pin "11") (pinfunction "1Q7_11") (pintype "tri_state"))
    )
    (net (code "381") (name "/FPC18_20") (class "Default")
      (node (ref "FPC18") (pin "20") (pinfunction "1_20") (pintype "passive"))
      (node (ref "L23") (pin "12") (pinfunction "1Q8_12") (pintype "tri_state"))
    )
    (net (code "382") (name "/FPC19_1") (class "Default")
      (node (ref "FPC19") (pin "1") (pinfunction "1_1") (pintype "passive"))
      (node (ref "L23") (pin "13") (pinfunction "2Q1_13") (pintype "tri_state"))
    )
    (net (code "383") (name "/FPC19_2") (class "Default")
      (node (ref "FPC19") (pin "2") (pinfunction "1_2") (pintype "passive"))
      (node (ref "L23") (pin "14") (pinfunction "2Q2_14") (pintype "tri_state"))
    )
    (net (code "384") (name "/FPC19_3") (class "Default")
      (node (ref "FPC19") (pin "3") (pinfunction "1_3") (pintype "passive"))
      (node (ref "L23") (pin "16") (pinfunction "2Q3_16") (pintype "tri_state"))
    )
    (net (code "385") (name "/FPC19_4") (class "Default")
      (node (ref "FPC19") (pin "4") (pinfunction "1_4") (pintype "passive"))
      (node (ref "L23") (pin "17") (pinfunction "2Q4_17") (pintype "tri_state"))
    )
    (net (code "386") (name "/FPC19_5") (class "Default")
      (node (ref "FPC19") (pin "5") (pinfunction "1_5") (pintype "passive"))
      (node (ref "L23") (pin "19") (pinfunction "2Q5_19") (pintype "tri_state"))
    )
    (net (code "387") (name "/FPC19_6") (class "Default")
      (node (ref "FPC19") (pin "6") (pinfunction "1_6") (pintype "passive"))
      (node (ref "L23") (pin "20") (pinfunction "2Q6_20") (pintype "tri_state"))
    )
    (net (code "388") (name "/FPC19_7") (class "Default")
      (node (ref "FPC19") (pin "7") (pinfunction "1_7") (pintype "passive"))
      (node (ref "L23") (pin "22") (pinfunction "2Q7_22") (pintype "tri_state"))
    )
    (net (code "389") (name "/FPC19_8") (class "Default")
      (node (ref "FPC19") (pin "8") (pinfunction "1_8") (pintype "passive"))
      (node (ref "L23") (pin "23") (pinfunction "2Q8_23") (pintype "tri_state"))
    )
    (net (code "390") (name "/FPC19_9") (class "Default")
      (node (ref "FPC19") (pin "9") (pinfunction "1_9") (pintype "passive"))
      (node (ref "L24") (pin "2") (pinfunction "1Q1_2") (pintype "tri_state"))
    )
    (net (code "391") (name "/FPC19_10") (class "Default")
      (node (ref "FPC19") (pin "10") (pinfunction "1_10") (pintype "passive"))
      (node (ref "L24") (pin "3") (pinfunction "1Q2_3") (pintype "tri_state"))
    )
    (net (code "392") (name "/FPC19_11") (class "Default")
      (node (ref "FPC19") (pin "11") (pinfunction "1_11") (pintype "passive"))
      (node (ref "L24") (pin "5") (pinfunction "1Q3_5") (pintype "tri_state"))
    )
    (net (code "393") (name "/FPC19_12") (class "Default")
      (node (ref "FPC19") (pin "12") (pinfunction "1_12") (pintype "passive"))
      (node (ref "L24") (pin "6") (pinfunction "1Q4_6") (pintype "tri_state"))
    )
    (net (code "394") (name "/FPC19_13") (class "Default")
      (node (ref "FPC19") (pin "13") (pinfunction "1_13") (pintype "passive"))
      (node (ref "L24") (pin "8") (pinfunction "1Q5_8") (pintype "tri_state"))
    )
    (net (code "395") (name "/FPC19_14") (class "Default")
      (node (ref "FPC19") (pin "14") (pinfunction "1_14") (pintype "passive"))
      (node (ref "L24") (pin "9") (pinfunction "1Q6_9") (pintype "tri_state"))
    )
    (net (code "396") (name "/FPC19_15") (class "Default")
      (node (ref "FPC19") (pin "15") (pinfunction "1_15") (pintype "passive"))
      (node (ref "L24") (pin "11") (pinfunction "1Q7_11") (pintype "tri_state"))
    )
    (net (code "397") (name "/FPC19_16") (class "Default")
      (node (ref "FPC19") (pin "16") (pinfunction "1_16") (pintype "passive"))
      (node (ref "L24") (pin "12") (pinfunction "1Q8_12") (pintype "tri_state"))
    )
    (net (code "398") (name "/FPC19_17") (class "Default")
      (node (ref "FPC19") (pin "17") (pinfunction "1_17") (pintype "passive"))
      (node (ref "L24") (pin "13") (pinfunction "2Q1_13") (pintype "tri_state"))
    )
    (net (code "399") (name "/FPC19_18") (class "Default")
      (node (ref "FPC19") (pin "18") (pinfunction "1_18") (pintype "passive"))
      (node (ref "L24") (pin "14") (pinfunction "2Q2_14") (pintype "tri_state"))
    )
    (net (code "400") (name "/FPC19_19") (class "Default")
      (node (ref "FPC19") (pin "19") (pinfunction "1_19") (pintype "passive"))
      (node (ref "L24") (pin "16") (pinfunction "2Q3_16") (pintype "tri_state"))
    )
    (net (code "401") (name "/FPC19_20") (class "Default")
      (node (ref "FPC19") (pin "20") (pinfunction "1_20") (pintype "passive"))
      (node (ref "L24") (pin "17") (pinfunction "2Q4_17") (pintype "tri_state"))
    )
    (net (code "402") (name "/FPC20_1") (class "Default")
      (node (ref "FPC20") (pin "1") (pinfunction "1_1") (pintype "passive"))
      (node (ref "L24") (pin "19") (pinfunction "2Q5_19") (pintype "tri_state"))
    )
    (net (code "403") (name "/FPC20_2") (class "Default")
      (node (ref "FPC20") (pin "2") (pinfunction "1_2") (pintype "passive"))
      (node (ref "L24") (pin "20") (pinfunction "2Q6_20") (pintype "tri_state"))
    )
    (net (code "404") (name "/FPC20_3") (class "Default")
      (node (ref "FPC20") (pin "3") (pinfunction "1_3") (pintype "passive"))
      (node (ref "L24") (pin "22") (pinfunction "2Q7_22") (pintype "tri_state"))
    )
    (net (code "405") (name "/FPC20_4") (class "Default")
      (node (ref "FPC20") (pin "4") (pinfunction "1_4") (pintype "passive"))
      (node (ref "L24") (pin "23") (pinfunction "2Q8_23") (pintype "tri_state"))
    )
    (net (code "406") (name "/FPC20_5") (class "Default")
      (node (ref "FPC20") (pin "5") (pinfunction "1_5") (pintype "passive"))
      (node (ref "L25") (pin "2") (pinfunction "1Q1_2") (pintype "tri_state"))
    )
    (net (code "407") (name "/FPC20_6") (class "Default")
      (node (ref "FPC20") (pin "6") (pinfunction "1_6") (pintype "passive"))
      (node (ref "L25") (pin "3") (pinfunction "1Q2_3") (pintype "tri_state"))
    )
    (net (code "408") (name "/FPC20_7") (class "Default")
      (node (ref "FPC20") (pin "7") (pinfunction "1_7") (pintype "passive"))
      (node (ref "L25") (pin "5") (pinfunction "1Q3_5") (pintype "tri_state"))
    )
    (net (code "409") (name "/FPC20_8") (class "Default")
      (node (ref "FPC20") (pin "8") (pinfunction "1_8") (pintype "passive"))
      (node (ref "L25") (pin "6") (pinfunction "1Q4_6") (pintype "tri_state"))
    )
    (net (code "410") (name "/FPC20_9") (class "Default")
      (node (ref "FPC20") (pin "9") (pinfunction "1_9") (pintype "passive"))
      (node (ref "L25") (pin "8") (pinfunction "1Q5_8") (pintype "tri_state"))
    )
    (net (code "411") (name "/FPC20_10") (class "Default")
      (node (ref "FPC20") (pin "10") (pinfunction "1_10") (pintype "passive"))
      (node (ref "L25") (pin "9") (pinfunction "1Q6_9") (pintype "tri_state"))
    )
    (net (code "412") (name "/FPC20_11") (class "Default")
      (node (ref "FPC20") (pin "11") (pinfunction "1_11") (pintype "passive"))
      (node (ref "L25") (pin "11") (pinfunction "1Q7_11") (pintype "tri_state"))
    )
    (net (code "413") (name "/FPC20_12") (class "Default")
      (node (ref "FPC20") (pin "12") (pinfunction "1_12") (pintype "passive"))
      (node (ref "L25") (pin "12") (pinfunction "1Q8_12") (pintype "tri_state"))
    )
    (net (code "414") (name "/FPC20_13") (class "Default")
      (node (ref "FPC20") (pin "13") (pinfunction "1_13") (pintype "passive"))
      (node (ref "L25") (pin "13") (pinfunction "2Q1_13") (pintype "tri_state"))
    )
    (net (code "415") (name "/FPC20_14") (class "Default")
      (node (ref "FPC20") (pin "14") (pinfunction "1_14") (pintype "passive"))
      (node (ref "L25") (pin "14") (pinfunction "2Q2_14") (pintype "tri_state"))
    )
    (net (code "416") (name "/FPC20_15") (class "Default")
      (node (ref "FPC20") (pin "15") (pinfunction "1_15") (pintype "passive"))
      (node (ref "L25") (pin "16") (pinfunction "2Q3_16") (pintype "tri_state"))
    )
    (net (code "417") (name "/FPC20_16") (class "Default")
      (node (ref "FPC20") (pin "16") (pinfunction "1_16") (pintype "passive"))
      (node (ref "L25") (pin "17") (pinfunction "2Q4_17") (pintype "tri_state"))
    )
    (net (code "418") (name "/FPC20_17") (class "Default")
      (node (ref "FPC20") (pin "17") (pinfunction "1_17") (pintype "passive"))
      (node (ref "L25") (pin "19") (pinfunction "2Q5_19") (pintype "tri_state"))
    )
    (net (code "419") (name "/FPC20_18") (class "Default")
      (node (ref "FPC20") (pin "18") (pinfunction "1_18") (pintype "passive"))
      (node (ref "L25") (pin "20") (pinfunction "2Q6_20") (pintype "tri_state"))
    )
    (net (code "420") (name "/FPC20_19") (class "Default")
      (node (ref "FPC20") (pin "19") (pinfunction "1_19") (pintype "passive"))
      (node (ref "L25") (pin "22") (pinfunction "2Q7_22") (pintype "tri_state"))
    )
    (net (code "421") (name "/FPC20_20") (class "Default")
      (node (ref "FPC20") (pin "20") (pinfunction "1_20") (pintype "passive"))
      (node (ref "L25") (pin "23") (pinfunction "2Q8_23") (pintype "tri_state"))
    )
    (net (code "422") (name "/GND") (class "Default")
      (node (ref "L1") (pin "1") (pinfunction "1_~{OE}_1") (pintype "input"))
      (node (ref "L1") (pin "10") (pinfunction "1_GND_10") (pintype "power_in"))
      (node (ref "L1") (pin "15") (pinfunction "2_GND_15") (pintype "power_in"))
      (node (ref "L1") (pin "21") (pinfunction "3_GND_21") (pintype "power_in"))
      (node (ref "L1") (pin "24") (pinfunction "2_~{OE}_24") (pintype "input"))
      (node (ref "L1") (pin "28") (pinfunction "4_GND_28") (pintype "power_in"))
      (node (ref "L1") (pin "34") (pinfunction "5_GND_34") (pintype "power_in"))
      (node (ref "L1") (pin "39") (pinfunction "6_GND_39") (pintype "power_in"))
      (node (ref "L1") (pin "4") (pinfunction "7_GND_4") (pintype "power_in"))
      (node (ref "L1") (pin "45") (pinfunction "8_GND_45") (pintype "power_in"))
      (node (ref "L10") (pin "1") (pinfunction "1_~{OE}_1") (pintype "input"))
      (node (ref "L10") (pin "10") (pinfunction "1_GND_10") (pintype "power_in"))
      (node (ref "L10") (pin "15") (pinfunction "2_GND_15") (pintype "power_in"))
      (node (ref "L10") (pin "21") (pinfunction "3_GND_21") (pintype "power_in"))
      (node (ref "L10") (pin "24") (pinfunction "2_~{OE}_24") (pintype "input"))
      (node (ref "L10") (pin "28") (pinfunction "4_GND_28") (pintype "power_in"))
      (node (ref "L10") (pin "34") (pinfunction "5_GND_34") (pintype "power_in"))
      (node (ref "L10") (pin "39") (pinfunction "6_GND_39") (pintype "power_in"))
      (node (ref "L10") (pin "4") (pinfunction "7_GND_4") (pintype "power_in"))
      (node (ref "L10") (pin "45") (pinfunction "8_GND_45") (pintype "power_in"))
      (node (ref "L11") (pin "1") (pinfunction "1_~{OE}_1") (pintype "input"))
      (node (ref "L11") (pin "10") (pinfunction "1_GND_10") (pintype "power_in"))
      (node (ref "L11") (pin "15") (pinfunction "2_GND_15") (pintype "power_in"))
      (node (ref "L11") (pin "21") (pinfunction "3_GND_21") (pintype "power_in"))
      (node (ref "L11") (pin "24") (pinfunction "2_~{OE}_24") (pintype "input"))
      (node (ref "L11") (pin "28") (pinfunction "4_GND_28") (pintype "power_in"))
      (node (ref "L11") (pin "34") (pinfunction "5_GND_34") (pintype "power_in"))
      (node (ref "L11") (pin "39") (pinfunction "6_GND_39") (pintype "power_in"))
      (node (ref "L11") (pin "4") (pinfunction "7_GND_4") (pintype "power_in"))
      (node (ref "L11") (pin "45") (pinfunction "8_GND_45") (pintype "power_in"))
      (node (ref "L12") (pin "1") (pinfunction "1_~{OE}_1") (pintype "input"))
      (node (ref "L12") (pin "10") (pinfunction "1_GND_10") (pintype "power_in"))
      (node (ref "L12") (pin "15") (pinfunction "2_GND_15") (pintype "power_in"))
      (node (ref "L12") (pin "21") (pinfunction "3_GND_21") (pintype "power_in"))
      (node (ref "L12") (pin "24") (pinfunction "2_~{OE}_24") (pintype "input"))
      (node (ref "L12") (pin "28") (pinfunction "4_GND_28") (pintype "power_in"))
      (node (ref "L12") (pin "34") (pinfunction "5_GND_34") (pintype "power_in"))
      (node (ref "L12") (pin "39") (pinfunction "6_GND_39") (pintype "power_in"))
      (node (ref "L12") (pin "4") (pinfunction "7_GND_4") (pintype "power_in"))
      (node (ref "L12") (pin "45") (pinfunction "8_GND_45") (pintype "power_in"))
      (node (ref "L13") (pin "1") (pinfunction "1_~{OE}_1") (pintype "input"))
      (node (ref "L13") (pin "10") (pinfunction "1_GND_10") (pintype "power_in"))
      (node (ref "L13") (pin "15") (pinfunction "2_GND_15") (pintype "power_in"))
      (node (ref "L13") (pin "21") (pinfunction "3_GND_21") (pintype "power_in"))
      (node (ref "L13") (pin "24") (pinfunction "2_~{OE}_24") (pintype "input"))
      (node (ref "L13") (pin "28") (pinfunction "4_GND_28") (pintype "power_in"))
      (node (ref "L13") (pin "34") (pinfunction "5_GND_34") (pintype "power_in"))
      (node (ref "L13") (pin "39") (pinfunction "6_GND_39") (pintype "power_in"))
      (node (ref "L13") (pin "4") (pinfunction "7_GND_4") (pintype "power_in"))
      (node (ref "L13") (pin "45") (pinfunction "8_GND_45") (pintype "power_in"))
      (node (ref "L14") (pin "1") (pinfunction "1_~{OE}_1") (pintype "input"))
      (node (ref "L14") (pin "10") (pinfunction "1_GND_10") (pintype "power_in"))
      (node (ref "L14") (pin "15") (pinfunction "2_GND_15") (pintype "power_in"))
      (node (ref "L14") (pin "21") (pinfunction "3_GND_21") (pintype "power_in"))
      (node (ref "L14") (pin "24") (pinfunction "2_~{OE}_24") (pintype "input"))
      (node (ref "L14") (pin "28") (pinfunction "4_GND_28") (pintype "power_in"))
      (node (ref "L14") (pin "34") (pinfunction "5_GND_34") (pintype "power_in"))
      (node (ref "L14") (pin "39") (pinfunction "6_GND_39") (pintype "power_in"))
      (node (ref "L14") (pin "4") (pinfunction "7_GND_4") (pintype "power_in"))
      (node (ref "L14") (pin "45") (pinfunction "8_GND_45") (pintype "power_in"))
      (node (ref "L15") (pin "1") (pinfunction "1_~{OE}_1") (pintype "input"))
      (node (ref "L15") (pin "10") (pinfunction "1_GND_10") (pintype "power_in"))
      (node (ref "L15") (pin "15") (pinfunction "2_GND_15") (pintype "power_in"))
      (node (ref "L15") (pin "21") (pinfunction "3_GND_21") (pintype "power_in"))
      (node (ref "L15") (pin "24") (pinfunction "2_~{OE}_24") (pintype "input"))
      (node (ref "L15") (pin "28") (pinfunction "4_GND_28") (pintype "power_in"))
      (node (ref "L15") (pin "34") (pinfunction "5_GND_34") (pintype "power_in"))
      (node (ref "L15") (pin "39") (pinfunction "6_GND_39") (pintype "power_in"))
      (node (ref "L15") (pin "4") (pinfunction "7_GND_4") (pintype "power_in"))
      (node (ref "L15") (pin "45") (pinfunction "8_GND_45") (pintype "power_in"))
      (node (ref "L16") (pin "1") (pinfunction "1_~{OE}_1") (pintype "input"))
      (node (ref "L16") (pin "10") (pinfunction "1_GND_10") (pintype "power_in"))
      (node (ref "L16") (pin "15") (pinfunction "2_GND_15") (pintype "power_in"))
      (node (ref "L16") (pin "21") (pinfunction "3_GND_21") (pintype "power_in"))
      (node (ref "L16") (pin "24") (pinfunction "2_~{OE}_24") (pintype "input"))
      (node (ref "L16") (pin "28") (pinfunction "4_GND_28") (pintype "power_in"))
      (node (ref "L16") (pin "34") (pinfunction "5_GND_34") (pintype "power_in"))
      (node (ref "L16") (pin "39") (pinfunction "6_GND_39") (pintype "power_in"))
      (node (ref "L16") (pin "4") (pinfunction "7_GND_4") (pintype "power_in"))
      (node (ref "L16") (pin "45") (pinfunction "8_GND_45") (pintype "power_in"))
      (node (ref "L17") (pin "1") (pinfunction "1_~{OE}_1") (pintype "input"))
      (node (ref "L17") (pin "10") (pinfunction "1_GND_10") (pintype "power_in"))
      (node (ref "L17") (pin "15") (pinfunction "2_GND_15") (pintype "power_in"))
      (node (ref "L17") (pin "21") (pinfunction "3_GND_21") (pintype "power_in"))
      (node (ref "L17") (pin "24") (pinfunction "2_~{OE}_24") (pintype "input"))
      (node (ref "L17") (pin "28") (pinfunction "4_GND_28") (pintype "power_in"))
      (node (ref "L17") (pin "34") (pinfunction "5_GND_34") (pintype "power_in"))
      (node (ref "L17") (pin "39") (pinfunction "6_GND_39") (pintype "power_in"))
      (node (ref "L17") (pin "4") (pinfunction "7_GND_4") (pintype "power_in"))
      (node (ref "L17") (pin "45") (pinfunction "8_GND_45") (pintype "power_in"))
      (node (ref "L18") (pin "1") (pinfunction "1_~{OE}_1") (pintype "input"))
      (node (ref "L18") (pin "10") (pinfunction "1_GND_10") (pintype "power_in"))
      (node (ref "L18") (pin "15") (pinfunction "2_GND_15") (pintype "power_in"))
      (node (ref "L18") (pin "21") (pinfunction "3_GND_21") (pintype "power_in"))
      (node (ref "L18") (pin "24") (pinfunction "2_~{OE}_24") (pintype "input"))
      (node (ref "L18") (pin "28") (pinfunction "4_GND_28") (pintype "power_in"))
      (node (ref "L18") (pin "34") (pinfunction "5_GND_34") (pintype "power_in"))
      (node (ref "L18") (pin "39") (pinfunction "6_GND_39") (pintype "power_in"))
      (node (ref "L18") (pin "4") (pinfunction "7_GND_4") (pintype "power_in"))
      (node (ref "L18") (pin "45") (pinfunction "8_GND_45") (pintype "power_in"))
      (node (ref "L19") (pin "1") (pinfunction "1_~{OE}_1") (pintype "input"))
      (node (ref "L19") (pin "10") (pinfunction "1_GND_10") (pintype "power_in"))
      (node (ref "L19") (pin "15") (pinfunction "2_GND_15") (pintype "power_in"))
      (node (ref "L19") (pin "21") (pinfunction "3_GND_21") (pintype "power_in"))
      (node (ref "L19") (pin "24") (pinfunction "2_~{OE}_24") (pintype "input"))
      (node (ref "L19") (pin "28") (pinfunction "4_GND_28") (pintype "power_in"))
      (node (ref "L19") (pin "34") (pinfunction "5_GND_34") (pintype "power_in"))
      (node (ref "L19") (pin "39") (pinfunction "6_GND_39") (pintype "power_in"))
      (node (ref "L19") (pin "4") (pinfunction "7_GND_4") (pintype "power_in"))
      (node (ref "L19") (pin "45") (pinfunction "8_GND_45") (pintype "power_in"))
      (node (ref "L2") (pin "1") (pinfunction "1_~{OE}_1") (pintype "input"))
      (node (ref "L2") (pin "10") (pinfunction "1_GND_10") (pintype "power_in"))
      (node (ref "L2") (pin "15") (pinfunction "2_GND_15") (pintype "power_in"))
      (node (ref "L2") (pin "21") (pinfunction "3_GND_21") (pintype "power_in"))
      (node (ref "L2") (pin "24") (pinfunction "2_~{OE}_24") (pintype "input"))
      (node (ref "L2") (pin "28") (pinfunction "4_GND_28") (pintype "power_in"))
      (node (ref "L2") (pin "34") (pinfunction "5_GND_34") (pintype "power_in"))
      (node (ref "L2") (pin "39") (pinfunction "6_GND_39") (pintype "power_in"))
      (node (ref "L2") (pin "4") (pinfunction "7_GND_4") (pintype "power_in"))
      (node (ref "L2") (pin "45") (pinfunction "8_GND_45") (pintype "power_in"))
      (node (ref "L20") (pin "1") (pinfunction "1_~{OE}_1") (pintype "input"))
      (node (ref "L20") (pin "10") (pinfunction "1_GND_10") (pintype "power_in"))
      (node (ref "L20") (pin "15") (pinfunction "2_GND_15") (pintype "power_in"))
      (node (ref "L20") (pin "21") (pinfunction "3_GND_21") (pintype "power_in"))
      (node (ref "L20") (pin "24") (pinfunction "2_~{OE}_24") (pintype "input"))
      (node (ref "L20") (pin "28") (pinfunction "4_GND_28") (pintype "power_in"))
      (node (ref "L20") (pin "34") (pinfunction "5_GND_34") (pintype "power_in"))
      (node (ref "L20") (pin "39") (pinfunction "6_GND_39") (pintype "power_in"))
      (node (ref "L20") (pin "4") (pinfunction "7_GND_4") (pintype "power_in"))
      (node (ref "L20") (pin "45") (pinfunction "8_GND_45") (pintype "power_in"))
      (node (ref "L21") (pin "1") (pinfunction "1_~{OE}_1") (pintype "input"))
      (node (ref "L21") (pin "10") (pinfunction "1_GND_10") (pintype "power_in"))
      (node (ref "L21") (pin "15") (pinfunction "2_GND_15") (pintype "power_in"))
      (node (ref "L21") (pin "21") (pinfunction "3_GND_21") (pintype "power_in"))
      (node (ref "L21") (pin "24") (pinfunction "2_~{OE}_24") (pintype "input"))
      (node (ref "L21") (pin "28") (pinfunction "4_GND_28") (pintype "power_in"))
      (node (ref "L21") (pin "34") (pinfunction "5_GND_34") (pintype "power_in"))
      (node (ref "L21") (pin "39") (pinfunction "6_GND_39") (pintype "power_in"))
      (node (ref "L21") (pin "4") (pinfunction "7_GND_4") (pintype "power_in"))
      (node (ref "L21") (pin "45") (pinfunction "8_GND_45") (pintype "power_in"))
      (node (ref "L22") (pin "1") (pinfunction "1_~{OE}_1") (pintype "input"))
      (node (ref "L22") (pin "10") (pinfunction "1_GND_10") (pintype "power_in"))
      (node (ref "L22") (pin "15") (pinfunction "2_GND_15") (pintype "power_in"))
      (node (ref "L22") (pin "21") (pinfunction "3_GND_21") (pintype "power_in"))
      (node (ref "L22") (pin "24") (pinfunction "2_~{OE}_24") (pintype "input"))
      (node (ref "L22") (pin "28") (pinfunction "4_GND_28") (pintype "power_in"))
      (node (ref "L22") (pin "34") (pinfunction "5_GND_34") (pintype "power_in"))
      (node (ref "L22") (pin "39") (pinfunction "6_GND_39") (pintype "power_in"))
      (node (ref "L22") (pin "4") (pinfunction "7_GND_4") (pintype "power_in"))
      (node (ref "L22") (pin "45") (pinfunction "8_GND_45") (pintype "power_in"))
      (node (ref "L23") (pin "1") (pinfunction "1_~{OE}_1") (pintype "input"))
      (node (ref "L23") (pin "10") (pinfunction "1_GND_10") (pintype "power_in"))
      (node (ref "L23") (pin "15") (pinfunction "2_GND_15") (pintype "power_in"))
      (node (ref "L23") (pin "21") (pinfunction "3_GND_21") (pintype "power_in"))
      (node (ref "L23") (pin "24") (pinfunction "2_~{OE}_24") (pintype "input"))
      (node (ref "L23") (pin "28") (pinfunction "4_GND_28") (pintype "power_in"))
      (node (ref "L23") (pin "34") (pinfunction "5_GND_34") (pintype "power_in"))
      (node (ref "L23") (pin "39") (pinfunction "6_GND_39") (pintype "power_in"))
      (node (ref "L23") (pin "4") (pinfunction "7_GND_4") (pintype "power_in"))
      (node (ref "L23") (pin "45") (pinfunction "8_GND_45") (pintype "power_in"))
      (node (ref "L24") (pin "1") (pinfunction "1_~{OE}_1") (pintype "input"))
      (node (ref "L24") (pin "10") (pinfunction "1_GND_10") (pintype "power_in"))
      (node (ref "L24") (pin "15") (pinfunction "2_GND_15") (pintype "power_in"))
      (node (ref "L24") (pin "21") (pinfunction "3_GND_21") (pintype "power_in"))
      (node (ref "L24") (pin "24") (pinfunction "2_~{OE}_24") (pintype "input"))
      (node (ref "L24") (pin "28") (pinfunction "4_GND_28") (pintype "power_in"))
      (node (ref "L24") (pin "34") (pinfunction "5_GND_34") (pintype "power_in"))
      (node (ref "L24") (pin "39") (pinfunction "6_GND_39") (pintype "power_in"))
      (node (ref "L24") (pin "4") (pinfunction "7_GND_4") (pintype "power_in"))
      (node (ref "L24") (pin "45") (pinfunction "8_GND_45") (pintype "power_in"))
      (node (ref "L25") (pin "1") (pinfunction "1_~{OE}_1") (pintype "input"))
      (node (ref "L25") (pin "10") (pinfunction "1_GND_10") (pintype "power_in"))
      (node (ref "L25") (pin "15") (pinfunction "2_GND_15") (pintype "power_in"))
      (node (ref "L25") (pin "21") (pinfunction "3_GND_21") (pintype "power_in"))
      (node (ref "L25") (pin "24") (pinfunction "2_~{OE}_24") (pintype "input"))
      (node (ref "L25") (pin "28") (pinfunction "4_GND_28") (pintype "power_in"))
      (node (ref "L25") (pin "34") (pinfunction "5_GND_34") (pintype "power_in"))
      (node (ref "L25") (pin "39") (pinfunction "6_GND_39") (pintype "power_in"))
      (node (ref "L25") (pin "4") (pinfunction "7_GND_4") (pintype "power_in"))
      (node (ref "L25") (pin "45") (pinfunction "8_GND_45") (pintype "power_in"))
      (node (ref "L3") (pin "1") (pinfunction "1_~{OE}_1") (pintype "input"))
      (node (ref "L3") (pin "10") (pinfunction "1_GND_10") (pintype "power_in"))
      (node (ref "L3") (pin "15") (pinfunction "2_GND_15") (pintype "power_in"))
      (node (ref "L3") (pin "21") (pinfunction "3_GND_21") (pintype "power_in"))
      (node (ref "L3") (pin "24") (pinfunction "2_~{OE}_24") (pintype "input"))
      (node (ref "L3") (pin "28") (pinfunction "4_GND_28") (pintype "power_in"))
      (node (ref "L3") (pin "34") (pinfunction "5_GND_34") (pintype "power_in"))
      (node (ref "L3") (pin "39") (pinfunction "6_GND_39") (pintype "power_in"))
      (node (ref "L3") (pin "4") (pinfunction "7_GND_4") (pintype "power_in"))
      (node (ref "L3") (pin "45") (pinfunction "8_GND_45") (pintype "power_in"))
      (node (ref "L4") (pin "1") (pinfunction "1_~{OE}_1") (pintype "input"))
      (node (ref "L4") (pin "10") (pinfunction "1_GND_10") (pintype "power_in"))
      (node (ref "L4") (pin "15") (pinfunction "2_GND_15") (pintype "power_in"))
      (node (ref "L4") (pin "21") (pinfunction "3_GND_21") (pintype "power_in"))
      (node (ref "L4") (pin "24") (pinfunction "2_~{OE}_24") (pintype "input"))
      (node (ref "L4") (pin "28") (pinfunction "4_GND_28") (pintype "power_in"))
      (node (ref "L4") (pin "34") (pinfunction "5_GND_34") (pintype "power_in"))
      (node (ref "L4") (pin "39") (pinfunction "6_GND_39") (pintype "power_in"))
      (node (ref "L4") (pin "4") (pinfunction "7_GND_4") (pintype "power_in"))
      (node (ref "L4") (pin "45") (pinfunction "8_GND_45") (pintype "power_in"))
      (node (ref "L5") (pin "1") (pinfunction "1_~{OE}_1") (pintype "input"))
      (node (ref "L5") (pin "10") (pinfunction "1_GND_10") (pintype "power_in"))
      (node (ref "L5") (pin "15") (pinfunction "2_GND_15") (pintype "power_in"))
      (node (ref "L5") (pin "21") (pinfunction "3_GND_21") (pintype "power_in"))
      (node (ref "L5") (pin "24") (pinfunction "2_~{OE}_24") (pintype "input"))
      (node (ref "L5") (pin "28") (pinfunction "4_GND_28") (pintype "power_in"))
      (node (ref "L5") (pin "34") (pinfunction "5_GND_34") (pintype "power_in"))
      (node (ref "L5") (pin "39") (pinfunction "6_GND_39") (pintype "power_in"))
      (node (ref "L5") (pin "4") (pinfunction "7_GND_4") (pintype "power_in"))
      (node (ref "L5") (pin "45") (pinfunction "8_GND_45") (pintype "power_in"))
      (node (ref "L6") (pin "1") (pinfunction "1_~{OE}_1") (pintype "input"))
      (node (ref "L6") (pin "10") (pinfunction "1_GND_10") (pintype "power_in"))
      (node (ref "L6") (pin "15") (pinfunction "2_GND_15") (pintype "power_in"))
      (node (ref "L6") (pin "21") (pinfunction "3_GND_21") (pintype "power_in"))
      (node (ref "L6") (pin "24") (pinfunction "2_~{OE}_24") (pintype "input"))
      (node (ref "L6") (pin "28") (pinfunction "4_GND_28") (pintype "power_in"))
      (node (ref "L6") (pin "34") (pinfunction "5_GND_34") (pintype "power_in"))
      (node (ref "L6") (pin "39") (pinfunction "6_GND_39") (pintype "power_in"))
      (node (ref "L6") (pin "4") (pinfunction "7_GND_4") (pintype "power_in"))
      (node (ref "L6") (pin "45") (pinfunction "8_GND_45") (pintype "power_in"))
      (node (ref "L7") (pin "1") (pinfunction "1_~{OE}_1") (pintype "input"))
      (node (ref "L7") (pin "10") (pinfunction "1_GND_10") (pintype "power_in"))
      (node (ref "L7") (pin "15") (pinfunction "2_GND_15") (pintype "power_in"))
      (node (ref "L7") (pin "21") (pinfunction "3_GND_21") (pintype "power_in"))
      (node (ref "L7") (pin "24") (pinfunction "2_~{OE}_24") (pintype "input"))
      (node (ref "L7") (pin "28") (pinfunction "4_GND_28") (pintype "power_in"))
      (node (ref "L7") (pin "34") (pinfunction "5_GND_34") (pintype "power_in"))
      (node (ref "L7") (pin "39") (pinfunction "6_GND_39") (pintype "power_in"))
      (node (ref "L7") (pin "4") (pinfunction "7_GND_4") (pintype "power_in"))
      (node (ref "L7") (pin "45") (pinfunction "8_GND_45") (pintype "power_in"))
      (node (ref "L8") (pin "1") (pinfunction "1_~{OE}_1") (pintype "input"))
      (node (ref "L8") (pin "10") (pinfunction "1_GND_10") (pintype "power_in"))
      (node (ref "L8") (pin "15") (pinfunction "2_GND_15") (pintype "power_in"))
      (node (ref "L8") (pin "21") (pinfunction "3_GND_21") (pintype "power_in"))
      (node (ref "L8") (pin "24") (pinfunction "2_~{OE}_24") (pintype "input"))
      (node (ref "L8") (pin "28") (pinfunction "4_GND_28") (pintype "power_in"))
      (node (ref "L8") (pin "34") (pinfunction "5_GND_34") (pintype "power_in"))
      (node (ref "L8") (pin "39") (pinfunction "6_GND_39") (pintype "power_in"))
      (node (ref "L8") (pin "4") (pinfunction "7_GND_4") (pintype "power_in"))
      (node (ref "L8") (pin "45") (pinfunction "8_GND_45") (pintype "power_in"))
      (node (ref "L9") (pin "1") (pinfunction "1_~{OE}_1") (pintype "input"))
      (node (ref "L9") (pin "10") (pinfunction "1_GND_10") (pintype "power_in"))
      (node (ref "L9") (pin "15") (pinfunction "2_GND_15") (pintype "power_in"))
      (node (ref "L9") (pin "21") (pinfunction "3_GND_21") (pintype "power_in"))
      (node (ref "L9") (pin "24") (pinfunction "2_~{OE}_24") (pintype "input"))
      (node (ref "L9") (pin "28") (pinfunction "4_GND_28") (pintype "power_in"))
      (node (ref "L9") (pin "34") (pinfunction "5_GND_34") (pintype "power_in"))
      (node (ref "L9") (pin "39") (pinfunction "6_GND_39") (pintype "power_in"))
      (node (ref "L9") (pin "4") (pinfunction "7_GND_4") (pintype "power_in"))
      (node (ref "L9") (pin "45") (pinfunction "8_GND_45") (pintype "power_in"))
      (node (ref "POWER_JP1") (pin "3") (pinfunction "3_3") (pintype "passive"))
      (node (ref "POWER_JP2") (pin "3") (pinfunction "3_3") (pintype "passive"))
      (node (ref "POWER_JP3") (pin "3") (pinfunction "3_3") (pintype "passive"))
      (node (ref "POWER_JP4") (pin "3") (pinfunction "3_3") (pintype "passive"))
      (node (ref "SR1") (pin "13") (pinfunction "~{OE}_13") (pintype "input"))
      (node (ref "SR1") (pin "8") (pinfunction "GND_8") (pintype "power_in"))
      (node (ref "SR10") (pin "13") (pinfunction "~{OE}_13") (pintype "input"))
      (node (ref "SR10") (pin "8") (pinfunction "GND_8") (pintype "power_in"))
      (node (ref "SR11") (pin "13") (pinfunction "~{OE}_13") (pintype "input"))
      (node (ref "SR11") (pin "8") (pinfunction "GND_8") (pintype "power_in"))
      (node (ref "SR12") (pin "13") (pinfunction "~{OE}_13") (pintype "input"))
      (node (ref "SR12") (pin "8") (pinfunction "GND_8") (pintype "power_in"))
      (node (ref "SR13") (pin "13") (pinfunction "~{OE}_13") (pintype "input"))
      (node (ref "SR13") (pin "8") (pinfunction "GND_8") (pintype "power_in"))
      (node (ref "SR14") (pin "13") (pinfunction "~{OE}_13") (pintype "input"))
      (node (ref "SR14") (pin "8") (pinfunction "GND_8") (pintype "power_in"))
      (node (ref "SR15") (pin "13") (pinfunction "~{OE}_13") (pintype "input"))
      (node (ref "SR15") (pin "8") (pinfunction "GND_8") (pintype "power_in"))
      (node (ref "SR16") (pin "13") (pinfunction "~{OE}_13") (pintype "input"))
      (node (ref "SR16") (pin "8") (pinfunction "GND_8") (pintype "power_in"))
      (node (ref "SR17") (pin "13") (pinfunction "~{OE}_13") (pintype "input"))
      (node (ref "SR17") (pin "8") (pinfunction "GND_8") (pintype "power_in"))
      (node (ref "SR18") (pin "13") (pinfunction "~{OE}_13") (pintype "input"))
      (node (ref "SR18") (pin "8") (pinfunction "GND_8") (pintype "power_in"))
      (node (ref "SR19") (pin "13") (pinfunction "~{OE}_13") (pintype "input"))
      (node (ref "SR19") (pin "8") (pinfunction "GND_8") (pintype "power_in"))
      (node (ref "SR2") (pin "13") (pinfunction "~{OE}_13") (pintype "input"))
      (node (ref "SR2") (pin "8") (pinfunction "GND_8") (pintype "power_in"))
      (node (ref "SR20") (pin "13") (pinfunction "~{OE}_13") (pintype "input"))
      (node (ref "SR20") (pin "8") (pinfunction "GND_8") (pintype "power_in"))
      (node (ref "SR21") (pin "13") (pinfunction "~{OE}_13") (pintype "input"))
      (node (ref "SR21") (pin "8") (pinfunction "GND_8") (pintype "power_in"))
      (node (ref "SR22") (pin "13") (pinfunction "~{OE}_13") (pintype "input"))
      (node (ref "SR22") (pin "8") (pinfunction "GND_8") (pintype "power_in"))
      (node (ref "SR23") (pin "13") (pinfunction "~{OE}_13") (pintype "input"))
      (node (ref "SR23") (pin "8") (pinfunction "GND_8") (pintype "power_in"))
      (node (ref "SR24") (pin "13") (pinfunction "~{OE}_13") (pintype "input"))
      (node (ref "SR24") (pin "8") (pinfunction "GND_8") (pintype "power_in"))
      (node (ref "SR25") (pin "13") (pinfunction "~{OE}_13") (pintype "input"))
      (node (ref "SR25") (pin "8") (pinfunction "GND_8") (pintype "power_in"))
      (node (ref "SR3") (pin "13") (pinfunction "~{OE}_13") (pintype "input"))
      (node (ref "SR3") (pin "8") (pinfunction "GND_8") (pintype "power_in"))
      (node (ref "SR4") (pin "13") (pinfunction "~{OE}_13") (pintype "input"))
      (node (ref "SR4") (pin "8") (pinfunction "GND_8") (pintype "power_in"))
      (node (ref "SR5") (pin "13") (pinfunction "~{OE}_13") (pintype "input"))
      (node (ref "SR5") (pin "8") (pinfunction "GND_8") (pintype "power_in"))
      (node (ref "SR6") (pin "13") (pinfunction "~{OE}_13") (pintype "input"))
      (node (ref "SR6") (pin "8") (pinfunction "GND_8") (pintype "power_in"))
      (node (ref "SR7") (pin "13") (pinfunction "~{OE}_13") (pintype "input"))
      (node (ref "SR7") (pin "8") (pinfunction "GND_8") (pintype "power_in"))
      (node (ref "SR8") (pin "13") (pinfunction "~{OE}_13") (pintype "input"))
      (node (ref "SR8") (pin "8") (pinfunction "GND_8") (pintype "power_in"))
      (node (ref "SR9") (pin "13") (pinfunction "~{OE}_13") (pintype "input"))
      (node (ref "SR9") (pin "8") (pinfunction "GND_8") (pintype "power_in"))
    )
    (net (code "423") (name "/LATCH_CLK1") (class "Default")
      (node (ref "IN_JP1") (pin "1") (pinfunction "1_1") (pintype "passive"))
      (node (ref "LATCH1-2") (pin "2") (pinfunction "2_2") (pintype "passive"))
      (node (ref "OUT_JP1") (pin "1") (pinfunction "1_1") (pintype "passive"))
      (node (ref "SR1") (pin "12") (pinfunction "RCLK_12") (pintype "input"))
      (node (ref "SR2") (pin "12") (pinfunction "RCLK_12") (pintype "input"))
      (node (ref "SR3") (pin "12") (pinfunction "RCLK_12") (pintype "input"))
      (node (ref "SR4") (pin "12") (pinfunction "RCLK_12") (pintype "input"))
      (node (ref "SR5") (pin "12") (pinfunction "RCLK_12") (pintype "input"))
    )
    (net (code "424") (name "/LATCH_CLK2") (class "Default")
      (node (ref "IN_JP2") (pin "1") (pinfunction "1_1") (pintype "passive"))
      (node (ref "LATCH1-2") (pin "1") (pinfunction "1_1") (pintype "passive"))
      (node (ref "LATCH2-3") (pin "2") (pinfunction "2_2") (pintype "passive"))
      (node (ref "OUT_JP2") (pin "1") (pinfunction "1_1") (pintype "passive"))
      (node (ref "SR10") (pin "12") (pinfunction "RCLK_12") (pintype "input"))
      (node (ref "SR6") (pin "12") (pinfunction "RCLK_12") (pintype "input"))
      (node (ref "SR7") (pin "12") (pinfunction "RCLK_12") (pintype "input"))
      (node (ref "SR8") (pin "12") (pinfunction "RCLK_12") (pintype "input"))
      (node (ref "SR9") (pin "12") (pinfunction "RCLK_12") (pintype "input"))
    )
    (net (code "425") (name "/LATCH_CLK3") (class "Default")
      (node (ref "IN_JP3") (pin "1") (pinfunction "1_1") (pintype "passive"))
      (node (ref "LATCH2-3") (pin "1") (pinfunction "1_1") (pintype "passive"))
      (node (ref "LATCH3-4") (pin "2") (pinfunction "2_2") (pintype "passive"))
      (node (ref "OUT_JP3") (pin "1") (pinfunction "1_1") (pintype "passive"))
      (node (ref "SR11") (pin "12") (pinfunction "RCLK_12") (pintype "input"))
      (node (ref "SR12") (pin "12") (pinfunction "RCLK_12") (pintype "input"))
      (node (ref "SR13") (pin "12") (pinfunction "RCLK_12") (pintype "input"))
      (node (ref "SR14") (pin "12") (pinfunction "RCLK_12") (pintype "input"))
      (node (ref "SR15") (pin "12") (pinfunction "RCLK_12") (pintype "input"))
    )
    (net (code "426") (name "/LATCH_CLK4") (class "Default")
      (node (ref "IN_JP4") (pin "1") (pinfunction "1_1") (pintype "passive"))
      (node (ref "LATCH3-4") (pin "1") (pinfunction "1_1") (pintype "passive"))
      (node (ref "LATCH4-5") (pin "2") (pinfunction "2_2") (pintype "passive"))
      (node (ref "OUT_JP4") (pin "1") (pinfunction "1_1") (pintype "passive"))
      (node (ref "SR16") (pin "12") (pinfunction "RCLK_12") (pintype "input"))
      (node (ref "SR17") (pin "12") (pinfunction "RCLK_12") (pintype "input"))
      (node (ref "SR18") (pin "12") (pinfunction "RCLK_12") (pintype "input"))
      (node (ref "SR19") (pin "12") (pinfunction "RCLK_12") (pintype "input"))
      (node (ref "SR20") (pin "12") (pinfunction "RCLK_12") (pintype "input"))
    )
    (net (code "427") (name "/LATCH_CLK5") (class "Default")
      (node (ref "IN_JP5") (pin "1") (pinfunction "1_1") (pintype "passive"))
      (node (ref "LATCH4-5") (pin "1") (pinfunction "1_1") (pintype "passive"))
      (node (ref "OUT_JP5") (pin "1") (pinfunction "1_1") (pintype "passive"))
      (node (ref "SR21") (pin "12") (pinfunction "RCLK_12") (pintype "input"))
      (node (ref "SR22") (pin "12") (pinfunction "RCLK_12") (pintype "input"))
      (node (ref "SR23") (pin "12") (pinfunction "RCLK_12") (pintype "input"))
      (node (ref "SR24") (pin "12") (pinfunction "RCLK_12") (pintype "input"))
      (node (ref "SR25") (pin "12") (pinfunction "RCLK_12") (pintype "input"))
    )
    (net (code "428") (name "/SR_OUT1_1") (class "Default")
      (node (ref "L1") (pin "36") (pinfunction "2D1_36") (pintype "input"))
      (node (ref "L1") (pin "47") (pinfunction "1D1_47") (pintype "input"))
      (node (ref "SR1") (pin "15") (pinfunction "QA_15") (pintype "tri_state"))
    )
    (net (code "429") (name "/SR_OUT1_2") (class "Default")
      (node (ref "L1") (pin "35") (pinfunction "2D2_35") (pintype "input"))
      (node (ref "L1") (pin "46") (pinfunction "1D2_46") (pintype "input"))
      (node (ref "SR1") (pin "1") (pinfunction "QB_1") (pintype "tri_state"))
    )
    (net (code "430") (name "/SR_OUT1_3") (class "Default")
      (node (ref "L1") (pin "33") (pinfunction "2D3_33") (pintype "input"))
      (node (ref "L1") (pin "44") (pinfunction "1D3_44") (pintype "input"))
      (node (ref "SR1") (pin "2") (pinfunction "QC_2") (pintype "tri_state"))
    )
    (net (code "431") (name "/SR_OUT1_4") (class "Default")
      (node (ref "L1") (pin "32") (pinfunction "2D4_32") (pintype "input"))
      (node (ref "L1") (pin "43") (pinfunction "1D4_43") (pintype "input"))
      (node (ref "SR1") (pin "3") (pinfunction "QD_3") (pintype "tri_state"))
    )
    (net (code "432") (name "/SR_OUT1_5") (class "Default")
      (node (ref "L1") (pin "30") (pinfunction "2D5_30") (pintype "input"))
      (node (ref "L1") (pin "41") (pinfunction "1D5_41") (pintype "input"))
      (node (ref "SR1") (pin "4") (pinfunction "QE_4") (pintype "tri_state"))
    )
    (net (code "433") (name "/SR_OUT1_6") (class "Default")
      (node (ref "L1") (pin "29") (pinfunction "2D6_29") (pintype "input"))
      (node (ref "L1") (pin "40") (pinfunction "1D6_40") (pintype "input"))
      (node (ref "SR1") (pin "5") (pinfunction "QF_5") (pintype "tri_state"))
    )
    (net (code "434") (name "/SR_OUT1_7") (class "Default")
      (node (ref "L1") (pin "27") (pinfunction "2D7_27") (pintype "input"))
      (node (ref "L1") (pin "38") (pinfunction "1D7_38") (pintype "input"))
      (node (ref "SR1") (pin "6") (pinfunction "QG_6") (pintype "tri_state"))
    )
    (net (code "435") (name "/SR_OUT1_8") (class "Default")
      (node (ref "L1") (pin "26") (pinfunction "2D8_26") (pintype "input"))
      (node (ref "L1") (pin "37") (pinfunction "1D8_37") (pintype "input"))
      (node (ref "SR1") (pin "7") (pinfunction "QH_7") (pintype "tri_state"))
    )
    (net (code "436") (name "/SR_OUT2_1") (class "Default")
      (node (ref "L2") (pin "36") (pinfunction "2D1_36") (pintype "input"))
      (node (ref "L2") (pin "47") (pinfunction "1D1_47") (pintype "input"))
      (node (ref "SR2") (pin "15") (pinfunction "QA_15") (pintype "tri_state"))
    )
    (net (code "437") (name "/SR_OUT2_2") (class "Default")
      (node (ref "L2") (pin "35") (pinfunction "2D2_35") (pintype "input"))
      (node (ref "L2") (pin "46") (pinfunction "1D2_46") (pintype "input"))
      (node (ref "SR2") (pin "1") (pinfunction "QB_1") (pintype "tri_state"))
    )
    (net (code "438") (name "/SR_OUT2_3") (class "Default")
      (node (ref "L2") (pin "33") (pinfunction "2D3_33") (pintype "input"))
      (node (ref "L2") (pin "44") (pinfunction "1D3_44") (pintype "input"))
      (node (ref "SR2") (pin "2") (pinfunction "QC_2") (pintype "tri_state"))
    )
    (net (code "439") (name "/SR_OUT2_4") (class "Default")
      (node (ref "L2") (pin "32") (pinfunction "2D4_32") (pintype "input"))
      (node (ref "L2") (pin "43") (pinfunction "1D4_43") (pintype "input"))
      (node (ref "SR2") (pin "3") (pinfunction "QD_3") (pintype "tri_state"))
    )
    (net (code "440") (name "/SR_OUT2_5") (class "Default")
      (node (ref "L2") (pin "30") (pinfunction "2D5_30") (pintype "input"))
      (node (ref "L2") (pin "41") (pinfunction "1D5_41") (pintype "input"))
      (node (ref "SR2") (pin "4") (pinfunction "QE_4") (pintype "tri_state"))
    )
    (net (code "441") (name "/SR_OUT2_6") (class "Default")
      (node (ref "L2") (pin "29") (pinfunction "2D6_29") (pintype "input"))
      (node (ref "L2") (pin "40") (pinfunction "1D6_40") (pintype "input"))
      (node (ref "SR2") (pin "5") (pinfunction "QF_5") (pintype "tri_state"))
    )
    (net (code "442") (name "/SR_OUT2_7") (class "Default")
      (node (ref "L2") (pin "27") (pinfunction "2D7_27") (pintype "input"))
      (node (ref "L2") (pin "38") (pinfunction "1D7_38") (pintype "input"))
      (node (ref "SR2") (pin "6") (pinfunction "QG_6") (pintype "tri_state"))
    )
    (net (code "443") (name "/SR_OUT2_8") (class "Default")
      (node (ref "L2") (pin "26") (pinfunction "2D8_26") (pintype "input"))
      (node (ref "L2") (pin "37") (pinfunction "1D8_37") (pintype "input"))
      (node (ref "SR2") (pin "7") (pinfunction "QH_7") (pintype "tri_state"))
    )
    (net (code "444") (name "/SR_OUT3_1") (class "Default")
      (node (ref "L3") (pin "36") (pinfunction "2D1_36") (pintype "input"))
      (node (ref "L3") (pin "47") (pinfunction "1D1_47") (pintype "input"))
      (node (ref "SR3") (pin "15") (pinfunction "QA_15") (pintype "tri_state"))
    )
    (net (code "445") (name "/SR_OUT3_2") (class "Default")
      (node (ref "L3") (pin "35") (pinfunction "2D2_35") (pintype "input"))
      (node (ref "L3") (pin "46") (pinfunction "1D2_46") (pintype "input"))
      (node (ref "SR3") (pin "1") (pinfunction "QB_1") (pintype "tri_state"))
    )
    (net (code "446") (name "/SR_OUT3_3") (class "Default")
      (node (ref "L3") (pin "33") (pinfunction "2D3_33") (pintype "input"))
      (node (ref "L3") (pin "44") (pinfunction "1D3_44") (pintype "input"))
      (node (ref "SR3") (pin "2") (pinfunction "QC_2") (pintype "tri_state"))
    )
    (net (code "447") (name "/SR_OUT3_4") (class "Default")
      (node (ref "L3") (pin "32") (pinfunction "2D4_32") (pintype "input"))
      (node (ref "L3") (pin "43") (pinfunction "1D4_43") (pintype "input"))
      (node (ref "SR3") (pin "3") (pinfunction "QD_3") (pintype "tri_state"))
    )
    (net (code "448") (name "/SR_OUT3_5") (class "Default")
      (node (ref "L3") (pin "30") (pinfunction "2D5_30") (pintype "input"))
      (node (ref "L3") (pin "41") (pinfunction "1D5_41") (pintype "input"))
      (node (ref "SR3") (pin "4") (pinfunction "QE_4") (pintype "tri_state"))
    )
    (net (code "449") (name "/SR_OUT3_6") (class "Default")
      (node (ref "L3") (pin "29") (pinfunction "2D6_29") (pintype "input"))
      (node (ref "L3") (pin "40") (pinfunction "1D6_40") (pintype "input"))
      (node (ref "SR3") (pin "5") (pinfunction "QF_5") (pintype "tri_state"))
    )
    (net (code "450") (name "/SR_OUT3_7") (class "Default")
      (node (ref "L3") (pin "27") (pinfunction "2D7_27") (pintype "input"))
      (node (ref "L3") (pin "38") (pinfunction "1D7_38") (pintype "input"))
      (node (ref "SR3") (pin "6") (pinfunction "QG_6") (pintype "tri_state"))
    )
    (net (code "451") (name "/SR_OUT3_8") (class "Default")
      (node (ref "L3") (pin "26") (pinfunction "2D8_26") (pintype "input"))
      (node (ref "L3") (pin "37") (pinfunction "1D8_37") (pintype "input"))
      (node (ref "SR3") (pin "7") (pinfunction "QH_7") (pintype "tri_state"))
    )
    (net (code "452") (name "/SR_OUT4_1") (class "Default")
      (node (ref "L4") (pin "36") (pinfunction "2D1_36") (pintype "input"))
      (node (ref "L4") (pin "47") (pinfunction "1D1_47") (pintype "input"))
      (node (ref "SR4") (pin "15") (pinfunction "QA_15") (pintype "tri_state"))
    )
    (net (code "453") (name "/SR_OUT4_2") (class "Default")
      (node (ref "L4") (pin "35") (pinfunction "2D2_35") (pintype "input"))
      (node (ref "L4") (pin "46") (pinfunction "1D2_46") (pintype "input"))
      (node (ref "SR4") (pin "1") (pinfunction "QB_1") (pintype "tri_state"))
    )
    (net (code "454") (name "/SR_OUT4_3") (class "Default")
      (node (ref "L4") (pin "33") (pinfunction "2D3_33") (pintype "input"))
      (node (ref "L4") (pin "44") (pinfunction "1D3_44") (pintype "input"))
      (node (ref "SR4") (pin "2") (pinfunction "QC_2") (pintype "tri_state"))
    )
    (net (code "455") (name "/SR_OUT4_4") (class "Default")
      (node (ref "L4") (pin "32") (pinfunction "2D4_32") (pintype "input"))
      (node (ref "L4") (pin "43") (pinfunction "1D4_43") (pintype "input"))
      (node (ref "SR4") (pin "3") (pinfunction "QD_3") (pintype "tri_state"))
    )
    (net (code "456") (name "/SR_OUT4_5") (class "Default")
      (node (ref "L4") (pin "30") (pinfunction "2D5_30") (pintype "input"))
      (node (ref "L4") (pin "41") (pinfunction "1D5_41") (pintype "input"))
      (node (ref "SR4") (pin "4") (pinfunction "QE_4") (pintype "tri_state"))
    )
    (net (code "457") (name "/SR_OUT4_6") (class "Default")
      (node (ref "L4") (pin "29") (pinfunction "2D6_29") (pintype "input"))
      (node (ref "L4") (pin "40") (pinfunction "1D6_40") (pintype "input"))
      (node (ref "SR4") (pin "5") (pinfunction "QF_5") (pintype "tri_state"))
    )
    (net (code "458") (name "/SR_OUT4_7") (class "Default")
      (node (ref "L4") (pin "27") (pinfunction "2D7_27") (pintype "input"))
      (node (ref "L4") (pin "38") (pinfunction "1D7_38") (pintype "input"))
      (node (ref "SR4") (pin "6") (pinfunction "QG_6") (pintype "tri_state"))
    )
    (net (code "459") (name "/SR_OUT4_8") (class "Default")
      (node (ref "L4") (pin "26") (pinfunction "2D8_26") (pintype "input"))
      (node (ref "L4") (pin "37") (pinfunction "1D8_37") (pintype "input"))
      (node (ref "SR4") (pin "7") (pinfunction "QH_7") (pintype "tri_state"))
    )
    (net (code "460") (name "/SR_OUT5_1") (class "Default")
      (node (ref "L5") (pin "36") (pinfunction "2D1_36") (pintype "input"))
      (node (ref "L5") (pin "47") (pinfunction "1D1_47") (pintype "input"))
      (node (ref "SR5") (pin "15") (pinfunction "QA_15") (pintype "tri_state"))
    )
    (net (code "461") (name "/SR_OUT5_2") (class "Default")
      (node (ref "L5") (pin "35") (pinfunction "2D2_35") (pintype "input"))
      (node (ref "L5") (pin "46") (pinfunction "1D2_46") (pintype "input"))
      (node (ref "SR5") (pin "1") (pinfunction "QB_1") (pintype "tri_state"))
    )
    (net (code "462") (name "/SR_OUT5_3") (class "Default")
      (node (ref "L5") (pin "33") (pinfunction "2D3_33") (pintype "input"))
      (node (ref "L5") (pin "44") (pinfunction "1D3_44") (pintype "input"))
      (node (ref "SR5") (pin "2") (pinfunction "QC_2") (pintype "tri_state"))
    )
    (net (code "463") (name "/SR_OUT5_4") (class "Default")
      (node (ref "L5") (pin "32") (pinfunction "2D4_32") (pintype "input"))
      (node (ref "L5") (pin "43") (pinfunction "1D4_43") (pintype "input"))
      (node (ref "SR5") (pin "3") (pinfunction "QD_3") (pintype "tri_state"))
    )
    (net (code "464") (name "/SR_OUT5_5") (class "Default")
      (node (ref "L5") (pin "30") (pinfunction "2D5_30") (pintype "input"))
      (node (ref "L5") (pin "41") (pinfunction "1D5_41") (pintype "input"))
      (node (ref "SR5") (pin "4") (pinfunction "QE_4") (pintype "tri_state"))
    )
    (net (code "465") (name "/SR_OUT5_6") (class "Default")
      (node (ref "L5") (pin "29") (pinfunction "2D6_29") (pintype "input"))
      (node (ref "L5") (pin "40") (pinfunction "1D6_40") (pintype "input"))
      (node (ref "SR5") (pin "5") (pinfunction "QF_5") (pintype "tri_state"))
    )
    (net (code "466") (name "/SR_OUT5_7") (class "Default")
      (node (ref "L5") (pin "27") (pinfunction "2D7_27") (pintype "input"))
      (node (ref "L5") (pin "38") (pinfunction "1D7_38") (pintype "input"))
      (node (ref "SR5") (pin "6") (pinfunction "QG_6") (pintype "tri_state"))
    )
    (net (code "467") (name "/SR_OUT5_8") (class "Default")
      (node (ref "L5") (pin "26") (pinfunction "2D8_26") (pintype "input"))
      (node (ref "L5") (pin "37") (pinfunction "1D8_37") (pintype "input"))
      (node (ref "SR5") (pin "7") (pinfunction "QH_7") (pintype "tri_state"))
    )
    (net (code "468") (name "/SR_OUT6_1") (class "Default")
      (node (ref "L6") (pin "36") (pinfunction "2D1_36") (pintype "input"))
      (node (ref "L6") (pin "47") (pinfunction "1D1_47") (pintype "input"))
      (node (ref "SR6") (pin "15") (pinfunction "QA_15") (pintype "tri_state"))
    )
    (net (code "469") (name "/SR_OUT6_2") (class "Default")
      (node (ref "L6") (pin "35") (pinfunction "2D2_35") (pintype "input"))
      (node (ref "L6") (pin "46") (pinfunction "1D2_46") (pintype "input"))
      (node (ref "SR6") (pin "1") (pinfunction "QB_1") (pintype "tri_state"))
    )
    (net (code "470") (name "/SR_OUT6_3") (class "Default")
      (node (ref "L6") (pin "33") (pinfunction "2D3_33") (pintype "input"))
      (node (ref "L6") (pin "44") (pinfunction "1D3_44") (pintype "input"))
      (node (ref "SR6") (pin "2") (pinfunction "QC_2") (pintype "tri_state"))
    )
    (net (code "471") (name "/SR_OUT6_4") (class "Default")
      (node (ref "L6") (pin "32") (pinfunction "2D4_32") (pintype "input"))
      (node (ref "L6") (pin "43") (pinfunction "1D4_43") (pintype "input"))
      (node (ref "SR6") (pin "3") (pinfunction "QD_3") (pintype "tri_state"))
    )
    (net (code "472") (name "/SR_OUT6_5") (class "Default")
      (node (ref "L6") (pin "30") (pinfunction "2D5_30") (pintype "input"))
      (node (ref "L6") (pin "41") (pinfunction "1D5_41") (pintype "input"))
      (node (ref "SR6") (pin "4") (pinfunction "QE_4") (pintype "tri_state"))
    )
    (net (code "473") (name "/SR_OUT6_6") (class "Default")
      (node (ref "L6") (pin "29") (pinfunction "2D6_29") (pintype "input"))
      (node (ref "L6") (pin "40") (pinfunction "1D6_40") (pintype "input"))
      (node (ref "SR6") (pin "5") (pinfunction "QF_5") (pintype "tri_state"))
    )
    (net (code "474") (name "/SR_OUT6_7") (class "Default")
      (node (ref "L6") (pin "27") (pinfunction "2D7_27") (pintype "input"))
      (node (ref "L6") (pin "38") (pinfunction "1D7_38") (pintype "input"))
      (node (ref "SR6") (pin "6") (pinfunction "QG_6") (pintype "tri_state"))
    )
    (net (code "475") (name "/SR_OUT6_8") (class "Default")
      (node (ref "L6") (pin "26") (pinfunction "2D8_26") (pintype "input"))
      (node (ref "L6") (pin "37") (pinfunction "1D8_37") (pintype "input"))
      (node (ref "SR6") (pin "7") (pinfunction "QH_7") (pintype "tri_state"))
    )
    (net (code "476") (name "/SR_OUT7_1") (class "Default")
      (node (ref "L7") (pin "36") (pinfunction "2D1_36") (pintype "input"))
      (node (ref "L7") (pin "47") (pinfunction "1D1_47") (pintype "input"))
      (node (ref "SR7") (pin "15") (pinfunction "QA_15") (pintype "tri_state"))
    )
    (net (code "477") (name "/SR_OUT7_2") (class "Default")
      (node (ref "L7") (pin "35") (pinfunction "2D2_35") (pintype "input"))
      (node (ref "L7") (pin "46") (pinfunction "1D2_46") (pintype "input"))
      (node (ref "SR7") (pin "1") (pinfunction "QB_1") (pintype "tri_state"))
    )
    (net (code "478") (name "/SR_OUT7_3") (class "Default")
      (node (ref "L7") (pin "33") (pinfunction "2D3_33") (pintype "input"))
      (node (ref "L7") (pin "44") (pinfunction "1D3_44") (pintype "input"))
      (node (ref "SR7") (pin "2") (pinfunction "QC_2") (pintype "tri_state"))
    )
    (net (code "479") (name "/SR_OUT7_4") (class "Default")
      (node (ref "L7") (pin "32") (pinfunction "2D4_32") (pintype "input"))
      (node (ref "L7") (pin "43") (pinfunction "1D4_43") (pintype "input"))
      (node (ref "SR7") (pin "3") (pinfunction "QD_3") (pintype "tri_state"))
    )
    (net (code "480") (name "/SR_OUT7_5") (class "Default")
      (node (ref "L7") (pin "30") (pinfunction "2D5_30") (pintype "input"))
      (node (ref "L7") (pin "41") (pinfunction "1D5_41") (pintype "input"))
      (node (ref "SR7") (pin "4") (pinfunction "QE_4") (pintype "tri_state"))
    )
    (net (code "481") (name "/SR_OUT7_6") (class "Default")
      (node (ref "L7") (pin "29") (pinfunction "2D6_29") (pintype "input"))
      (node (ref "L7") (pin "40") (pinfunction "1D6_40") (pintype "input"))
      (node (ref "SR7") (pin "5") (pinfunction "QF_5") (pintype "tri_state"))
    )
    (net (code "482") (name "/SR_OUT7_7") (class "Default")
      (node (ref "L7") (pin "27") (pinfunction "2D7_27") (pintype "input"))
      (node (ref "L7") (pin "38") (pinfunction "1D7_38") (pintype "input"))
      (node (ref "SR7") (pin "6") (pinfunction "QG_6") (pintype "tri_state"))
    )
    (net (code "483") (name "/SR_OUT7_8") (class "Default")
      (node (ref "L7") (pin "26") (pinfunction "2D8_26") (pintype "input"))
      (node (ref "L7") (pin "37") (pinfunction "1D8_37") (pintype "input"))
      (node (ref "SR7") (pin "7") (pinfunction "QH_7") (pintype "tri_state"))
    )
    (net (code "484") (name "/SR_OUT8_1") (class "Default")
      (node (ref "L8") (pin "36") (pinfunction "2D1_36") (pintype "input"))
      (node (ref "L8") (pin "47") (pinfunction "1D1_47") (pintype "input"))
      (node (ref "SR8") (pin "15") (pinfunction "QA_15") (pintype "tri_state"))
    )
    (net (code "485") (name "/SR_OUT8_2") (class "Default")
      (node (ref "L8") (pin "35") (pinfunction "2D2_35") (pintype "input"))
      (node (ref "L8") (pin "46") (pinfunction "1D2_46") (pintype "input"))
      (node (ref "SR8") (pin "1") (pinfunction "QB_1") (pintype "tri_state"))
    )
    (net (code "486") (name "/SR_OUT8_3") (class "Default")
      (node (ref "L8") (pin "33") (pinfunction "2D3_33") (pintype "input"))
      (node (ref "L8") (pin "44") (pinfunction "1D3_44") (pintype "input"))
      (node (ref "SR8") (pin "2") (pinfunction "QC_2") (pintype "tri_state"))
    )
    (net (code "487") (name "/SR_OUT8_4") (class "Default")
      (node (ref "L8") (pin "32") (pinfunction "2D4_32") (pintype "input"))
      (node (ref "L8") (pin "43") (pinfunction "1D4_43") (pintype "input"))
      (node (ref "SR8") (pin "3") (pinfunction "QD_3") (pintype "tri_state"))
    )
    (net (code "488") (name "/SR_OUT8_5") (class "Default")
      (node (ref "L8") (pin "30") (pinfunction "2D5_30") (pintype "input"))
      (node (ref "L8") (pin "41") (pinfunction "1D5_41") (pintype "input"))
      (node (ref "SR8") (pin "4") (pinfunction "QE_4") (pintype "tri_state"))
    )
    (net (code "489") (name "/SR_OUT8_6") (class "Default")
      (node (ref "L8") (pin "29") (pinfunction "2D6_29") (pintype "input"))
      (node (ref "L8") (pin "40") (pinfunction "1D6_40") (pintype "input"))
      (node (ref "SR8") (pin "5") (pinfunction "QF_5") (pintype "tri_state"))
    )
    (net (code "490") (name "/SR_OUT8_7") (class "Default")
      (node (ref "L8") (pin "27") (pinfunction "2D7_27") (pintype "input"))
      (node (ref "L8") (pin "38") (pinfunction "1D7_38") (pintype "input"))
      (node (ref "SR8") (pin "6") (pinfunction "QG_6") (pintype "tri_state"))
    )
    (net (code "491") (name "/SR_OUT8_8") (class "Default")
      (node (ref "L8") (pin "26") (pinfunction "2D8_26") (pintype "input"))
      (node (ref "L8") (pin "37") (pinfunction "1D8_37") (pintype "input"))
      (node (ref "SR8") (pin "7") (pinfunction "QH_7") (pintype "tri_state"))
    )
    (net (code "492") (name "/SR_OUT9_1") (class "Default")
      (node (ref "L9") (pin "36") (pinfunction "2D1_36") (pintype "input"))
      (node (ref "L9") (pin "47") (pinfunction "1D1_47") (pintype "input"))
      (node (ref "SR9") (pin "15") (pinfunction "QA_15") (pintype "tri_state"))
    )
    (net (code "493") (name "/SR_OUT9_2") (class "Default")
      (node (ref "L9") (pin "35") (pinfunction "2D2_35") (pintype "input"))
      (node (ref "L9") (pin "46") (pinfunction "1D2_46") (pintype "input"))
      (node (ref "SR9") (pin "1") (pinfunction "QB_1") (pintype "tri_state"))
    )
    (net (code "494") (name "/SR_OUT9_3") (class "Default")
      (node (ref "L9") (pin "33") (pinfunction "2D3_33") (pintype "input"))
      (node (ref "L9") (pin "44") (pinfunction "1D3_44") (pintype "input"))
      (node (ref "SR9") (pin "2") (pinfunction "QC_2") (pintype "tri_state"))
    )
    (net (code "495") (name "/SR_OUT9_4") (class "Default")
      (node (ref "L9") (pin "32") (pinfunction "2D4_32") (pintype "input"))
      (node (ref "L9") (pin "43") (pinfunction "1D4_43") (pintype "input"))
      (node (ref "SR9") (pin "3") (pinfunction "QD_3") (pintype "tri_state"))
    )
    (net (code "496") (name "/SR_OUT9_5") (class "Default")
      (node (ref "L9") (pin "30") (pinfunction "2D5_30") (pintype "input"))
      (node (ref "L9") (pin "41") (pinfunction "1D5_41") (pintype "input"))
      (node (ref "SR9") (pin "4") (pinfunction "QE_4") (pintype "tri_state"))
    )
    (net (code "497") (name "/SR_OUT9_6") (class "Default")
      (node (ref "L9") (pin "29") (pinfunction "2D6_29") (pintype "input"))
      (node (ref "L9") (pin "40") (pinfunction "1D6_40") (pintype "input"))
      (node (ref "SR9") (pin "5") (pinfunction "QF_5") (pintype "tri_state"))
    )
    (net (code "498") (name "/SR_OUT9_7") (class "Default")
      (node (ref "L9") (pin "27") (pinfunction "2D7_27") (pintype "input"))
      (node (ref "L9") (pin "38") (pinfunction "1D7_38") (pintype "input"))
      (node (ref "SR9") (pin "6") (pinfunction "QG_6") (pintype "tri_state"))
    )
    (net (code "499") (name "/SR_OUT9_8") (class "Default")
      (node (ref "L9") (pin "26") (pinfunction "2D8_26") (pintype "input"))
      (node (ref "L9") (pin "37") (pinfunction "1D8_37") (pintype "input"))
      (node (ref "SR9") (pin "7") (pinfunction "QH_7") (pintype "tri_state"))
    )
    (net (code "500") (name "/SR_OUT10_1") (class "Default")
      (node (ref "L10") (pin "36") (pinfunction "2D1_36") (pintype "input"))
      (node (ref "L10") (pin "47") (pinfunction "1D1_47") (pintype "input"))
      (node (ref "SR10") (pin "15") (pinfunction "QA_15") (pintype "tri_state"))
    )
    (net (code "501") (name "/SR_OUT10_2") (class "Default")
      (node (ref "L10") (pin "35") (pinfunction "2D2_35") (pintype "input"))
      (node (ref "L10") (pin "46") (pinfunction "1D2_46") (pintype "input"))
      (node (ref "SR10") (pin "1") (pinfunction "QB_1") (pintype "tri_state"))
    )
    (net (code "502") (name "/SR_OUT10_3") (class "Default")
      (node (ref "L10") (pin "33") (pinfunction "2D3_33") (pintype "input"))
      (node (ref "L10") (pin "44") (pinfunction "1D3_44") (pintype "input"))
      (node (ref "SR10") (pin "2") (pinfunction "QC_2") (pintype "tri_state"))
    )
    (net (code "503") (name "/SR_OUT10_4") (class "Default")
      (node (ref "L10") (pin "32") (pinfunction "2D4_32") (pintype "input"))
      (node (ref "L10") (pin "43") (pinfunction "1D4_43") (pintype "input"))
      (node (ref "SR10") (pin "3") (pinfunction "QD_3") (pintype "tri_state"))
    )
    (net (code "504") (name "/SR_OUT10_5") (class "Default")
      (node (ref "L10") (pin "30") (pinfunction "2D5_30") (pintype "input"))
      (node (ref "L10") (pin "41") (pinfunction "1D5_41") (pintype "input"))
      (node (ref "SR10") (pin "4") (pinfunction "QE_4") (pintype "tri_state"))
    )
    (net (code "505") (name "/SR_OUT10_6") (class "Default")
      (node (ref "L10") (pin "29") (pinfunction "2D6_29") (pintype "input"))
      (node (ref "L10") (pin "40") (pinfunction "1D6_40") (pintype "input"))
      (node (ref "SR10") (pin "5") (pinfunction "QF_5") (pintype "tri_state"))
    )
    (net (code "506") (name "/SR_OUT10_7") (class "Default")
      (node (ref "L10") (pin "27") (pinfunction "2D7_27") (pintype "input"))
      (node (ref "L10") (pin "38") (pinfunction "1D7_38") (pintype "input"))
      (node (ref "SR10") (pin "6") (pinfunction "QG_6") (pintype "tri_state"))
    )
    (net (code "507") (name "/SR_OUT10_8") (class "Default")
      (node (ref "L10") (pin "26") (pinfunction "2D8_26") (pintype "input"))
      (node (ref "L10") (pin "37") (pinfunction "1D8_37") (pintype "input"))
      (node (ref "SR10") (pin "7") (pinfunction "QH_7") (pintype "tri_state"))
    )
    (net (code "508") (name "/SR_OUT11_1") (class "Default")
      (node (ref "L11") (pin "36") (pinfunction "2D1_36") (pintype "input"))
      (node (ref "L11") (pin "47") (pinfunction "1D1_47") (pintype "input"))
      (node (ref "SR11") (pin "15") (pinfunction "QA_15") (pintype "tri_state"))
    )
    (net (code "509") (name "/SR_OUT11_2") (class "Default")
      (node (ref "L11") (pin "35") (pinfunction "2D2_35") (pintype "input"))
      (node (ref "L11") (pin "46") (pinfunction "1D2_46") (pintype "input"))
      (node (ref "SR11") (pin "1") (pinfunction "QB_1") (pintype "tri_state"))
    )
    (net (code "510") (name "/SR_OUT11_3") (class "Default")
      (node (ref "L11") (pin "33") (pinfunction "2D3_33") (pintype "input"))
      (node (ref "L11") (pin "44") (pinfunction "1D3_44") (pintype "input"))
      (node (ref "SR11") (pin "2") (pinfunction "QC_2") (pintype "tri_state"))
    )
    (net (code "511") (name "/SR_OUT11_4") (class "Default")
      (node (ref "L11") (pin "32") (pinfunction "2D4_32") (pintype "input"))
      (node (ref "L11") (pin "43") (pinfunction "1D4_43") (pintype "input"))
      (node (ref "SR11") (pin "3") (pinfunction "QD_3") (pintype "tri_state"))
    )
    (net (code "512") (name "/SR_OUT11_5") (class "Default")
      (node (ref "L11") (pin "30") (pinfunction "2D5_30") (pintype "input"))
      (node (ref "L11") (pin "41") (pinfunction "1D5_41") (pintype "input"))
      (node (ref "SR11") (pin "4") (pinfunction "QE_4") (pintype "tri_state"))
    )
    (net (code "513") (name "/SR_OUT11_6") (class "Default")
      (node (ref "L11") (pin "29") (pinfunction "2D6_29") (pintype "input"))
      (node (ref "L11") (pin "40") (pinfunction "1D6_40") (pintype "input"))
      (node (ref "SR11") (pin "5") (pinfunction "QF_5") (pintype "tri_state"))
    )
    (net (code "514") (name "/SR_OUT11_7") (class "Default")
      (node (ref "L11") (pin "27") (pinfunction "2D7_27") (pintype "input"))
      (node (ref "L11") (pin "38") (pinfunction "1D7_38") (pintype "input"))
      (node (ref "SR11") (pin "6") (pinfunction "QG_6") (pintype "tri_state"))
    )
    (net (code "515") (name "/SR_OUT11_8") (class "Default")
      (node (ref "L11") (pin "26") (pinfunction "2D8_26") (pintype "input"))
      (node (ref "L11") (pin "37") (pinfunction "1D8_37") (pintype "input"))
      (node (ref "SR11") (pin "7") (pinfunction "QH_7") (pintype "tri_state"))
    )
    (net (code "516") (name "/SR_OUT12_1") (class "Default")
      (node (ref "L12") (pin "36") (pinfunction "2D1_36") (pintype "input"))
      (node (ref "L12") (pin "47") (pinfunction "1D1_47") (pintype "input"))
      (node (ref "SR12") (pin "15") (pinfunction "QA_15") (pintype "tri_state"))
    )
    (net (code "517") (name "/SR_OUT12_2") (class "Default")
      (node (ref "L12") (pin "35") (pinfunction "2D2_35") (pintype "input"))
      (node (ref "L12") (pin "46") (pinfunction "1D2_46") (pintype "input"))
      (node (ref "SR12") (pin "1") (pinfunction "QB_1") (pintype "tri_state"))
    )
    (net (code "518") (name "/SR_OUT12_3") (class "Default")
      (node (ref "L12") (pin "33") (pinfunction "2D3_33") (pintype "input"))
      (node (ref "L12") (pin "44") (pinfunction "1D3_44") (pintype "input"))
      (node (ref "SR12") (pin "2") (pinfunction "QC_2") (pintype "tri_state"))
    )
    (net (code "519") (name "/SR_OUT12_4") (class "Default")
      (node (ref "L12") (pin "32") (pinfunction "2D4_32") (pintype "input"))
      (node (ref "L12") (pin "43") (pinfunction "1D4_43") (pintype "input"))
      (node (ref "SR12") (pin "3") (pinfunction "QD_3") (pintype "tri_state"))
    )
    (net (code "520") (name "/SR_OUT12_5") (class "Default")
      (node (ref "L12") (pin "30") (pinfunction "2D5_30") (pintype "input"))
      (node (ref "L12") (pin "41") (pinfunction "1D5_41") (pintype "input"))
      (node (ref "SR12") (pin "4") (pinfunction "QE_4") (pintype "tri_state"))
    )
    (net (code "521") (name "/SR_OUT12_6") (class "Default")
      (node (ref "L12") (pin "29") (pinfunction "2D6_29") (pintype "input"))
      (node (ref "L12") (pin "40") (pinfunction "1D6_40") (pintype "input"))
      (node (ref "SR12") (pin "5") (pinfunction "QF_5") (pintype "tri_state"))
    )
    (net (code "522") (name "/SR_OUT12_7") (class "Default")
      (node (ref "L12") (pin "27") (pinfunction "2D7_27") (pintype "input"))
      (node (ref "L12") (pin "38") (pinfunction "1D7_38") (pintype "input"))
      (node (ref "SR12") (pin "6") (pinfunction "QG_6") (pintype "tri_state"))
    )
    (net (code "523") (name "/SR_OUT12_8") (class "Default")
      (node (ref "L12") (pin "26") (pinfunction "2D8_26") (pintype "input"))
      (node (ref "L12") (pin "37") (pinfunction "1D8_37") (pintype "input"))
      (node (ref "SR12") (pin "7") (pinfunction "QH_7") (pintype "tri_state"))
    )
    (net (code "524") (name "/SR_OUT13_1") (class "Default")
      (node (ref "L13") (pin "36") (pinfunction "2D1_36") (pintype "input"))
      (node (ref "L13") (pin "47") (pinfunction "1D1_47") (pintype "input"))
      (node (ref "SR13") (pin "15") (pinfunction "QA_15") (pintype "tri_state"))
    )
    (net (code "525") (name "/SR_OUT13_2") (class "Default")
      (node (ref "L13") (pin "35") (pinfunction "2D2_35") (pintype "input"))
      (node (ref "L13") (pin "46") (pinfunction "1D2_46") (pintype "input"))
      (node (ref "SR13") (pin "1") (pinfunction "QB_1") (pintype "tri_state"))
    )
    (net (code "526") (name "/SR_OUT13_3") (class "Default")
      (node (ref "L13") (pin "33") (pinfunction "2D3_33") (pintype "input"))
      (node (ref "L13") (pin "44") (pinfunction "1D3_44") (pintype "input"))
      (node (ref "SR13") (pin "2") (pinfunction "QC_2") (pintype "tri_state"))
    )
    (net (code "527") (name "/SR_OUT13_4") (class "Default")
      (node (ref "L13") (pin "32") (pinfunction "2D4_32") (pintype "input"))
      (node (ref "L13") (pin "43") (pinfunction "1D4_43") (pintype "input"))
      (node (ref "SR13") (pin "3") (pinfunction "QD_3") (pintype "tri_state"))
    )
    (net (code "528") (name "/SR_OUT13_5") (class "Default")
      (node (ref "L13") (pin "30") (pinfunction "2D5_30") (pintype "input"))
      (node (ref "L13") (pin "41") (pinfunction "1D5_41") (pintype "input"))
      (node (ref "SR13") (pin "4") (pinfunction "QE_4") (pintype "tri_state"))
    )
    (net (code "529") (name "/SR_OUT13_6") (class "Default")
      (node (ref "L13") (pin "29") (pinfunction "2D6_29") (pintype "input"))
      (node (ref "L13") (pin "40") (pinfunction "1D6_40") (pintype "input"))
      (node (ref "SR13") (pin "5") (pinfunction "QF_5") (pintype "tri_state"))
    )
    (net (code "530") (name "/SR_OUT13_7") (class "Default")
      (node (ref "L13") (pin "27") (pinfunction "2D7_27") (pintype "input"))
      (node (ref "L13") (pin "38") (pinfunction "1D7_38") (pintype "input"))
      (node (ref "SR13") (pin "6") (pinfunction "QG_6") (pintype "tri_state"))
    )
    (net (code "531") (name "/SR_OUT13_8") (class "Default")
      (node (ref "L13") (pin "26") (pinfunction "2D8_26") (pintype "input"))
      (node (ref "L13") (pin "37") (pinfunction "1D8_37") (pintype "input"))
      (node (ref "SR13") (pin "7") (pinfunction "QH_7") (pintype "tri_state"))
    )
    (net (code "532") (name "/SR_OUT14_1") (class "Default")
      (node (ref "L14") (pin "36") (pinfunction "2D1_36") (pintype "input"))
      (node (ref "L14") (pin "47") (pinfunction "1D1_47") (pintype "input"))
      (node (ref "SR14") (pin "15") (pinfunction "QA_15") (pintype "tri_state"))
    )
    (net (code "533") (name "/SR_OUT14_2") (class "Default")
      (node (ref "L14") (pin "35") (pinfunction "2D2_35") (pintype "input"))
      (node (ref "L14") (pin "46") (pinfunction "1D2_46") (pintype "input"))
      (node (ref "SR14") (pin "1") (pinfunction "QB_1") (pintype "tri_state"))
    )
    (net (code "534") (name "/SR_OUT14_3") (class "Default")
      (node (ref "L14") (pin "33") (pinfunction "2D3_33") (pintype "input"))
      (node (ref "L14") (pin "44") (pinfunction "1D3_44") (pintype "input"))
      (node (ref "SR14") (pin "2") (pinfunction "QC_2") (pintype "tri_state"))
    )
    (net (code "535") (name "/SR_OUT14_4") (class "Default")
      (node (ref "L14") (pin "32") (pinfunction "2D4_32") (pintype "input"))
      (node (ref "L14") (pin "43") (pinfunction "1D4_43") (pintype "input"))
      (node (ref "SR14") (pin "3") (pinfunction "QD_3") (pintype "tri_state"))
    )
    (net (code "536") (name "/SR_OUT14_5") (class "Default")
      (node (ref "L14") (pin "30") (pinfunction "2D5_30") (pintype "input"))
      (node (ref "L14") (pin "41") (pinfunction "1D5_41") (pintype "input"))
      (node (ref "SR14") (pin "4") (pinfunction "QE_4") (pintype "tri_state"))
    )
    (net (code "537") (name "/SR_OUT14_6") (class "Default")
      (node (ref "L14") (pin "29") (pinfunction "2D6_29") (pintype "input"))
      (node (ref "L14") (pin "40") (pinfunction "1D6_40") (pintype "input"))
      (node (ref "SR14") (pin "5") (pinfunction "QF_5") (pintype "tri_state"))
    )
    (net (code "538") (name "/SR_OUT14_7") (class "Default")
      (node (ref "L14") (pin "27") (pinfunction "2D7_27") (pintype "input"))
      (node (ref "L14") (pin "38") (pinfunction "1D7_38") (pintype "input"))
      (node (ref "SR14") (pin "6") (pinfunction "QG_6") (pintype "tri_state"))
    )
    (net (code "539") (name "/SR_OUT14_8") (class "Default")
      (node (ref "L14") (pin "26") (pinfunction "2D8_26") (pintype "input"))
      (node (ref "L14") (pin "37") (pinfunction "1D8_37") (pintype "input"))
      (node (ref "SR14") (pin "7") (pinfunction "QH_7") (pintype "tri_state"))
    )
    (net (code "540") (name "/SR_OUT15_1") (class "Default")
      (node (ref "L15") (pin "36") (pinfunction "2D1_36") (pintype "input"))
      (node (ref "L15") (pin "47") (pinfunction "1D1_47") (pintype "input"))
      (node (ref "SR15") (pin "15") (pinfunction "QA_15") (pintype "tri_state"))
    )
    (net (code "541") (name "/SR_OUT15_2") (class "Default")
      (node (ref "L15") (pin "35") (pinfunction "2D2_35") (pintype "input"))
      (node (ref "L15") (pin "46") (pinfunction "1D2_46") (pintype "input"))
      (node (ref "SR15") (pin "1") (pinfunction "QB_1") (pintype "tri_state"))
    )
    (net (code "542") (name "/SR_OUT15_3") (class "Default")
      (node (ref "L15") (pin "33") (pinfunction "2D3_33") (pintype "input"))
      (node (ref "L15") (pin "44") (pinfunction "1D3_44") (pintype "input"))
      (node (ref "SR15") (pin "2") (pinfunction "QC_2") (pintype "tri_state"))
    )
    (net (code "543") (name "/SR_OUT15_4") (class "Default")
      (node (ref "L15") (pin "32") (pinfunction "2D4_32") (pintype "input"))
      (node (ref "L15") (pin "43") (pinfunction "1D4_43") (pintype "input"))
      (node (ref "SR15") (pin "3") (pinfunction "QD_3") (pintype "tri_state"))
    )
    (net (code "544") (name "/SR_OUT15_5") (class "Default")
      (node (ref "L15") (pin "30") (pinfunction "2D5_30") (pintype "input"))
      (node (ref "L15") (pin "41") (pinfunction "1D5_41") (pintype "input"))
      (node (ref "SR15") (pin "4") (pinfunction "QE_4") (pintype "tri_state"))
    )
    (net (code "545") (name "/SR_OUT15_6") (class "Default")
      (node (ref "L15") (pin "29") (pinfunction "2D6_29") (pintype "input"))
      (node (ref "L15") (pin "40") (pinfunction "1D6_40") (pintype "input"))
      (node (ref "SR15") (pin "5") (pinfunction "QF_5") (pintype "tri_state"))
    )
    (net (code "546") (name "/SR_OUT15_7") (class "Default")
      (node (ref "L15") (pin "27") (pinfunction "2D7_27") (pintype "input"))
      (node (ref "L15") (pin "38") (pinfunction "1D7_38") (pintype "input"))
      (node (ref "SR15") (pin "6") (pinfunction "QG_6") (pintype "tri_state"))
    )
    (net (code "547") (name "/SR_OUT15_8") (class "Default")
      (node (ref "L15") (pin "26") (pinfunction "2D8_26") (pintype "input"))
      (node (ref "L15") (pin "37") (pinfunction "1D8_37") (pintype "input"))
      (node (ref "SR15") (pin "7") (pinfunction "QH_7") (pintype "tri_state"))
    )
    (net (code "548") (name "/SR_OUT16_1") (class "Default")
      (node (ref "L16") (pin "36") (pinfunction "2D1_36") (pintype "input"))
      (node (ref "L16") (pin "47") (pinfunction "1D1_47") (pintype "input"))
      (node (ref "SR16") (pin "15") (pinfunction "QA_15") (pintype "tri_state"))
    )
    (net (code "549") (name "/SR_OUT16_2") (class "Default")
      (node (ref "L16") (pin "35") (pinfunction "2D2_35") (pintype "input"))
      (node (ref "L16") (pin "46") (pinfunction "1D2_46") (pintype "input"))
      (node (ref "SR16") (pin "1") (pinfunction "QB_1") (pintype "tri_state"))
    )
    (net (code "550") (name "/SR_OUT16_3") (class "Default")
      (node (ref "L16") (pin "33") (pinfunction "2D3_33") (pintype "input"))
      (node (ref "L16") (pin "44") (pinfunction "1D3_44") (pintype "input"))
      (node (ref "SR16") (pin "2") (pinfunction "QC_2") (pintype "tri_state"))
    )
    (net (code "551") (name "/SR_OUT16_4") (class "Default")
      (node (ref "L16") (pin "32") (pinfunction "2D4_32") (pintype "input"))
      (node (ref "L16") (pin "43") (pinfunction "1D4_43") (pintype "input"))
      (node (ref "SR16") (pin "3") (pinfunction "QD_3") (pintype "tri_state"))
    )
    (net (code "552") (name "/SR_OUT16_5") (class "Default")
      (node (ref "L16") (pin "30") (pinfunction "2D5_30") (pintype "input"))
      (node (ref "L16") (pin "41") (pinfunction "1D5_41") (pintype "input"))
      (node (ref "SR16") (pin "4") (pinfunction "QE_4") (pintype "tri_state"))
    )
    (net (code "553") (name "/SR_OUT16_6") (class "Default")
      (node (ref "L16") (pin "29") (pinfunction "2D6_29") (pintype "input"))
      (node (ref "L16") (pin "40") (pinfunction "1D6_40") (pintype "input"))
      (node (ref "SR16") (pin "5") (pinfunction "QF_5") (pintype "tri_state"))
    )
    (net (code "554") (name "/SR_OUT16_7") (class "Default")
      (node (ref "L16") (pin "27") (pinfunction "2D7_27") (pintype "input"))
      (node (ref "L16") (pin "38") (pinfunction "1D7_38") (pintype "input"))
      (node (ref "SR16") (pin "6") (pinfunction "QG_6") (pintype "tri_state"))
    )
    (net (code "555") (name "/SR_OUT16_8") (class "Default")
      (node (ref "L16") (pin "26") (pinfunction "2D8_26") (pintype "input"))
      (node (ref "L16") (pin "37") (pinfunction "1D8_37") (pintype "input"))
      (node (ref "SR16") (pin "7") (pinfunction "QH_7") (pintype "tri_state"))
    )
    (net (code "556") (name "/SR_OUT17_1") (class "Default")
      (node (ref "L17") (pin "36") (pinfunction "2D1_36") (pintype "input"))
      (node (ref "L17") (pin "47") (pinfunction "1D1_47") (pintype "input"))
      (node (ref "SR17") (pin "15") (pinfunction "QA_15") (pintype "tri_state"))
    )
    (net (code "557") (name "/SR_OUT17_2") (class "Default")
      (node (ref "L17") (pin "35") (pinfunction "2D2_35") (pintype "input"))
      (node (ref "L17") (pin "46") (pinfunction "1D2_46") (pintype "input"))
      (node (ref "SR17") (pin "1") (pinfunction "QB_1") (pintype "tri_state"))
    )
    (net (code "558") (name "/SR_OUT17_3") (class "Default")
      (node (ref "L17") (pin "33") (pinfunction "2D3_33") (pintype "input"))
      (node (ref "L17") (pin "44") (pinfunction "1D3_44") (pintype "input"))
      (node (ref "SR17") (pin "2") (pinfunction "QC_2") (pintype "tri_state"))
    )
    (net (code "559") (name "/SR_OUT17_4") (class "Default")
      (node (ref "L17") (pin "32") (pinfunction "2D4_32") (pintype "input"))
      (node (ref "L17") (pin "43") (pinfunction "1D4_43") (pintype "input"))
      (node (ref "SR17") (pin "3") (pinfunction "QD_3") (pintype "tri_state"))
    )
    (net (code "560") (name "/SR_OUT17_5") (class "Default")
      (node (ref "L17") (pin "30") (pinfunction "2D5_30") (pintype "input"))
      (node (ref "L17") (pin "41") (pinfunction "1D5_41") (pintype "input"))
      (node (ref "SR17") (pin "4") (pinfunction "QE_4") (pintype "tri_state"))
    )
    (net (code "561") (name "/SR_OUT17_6") (class "Default")
      (node (ref "L17") (pin "29") (pinfunction "2D6_29") (pintype "input"))
      (node (ref "L17") (pin "40") (pinfunction "1D6_40") (pintype "input"))
      (node (ref "SR17") (pin "5") (pinfunction "QF_5") (pintype "tri_state"))
    )
    (net (code "562") (name "/SR_OUT17_7") (class "Default")
      (node (ref "L17") (pin "27") (pinfunction "2D7_27") (pintype "input"))
      (node (ref "L17") (pin "38") (pinfunction "1D7_38") (pintype "input"))
      (node (ref "SR17") (pin "6") (pinfunction "QG_6") (pintype "tri_state"))
    )
    (net (code "563") (name "/SR_OUT17_8") (class "Default")
      (node (ref "L17") (pin "26") (pinfunction "2D8_26") (pintype "input"))
      (node (ref "L17") (pin "37") (pinfunction "1D8_37") (pintype "input"))
      (node (ref "SR17") (pin "7") (pinfunction "QH_7") (pintype "tri_state"))
    )
    (net (code "564") (name "/SR_OUT18_1") (class "Default")
      (node (ref "L18") (pin "36") (pinfunction "2D1_36") (pintype "input"))
      (node (ref "L18") (pin "47") (pinfunction "1D1_47") (pintype "input"))
      (node (ref "SR18") (pin "15") (pinfunction "QA_15") (pintype "tri_state"))
    )
    (net (code "565") (name "/SR_OUT18_2") (class "Default")
      (node (ref "L18") (pin "35") (pinfunction "2D2_35") (pintype "input"))
      (node (ref "L18") (pin "46") (pinfunction "1D2_46") (pintype "input"))
      (node (ref "SR18") (pin "1") (pinfunction "QB_1") (pintype "tri_state"))
    )
    (net (code "566") (name "/SR_OUT18_3") (class "Default")
      (node (ref "L18") (pin "33") (pinfunction "2D3_33") (pintype "input"))
      (node (ref "L18") (pin "44") (pinfunction "1D3_44") (pintype "input"))
      (node (ref "SR18") (pin "2") (pinfunction "QC_2") (pintype "tri_state"))
    )
    (net (code "567") (name "/SR_OUT18_4") (class "Default")
      (node (ref "L18") (pin "32") (pinfunction "2D4_32") (pintype "input"))
      (node (ref "L18") (pin "43") (pinfunction "1D4_43") (pintype "input"))
      (node (ref "SR18") (pin "3") (pinfunction "QD_3") (pintype "tri_state"))
    )
    (net (code "568") (name "/SR_OUT18_5") (class "Default")
      (node (ref "L18") (pin "30") (pinfunction "2D5_30") (pintype "input"))
      (node (ref "L18") (pin "41") (pinfunction "1D5_41") (pintype "input"))
      (node (ref "SR18") (pin "4") (pinfunction "QE_4") (pintype "tri_state"))
    )
    (net (code "569") (name "/SR_OUT18_6") (class "Default")
      (node (ref "L18") (pin "29") (pinfunction "2D6_29") (pintype "input"))
      (node (ref "L18") (pin "40") (pinfunction "1D6_40") (pintype "input"))
      (node (ref "SR18") (pin "5") (pinfunction "QF_5") (pintype "tri_state"))
    )
    (net (code "570") (name "/SR_OUT18_7") (class "Default")
      (node (ref "L18") (pin "27") (pinfunction "2D7_27") (pintype "input"))
      (node (ref "L18") (pin "38") (pinfunction "1D7_38") (pintype "input"))
      (node (ref "SR18") (pin "6") (pinfunction "QG_6") (pintype "tri_state"))
    )
    (net (code "571") (name "/SR_OUT18_8") (class "Default")
      (node (ref "L18") (pin "26") (pinfunction "2D8_26") (pintype "input"))
      (node (ref "L18") (pin "37") (pinfunction "1D8_37") (pintype "input"))
      (node (ref "SR18") (pin "7") (pinfunction "QH_7") (pintype "tri_state"))
    )
    (net (code "572") (name "/SR_OUT19_1") (class "Default")
      (node (ref "L19") (pin "36") (pinfunction "2D1_36") (pintype "input"))
      (node (ref "L19") (pin "47") (pinfunction "1D1_47") (pintype "input"))
      (node (ref "SR19") (pin "15") (pinfunction "QA_15") (pintype "tri_state"))
    )
    (net (code "573") (name "/SR_OUT19_2") (class "Default")
      (node (ref "L19") (pin "35") (pinfunction "2D2_35") (pintype "input"))
      (node (ref "L19") (pin "46") (pinfunction "1D2_46") (pintype "input"))
      (node (ref "SR19") (pin "1") (pinfunction "QB_1") (pintype "tri_state"))
    )
    (net (code "574") (name "/SR_OUT19_3") (class "Default")
      (node (ref "L19") (pin "33") (pinfunction "2D3_33") (pintype "input"))
      (node (ref "L19") (pin "44") (pinfunction "1D3_44") (pintype "input"))
      (node (ref "SR19") (pin "2") (pinfunction "QC_2") (pintype "tri_state"))
    )
    (net (code "575") (name "/SR_OUT19_4") (class "Default")
      (node (ref "L19") (pin "32") (pinfunction "2D4_32") (pintype "input"))
      (node (ref "L19") (pin "43") (pinfunction "1D4_43") (pintype "input"))
      (node (ref "SR19") (pin "3") (pinfunction "QD_3") (pintype "tri_state"))
    )
    (net (code "576") (name "/SR_OUT19_5") (class "Default")
      (node (ref "L19") (pin "30") (pinfunction "2D5_30") (pintype "input"))
      (node (ref "L19") (pin "41") (pinfunction "1D5_41") (pintype "input"))
      (node (ref "SR19") (pin "4") (pinfunction "QE_4") (pintype "tri_state"))
    )
    (net (code "577") (name "/SR_OUT19_6") (class "Default")
      (node (ref "L19") (pin "29") (pinfunction "2D6_29") (pintype "input"))
      (node (ref "L19") (pin "40") (pinfunction "1D6_40") (pintype "input"))
      (node (ref "SR19") (pin "5") (pinfunction "QF_5") (pintype "tri_state"))
    )
    (net (code "578") (name "/SR_OUT19_7") (class "Default")
      (node (ref "L19") (pin "27") (pinfunction "2D7_27") (pintype "input"))
      (node (ref "L19") (pin "38") (pinfunction "1D7_38") (pintype "input"))
      (node (ref "SR19") (pin "6") (pinfunction "QG_6") (pintype "tri_state"))
    )
    (net (code "579") (name "/SR_OUT19_8") (class "Default")
      (node (ref "L19") (pin "26") (pinfunction "2D8_26") (pintype "input"))
      (node (ref "L19") (pin "37") (pinfunction "1D8_37") (pintype "input"))
      (node (ref "SR19") (pin "7") (pinfunction "QH_7") (pintype "tri_state"))
    )
    (net (code "580") (name "/SR_OUT20_1") (class "Default")
      (node (ref "L20") (pin "36") (pinfunction "2D1_36") (pintype "input"))
      (node (ref "L20") (pin "47") (pinfunction "1D1_47") (pintype "input"))
      (node (ref "SR20") (pin "15") (pinfunction "QA_15") (pintype "tri_state"))
    )
    (net (code "581") (name "/SR_OUT20_2") (class "Default")
      (node (ref "L20") (pin "35") (pinfunction "2D2_35") (pintype "input"))
      (node (ref "L20") (pin "46") (pinfunction "1D2_46") (pintype "input"))
      (node (ref "SR20") (pin "1") (pinfunction "QB_1") (pintype "tri_state"))
    )
    (net (code "582") (name "/SR_OUT20_3") (class "Default")
      (node (ref "L20") (pin "33") (pinfunction "2D3_33") (pintype "input"))
      (node (ref "L20") (pin "44") (pinfunction "1D3_44") (pintype "input"))
      (node (ref "SR20") (pin "2") (pinfunction "QC_2") (pintype "tri_state"))
    )
    (net (code "583") (name "/SR_OUT20_4") (class "Default")
      (node (ref "L20") (pin "32") (pinfunction "2D4_32") (pintype "input"))
      (node (ref "L20") (pin "43") (pinfunction "1D4_43") (pintype "input"))
      (node (ref "SR20") (pin "3") (pinfunction "QD_3") (pintype "tri_state"))
    )
    (net (code "584") (name "/SR_OUT20_5") (class "Default")
      (node (ref "L20") (pin "30") (pinfunction "2D5_30") (pintype "input"))
      (node (ref "L20") (pin "41") (pinfunction "1D5_41") (pintype "input"))
      (node (ref "SR20") (pin "4") (pinfunction "QE_4") (pintype "tri_state"))
    )
    (net (code "585") (name "/SR_OUT20_6") (class "Default")
      (node (ref "L20") (pin "29") (pinfunction "2D6_29") (pintype "input"))
      (node (ref "L20") (pin "40") (pinfunction "1D6_40") (pintype "input"))
      (node (ref "SR20") (pin "5") (pinfunction "QF_5") (pintype "tri_state"))
    )
    (net (code "586") (name "/SR_OUT20_7") (class "Default")
      (node (ref "L20") (pin "27") (pinfunction "2D7_27") (pintype "input"))
      (node (ref "L20") (pin "38") (pinfunction "1D7_38") (pintype "input"))
      (node (ref "SR20") (pin "6") (pinfunction "QG_6") (pintype "tri_state"))
    )
    (net (code "587") (name "/SR_OUT20_8") (class "Default")
      (node (ref "L20") (pin "26") (pinfunction "2D8_26") (pintype "input"))
      (node (ref "L20") (pin "37") (pinfunction "1D8_37") (pintype "input"))
      (node (ref "SR20") (pin "7") (pinfunction "QH_7") (pintype "tri_state"))
    )
    (net (code "588") (name "/SR_OUT21_1") (class "Default")
      (node (ref "L21") (pin "36") (pinfunction "2D1_36") (pintype "input"))
      (node (ref "L21") (pin "47") (pinfunction "1D1_47") (pintype "input"))
      (node (ref "SR21") (pin "15") (pinfunction "QA_15") (pintype "tri_state"))
    )
    (net (code "589") (name "/SR_OUT21_2") (class "Default")
      (node (ref "L21") (pin "35") (pinfunction "2D2_35") (pintype "input"))
      (node (ref "L21") (pin "46") (pinfunction "1D2_46") (pintype "input"))
      (node (ref "SR21") (pin "1") (pinfunction "QB_1") (pintype "tri_state"))
    )
    (net (code "590") (name "/SR_OUT21_3") (class "Default")
      (node (ref "L21") (pin "33") (pinfunction "2D3_33") (pintype "input"))
      (node (ref "L21") (pin "44") (pinfunction "1D3_44") (pintype "input"))
      (node (ref "SR21") (pin "2") (pinfunction "QC_2") (pintype "tri_state"))
    )
    (net (code "591") (name "/SR_OUT21_4") (class "Default")
      (node (ref "L21") (pin "32") (pinfunction "2D4_32") (pintype "input"))
      (node (ref "L21") (pin "43") (pinfunction "1D4_43") (pintype "input"))
      (node (ref "SR21") (pin "3") (pinfunction "QD_3") (pintype "tri_state"))
    )
    (net (code "592") (name "/SR_OUT21_5") (class "Default")
      (node (ref "L21") (pin "30") (pinfunction "2D5_30") (pintype "input"))
      (node (ref "L21") (pin "41") (pinfunction "1D5_41") (pintype "input"))
      (node (ref "SR21") (pin "4") (pinfunction "QE_4") (pintype "tri_state"))
    )
    (net (code "593") (name "/SR_OUT21_6") (class "Default")
      (node (ref "L21") (pin "29") (pinfunction "2D6_29") (pintype "input"))
      (node (ref "L21") (pin "40") (pinfunction "1D6_40") (pintype "input"))
      (node (ref "SR21") (pin "5") (pinfunction "QF_5") (pintype "tri_state"))
    )
    (net (code "594") (name "/SR_OUT21_7") (class "Default")
      (node (ref "L21") (pin "27") (pinfunction "2D7_27") (pintype "input"))
      (node (ref "L21") (pin "38") (pinfunction "1D7_38") (pintype "input"))
      (node (ref "SR21") (pin "6") (pinfunction "QG_6") (pintype "tri_state"))
    )
    (net (code "595") (name "/SR_OUT21_8") (class "Default")
      (node (ref "L21") (pin "26") (pinfunction "2D8_26") (pintype "input"))
      (node (ref "L21") (pin "37") (pinfunction "1D8_37") (pintype "input"))
      (node (ref "SR21") (pin "7") (pinfunction "QH_7") (pintype "tri_state"))
    )
    (net (code "596") (name "/SR_OUT22_1") (class "Default")
      (node (ref "L22") (pin "36") (pinfunction "2D1_36") (pintype "input"))
      (node (ref "L22") (pin "47") (pinfunction "1D1_47") (pintype "input"))
      (node (ref "SR22") (pin "15") (pinfunction "QA_15") (pintype "tri_state"))
    )
    (net (code "597") (name "/SR_OUT22_2") (class "Default")
      (node (ref "L22") (pin "35") (pinfunction "2D2_35") (pintype "input"))
      (node (ref "L22") (pin "46") (pinfunction "1D2_46") (pintype "input"))
      (node (ref "SR22") (pin "1") (pinfunction "QB_1") (pintype "tri_state"))
    )
    (net (code "598") (name "/SR_OUT22_3") (class "Default")
      (node (ref "L22") (pin "33") (pinfunction "2D3_33") (pintype "input"))
      (node (ref "L22") (pin "44") (pinfunction "1D3_44") (pintype "input"))
      (node (ref "SR22") (pin "2") (pinfunction "QC_2") (pintype "tri_state"))
    )
    (net (code "599") (name "/SR_OUT22_4") (class "Default")
      (node (ref "L22") (pin "32") (pinfunction "2D4_32") (pintype "input"))
      (node (ref "L22") (pin "43") (pinfunction "1D4_43") (pintype "input"))
      (node (ref "SR22") (pin "3") (pinfunction "QD_3") (pintype "tri_state"))
    )
    (net (code "600") (name "/SR_OUT22_5") (class "Default")
      (node (ref "L22") (pin "30") (pinfunction "2D5_30") (pintype "input"))
      (node (ref "L22") (pin "41") (pinfunction "1D5_41") (pintype "input"))
      (node (ref "SR22") (pin "4") (pinfunction "QE_4") (pintype "tri_state"))
    )
    (net (code "601") (name "/SR_OUT22_6") (class "Default")
      (node (ref "L22") (pin "29") (pinfunction "2D6_29") (pintype "input"))
      (node (ref "L22") (pin "40") (pinfunction "1D6_40") (pintype "input"))
      (node (ref "SR22") (pin "5") (pinfunction "QF_5") (pintype "tri_state"))
    )
    (net (code "602") (name "/SR_OUT22_7") (class "Default")
      (node (ref "L22") (pin "27") (pinfunction "2D7_27") (pintype "input"))
      (node (ref "L22") (pin "38") (pinfunction "1D7_38") (pintype "input"))
      (node (ref "SR22") (pin "6") (pinfunction "QG_6") (pintype "tri_state"))
    )
    (net (code "603") (name "/SR_OUT22_8") (class "Default")
      (node (ref "L22") (pin "26") (pinfunction "2D8_26") (pintype "input"))
      (node (ref "L22") (pin "37") (pinfunction "1D8_37") (pintype "input"))
      (node (ref "SR22") (pin "7") (pinfunction "QH_7") (pintype "tri_state"))
    )
    (net (code "604") (name "/SR_OUT23_1") (class "Default")
      (node (ref "L23") (pin "36") (pinfunction "2D1_36") (pintype "input"))
      (node (ref "L23") (pin "47") (pinfunction "1D1_47") (pintype "input"))
      (node (ref "SR23") (pin "15") (pinfunction "QA_15") (pintype "tri_state"))
    )
    (net (code "605") (name "/SR_OUT23_2") (class "Default")
      (node (ref "L23") (pin "35") (pinfunction "2D2_35") (pintype "input"))
      (node (ref "L23") (pin "46") (pinfunction "1D2_46") (pintype "input"))
      (node (ref "SR23") (pin "1") (pinfunction "QB_1") (pintype "tri_state"))
    )
    (net (code "606") (name "/SR_OUT23_3") (class "Default")
      (node (ref "L23") (pin "33") (pinfunction "2D3_33") (pintype "input"))
      (node (ref "L23") (pin "44") (pinfunction "1D3_44") (pintype "input"))
      (node (ref "SR23") (pin "2") (pinfunction "QC_2") (pintype "tri_state"))
    )
    (net (code "607") (name "/SR_OUT23_4") (class "Default")
      (node (ref "L23") (pin "32") (pinfunction "2D4_32") (pintype "input"))
      (node (ref "L23") (pin "43") (pinfunction "1D4_43") (pintype "input"))
      (node (ref "SR23") (pin "3") (pinfunction "QD_3") (pintype "tri_state"))
    )
    (net (code "608") (name "/SR_OUT23_5") (class "Default")
      (node (ref "L23") (pin "30") (pinfunction "2D5_30") (pintype "input"))
      (node (ref "L23") (pin "41") (pinfunction "1D5_41") (pintype "input"))
      (node (ref "SR23") (pin "4") (pinfunction "QE_4") (pintype "tri_state"))
    )
    (net (code "609") (name "/SR_OUT23_6") (class "Default")
      (node (ref "L23") (pin "29") (pinfunction "2D6_29") (pintype "input"))
      (node (ref "L23") (pin "40") (pinfunction "1D6_40") (pintype "input"))
      (node (ref "SR23") (pin "5") (pinfunction "QF_5") (pintype "tri_state"))
    )
    (net (code "610") (name "/SR_OUT23_7") (class "Default")
      (node (ref "L23") (pin "27") (pinfunction "2D7_27") (pintype "input"))
      (node (ref "L23") (pin "38") (pinfunction "1D7_38") (pintype "input"))
      (node (ref "SR23") (pin "6") (pinfunction "QG_6") (pintype "tri_state"))
    )
    (net (code "611") (name "/SR_OUT23_8") (class "Default")
      (node (ref "L23") (pin "26") (pinfunction "2D8_26") (pintype "input"))
      (node (ref "L23") (pin "37") (pinfunction "1D8_37") (pintype "input"))
      (node (ref "SR23") (pin "7") (pinfunction "QH_7") (pintype "tri_state"))
    )
    (net (code "612") (name "/SR_OUT24_1") (class "Default")
      (node (ref "L24") (pin "36") (pinfunction "2D1_36") (pintype "input"))
      (node (ref "L24") (pin "47") (pinfunction "1D1_47") (pintype "input"))
      (node (ref "SR24") (pin "15") (pinfunction "QA_15") (pintype "tri_state"))
    )
    (net (code "613") (name "/SR_OUT24_2") (class "Default")
      (node (ref "L24") (pin "35") (pinfunction "2D2_35") (pintype "input"))
      (node (ref "L24") (pin "46") (pinfunction "1D2_46") (pintype "input"))
      (node (ref "SR24") (pin "1") (pinfunction "QB_1") (pintype "tri_state"))
    )
    (net (code "614") (name "/SR_OUT24_3") (class "Default")
      (node (ref "L24") (pin "33") (pinfunction "2D3_33") (pintype "input"))
      (node (ref "L24") (pin "44") (pinfunction "1D3_44") (pintype "input"))
      (node (ref "SR24") (pin "2") (pinfunction "QC_2") (pintype "tri_state"))
    )
    (net (code "615") (name "/SR_OUT24_4") (class "Default")
      (node (ref "L24") (pin "32") (pinfunction "2D4_32") (pintype "input"))
      (node (ref "L24") (pin "43") (pinfunction "1D4_43") (pintype "input"))
      (node (ref "SR24") (pin "3") (pinfunction "QD_3") (pintype "tri_state"))
    )
    (net (code "616") (name "/SR_OUT24_5") (class "Default")
      (node (ref "L24") (pin "30") (pinfunction "2D5_30") (pintype "input"))
      (node (ref "L24") (pin "41") (pinfunction "1D5_41") (pintype "input"))
      (node (ref "SR24") (pin "4") (pinfunction "QE_4") (pintype "tri_state"))
    )
    (net (code "617") (name "/SR_OUT24_6") (class "Default")
      (node (ref "L24") (pin "29") (pinfunction "2D6_29") (pintype "input"))
      (node (ref "L24") (pin "40") (pinfunction "1D6_40") (pintype "input"))
      (node (ref "SR24") (pin "5") (pinfunction "QF_5") (pintype "tri_state"))
    )
    (net (code "618") (name "/SR_OUT24_7") (class "Default")
      (node (ref "L24") (pin "27") (pinfunction "2D7_27") (pintype "input"))
      (node (ref "L24") (pin "38") (pinfunction "1D7_38") (pintype "input"))
      (node (ref "SR24") (pin "6") (pinfunction "QG_6") (pintype "tri_state"))
    )
    (net (code "619") (name "/SR_OUT24_8") (class "Default")
      (node (ref "L24") (pin "26") (pinfunction "2D8_26") (pintype "input"))
      (node (ref "L24") (pin "37") (pinfunction "1D8_37") (pintype "input"))
      (node (ref "SR24") (pin "7") (pinfunction "QH_7") (pintype "tri_state"))
    )
    (net (code "620") (name "/SR_OUT25_1") (class "Default")
      (node (ref "L25") (pin "36") (pinfunction "2D1_36") (pintype "input"))
      (node (ref "L25") (pin "47") (pinfunction "1D1_47") (pintype "input"))
      (node (ref "SR25") (pin "15") (pinfunction "QA_15") (pintype "tri_state"))
    )
    (net (code "621") (name "/SR_OUT25_2") (class "Default")
      (node (ref "L25") (pin "35") (pinfunction "2D2_35") (pintype "input"))
      (node (ref "L25") (pin "46") (pinfunction "1D2_46") (pintype "input"))
      (node (ref "SR25") (pin "1") (pinfunction "QB_1") (pintype "tri_state"))
    )
    (net (code "622") (name "/SR_OUT25_3") (class "Default")
      (node (ref "L25") (pin "33") (pinfunction "2D3_33") (pintype "input"))
      (node (ref "L25") (pin "44") (pinfunction "1D3_44") (pintype "input"))
      (node (ref "SR25") (pin "2") (pinfunction "QC_2") (pintype "tri_state"))
    )
    (net (code "623") (name "/SR_OUT25_4") (class "Default")
      (node (ref "L25") (pin "32") (pinfunction "2D4_32") (pintype "input"))
      (node (ref "L25") (pin "43") (pinfunction "1D4_43") (pintype "input"))
      (node (ref "SR25") (pin "3") (pinfunction "QD_3") (pintype "tri_state"))
    )
    (net (code "624") (name "/SR_OUT25_5") (class "Default")
      (node (ref "L25") (pin "30") (pinfunction "2D5_30") (pintype "input"))
      (node (ref "L25") (pin "41") (pinfunction "1D5_41") (pintype "input"))
      (node (ref "SR25") (pin "4") (pinfunction "QE_4") (pintype "tri_state"))
    )
    (net (code "625") (name "/SR_OUT25_6") (class "Default")
      (node (ref "L25") (pin "29") (pinfunction "2D6_29") (pintype "input"))
      (node (ref "L25") (pin "40") (pinfunction "1D6_40") (pintype "input"))
      (node (ref "SR25") (pin "5") (pinfunction "QF_5") (pintype "tri_state"))
    )
    (net (code "626") (name "/SR_OUT25_7") (class "Default")
      (node (ref "L25") (pin "27") (pinfunction "2D7_27") (pintype "input"))
      (node (ref "L25") (pin "38") (pinfunction "1D7_38") (pintype "input"))
      (node (ref "SR25") (pin "6") (pinfunction "QG_6") (pintype "tri_state"))
    )
    (net (code "627") (name "/SR_OUT25_8") (class "Default")
      (node (ref "L25") (pin "26") (pinfunction "2D8_26") (pintype "input"))
      (node (ref "L25") (pin "37") (pinfunction "1D8_37") (pintype "input"))
      (node (ref "SR25") (pin "7") (pinfunction "QH_7") (pintype "tri_state"))
    )
    (net (code "628") (name "/VCC_LATCH") (class "Default")
      (node (ref "L1") (pin "18") (pinfunction "1_VCC_18") (pintype "power_in"))
      (node (ref "L1") (pin "31") (pinfunction "2_VCC_31") (pintype "power_in"))
      (node (ref "L1") (pin "42") (pinfunction "3_VCC_42") (pintype "power_in"))
      (node (ref "L1") (pin "7") (pinfunction "4_VCC_7") (pintype "power_in"))
      (node (ref "L10") (pin "18") (pinfunction "1_VCC_18") (pintype "power_in"))
      (node (ref "L10") (pin "31") (pinfunction "2_VCC_31") (pintype "power_in"))
      (node (ref "L10") (pin "42") (pinfunction "3_VCC_42") (pintype "power_in"))
      (node (ref "L10") (pin "7") (pinfunction "4_VCC_7") (pintype "power_in"))
      (node (ref "L11") (pin "18") (pinfunction "1_VCC_18") (pintype "power_in"))
      (node (ref "L11") (pin "31") (pinfunction "2_VCC_31") (pintype "power_in"))
      (node (ref "L11") (pin "42") (pinfunction "3_VCC_42") (pintype "power_in"))
      (node (ref "L11") (pin "7") (pinfunction "4_VCC_7") (pintype "power_in"))
      (node (ref "L12") (pin "18") (pinfunction "1_VCC_18") (pintype "power_in"))
      (node (ref "L12") (pin "31") (pinfunction "2_VCC_31") (pintype "power_in"))
      (node (ref "L12") (pin "42") (pinfunction "3_VCC_42") (pintype "power_in"))
      (node (ref "L12") (pin "7") (pinfunction "4_VCC_7") (pintype "power_in"))
      (node (ref "L13") (pin "18") (pinfunction "1_VCC_18") (pintype "power_in"))
      (node (ref "L13") (pin "31") (pinfunction "2_VCC_31") (pintype "power_in"))
      (node (ref "L13") (pin "42") (pinfunction "3_VCC_42") (pintype "power_in"))
      (node (ref "L13") (pin "7") (pinfunction "4_VCC_7") (pintype "power_in"))
      (node (ref "L14") (pin "18") (pinfunction "1_VCC_18") (pintype "power_in"))
      (node (ref "L14") (pin "31") (pinfunction "2_VCC_31") (pintype "power_in"))
      (node (ref "L14") (pin "42") (pinfunction "3_VCC_42") (pintype "power_in"))
      (node (ref "L14") (pin "7") (pinfunction "4_VCC_7") (pintype "power_in"))
      (node (ref "L15") (pin "18") (pinfunction "1_VCC_18") (pintype "power_in"))
      (node (ref "L15") (pin "31") (pinfunction "2_VCC_31") (pintype "power_in"))
      (node (ref "L15") (pin "42") (pinfunction "3_VCC_42") (pintype "power_in"))
      (node (ref "L15") (pin "7") (pinfunction "4_VCC_7") (pintype "power_in"))
      (node (ref "L16") (pin "18") (pinfunction "1_VCC_18") (pintype "power_in"))
      (node (ref "L16") (pin "31") (pinfunction "2_VCC_31") (pintype "power_in"))
      (node (ref "L16") (pin "42") (pinfunction "3_VCC_42") (pintype "power_in"))
      (node (ref "L16") (pin "7") (pinfunction "4_VCC_7") (pintype "power_in"))
      (node (ref "L17") (pin "18") (pinfunction "1_VCC_18") (pintype "power_in"))
      (node (ref "L17") (pin "31") (pinfunction "2_VCC_31") (pintype "power_in"))
      (node (ref "L17") (pin "42") (pinfunction "3_VCC_42") (pintype "power_in"))
      (node (ref "L17") (pin "7") (pinfunction "4_VCC_7") (pintype "power_in"))
      (node (ref "L18") (pin "18") (pinfunction "1_VCC_18") (pintype "power_in"))
      (node (ref "L18") (pin "31") (pinfunction "2_VCC_31") (pintype "power_in"))
      (node (ref "L18") (pin "42") (pinfunction "3_VCC_42") (pintype "power_in"))
      (node (ref "L18") (pin "7") (pinfunction "4_VCC_7") (pintype "power_in"))
      (node (ref "L19") (pin "18") (pinfunction "1_VCC_18") (pintype "power_in"))
      (node (ref "L19") (pin "31") (pinfunction "2_VCC_31") (pintype "power_in"))
      (node (ref "L19") (pin "42") (pinfunction "3_VCC_42") (pintype "power_in"))
      (node (ref "L19") (pin "7") (pinfunction "4_VCC_7") (pintype "power_in"))
      (node (ref "L2") (pin "18") (pinfunction "1_VCC_18") (pintype "power_in"))
      (node (ref "L2") (pin "31") (pinfunction "2_VCC_31") (pintype "power_in"))
      (node (ref "L2") (pin "42") (pinfunction "3_VCC_42") (pintype "power_in"))
      (node (ref "L2") (pin "7") (pinfunction "4_VCC_7") (pintype "power_in"))
      (node (ref "L20") (pin "18") (pinfunction "1_VCC_18") (pintype "power_in"))
      (node (ref "L20") (pin "31") (pinfunction "2_VCC_31") (pintype "power_in"))
      (node (ref "L20") (pin "42") (pinfunction "3_VCC_42") (pintype "power_in"))
      (node (ref "L20") (pin "7") (pinfunction "4_VCC_7") (pintype "power_in"))
      (node (ref "L21") (pin "18") (pinfunction "1_VCC_18") (pintype "power_in"))
      (node (ref "L21") (pin "31") (pinfunction "2_VCC_31") (pintype "power_in"))
      (node (ref "L21") (pin "42") (pinfunction "3_VCC_42") (pintype "power_in"))
      (node (ref "L21") (pin "7") (pinfunction "4_VCC_7") (pintype "power_in"))
      (node (ref "L22") (pin "18") (pinfunction "1_VCC_18") (pintype "power_in"))
      (node (ref "L22") (pin "31") (pinfunction "2_VCC_31") (pintype "power_in"))
      (node (ref "L22") (pin "42") (pinfunction "3_VCC_42") (pintype "power_in"))
      (node (ref "L22") (pin "7") (pinfunction "4_VCC_7") (pintype "power_in"))
      (node (ref "L23") (pin "18") (pinfunction "1_VCC_18") (pintype "power_in"))
      (node (ref "L23") (pin "31") (pinfunction "2_VCC_31") (pintype "power_in"))
      (node (ref "L23") (pin "42") (pinfunction "3_VCC_42") (pintype "power_in"))
      (node (ref "L23") (pin "7") (pinfunction "4_VCC_7") (pintype "power_in"))
      (node (ref "L24") (pin "18") (pinfunction "1_VCC_18") (pintype "power_in"))
      (node (ref "L24") (pin "31") (pinfunction "2_VCC_31") (pintype "power_in"))
      (node (ref "L24") (pin "42") (pinfunction "3_VCC_42") (pintype "power_in"))
      (node (ref "L24") (pin "7") (pinfunction "4_VCC_7") (pintype "power_in"))
      (node (ref "L25") (pin "18") (pinfunction "1_VCC_18") (pintype "power_in"))
      (node (ref "L25") (pin "31") (pinfunction "2_VCC_31") (pintype "power_in"))
      (node (ref "L25") (pin "42") (pinfunction "3_VCC_42") (pintype "power_in"))
      (node (ref "L25") (pin "7") (pinfunction "4_VCC_7") (pintype "power_in"))
      (node (ref "L3") (pin "18") (pinfunction "1_VCC_18") (pintype "power_in"))
      (node (ref "L3") (pin "31") (pinfunction "2_VCC_31") (pintype "power_in"))
      (node (ref "L3") (pin "42") (pinfunction "3_VCC_42") (pintype "power_in"))
      (node (ref "L3") (pin "7") (pinfunction "4_VCC_7") (pintype "power_in"))
      (node (ref "L4") (pin "18") (pinfunction "1_VCC_18") (pintype "power_in"))
      (node (ref "L4") (pin "31") (pinfunction "2_VCC_31") (pintype "power_in"))
      (node (ref "L4") (pin "42") (pinfunction "3_VCC_42") (pintype "power_in"))
      (node (ref "L4") (pin "7") (pinfunction "4_VCC_7") (pintype "power_in"))
      (node (ref "L5") (pin "18") (pinfunction "1_VCC_18") (pintype "power_in"))
      (node (ref "L5") (pin "31") (pinfunction "2_VCC_31") (pintype "power_in"))
      (node (ref "L5") (pin "42") (pinfunction "3_VCC_42") (pintype "power_in"))
      (node (ref "L5") (pin "7") (pinfunction "4_VCC_7") (pintype "power_in"))
      (node (ref "L6") (pin "18") (pinfunction "1_VCC_18") (pintype "power_in"))
      (node (ref "L6") (pin "31") (pinfunction "2_VCC_31") (pintype "power_in"))
      (node (ref "L6") (pin "42") (pinfunction "3_VCC_42") (pintype "power_in"))
      (node (ref "L6") (pin "7") (pinfunction "4_VCC_7") (pintype "power_in"))
      (node (ref "L7") (pin "18") (pinfunction "1_VCC_18") (pintype "power_in"))
      (node (ref "L7") (pin "31") (pinfunction "2_VCC_31") (pintype "power_in"))
      (node (ref "L7") (pin "42") (pinfunction "3_VCC_42") (pintype "power_in"))
      (node (ref "L7") (pin "7") (pinfunction "4_VCC_7") (pintype "power_in"))
      (node (ref "L8") (pin "18") (pinfunction "1_VCC_18") (pintype "power_in"))
      (node (ref "L8") (pin "31") (pinfunction "2_VCC_31") (pintype "power_in"))
      (node (ref "L8") (pin "42") (pinfunction "3_VCC_42") (pintype "power_in"))
      (node (ref "L8") (pin "7") (pinfunction "4_VCC_7") (pintype "power_in"))
      (node (ref "L9") (pin "18") (pinfunction "1_VCC_18") (pintype "power_in"))
      (node (ref "L9") (pin "31") (pinfunction "2_VCC_31") (pintype "power_in"))
      (node (ref "L9") (pin "42") (pinfunction "3_VCC_42") (pintype "power_in"))
      (node (ref "L9") (pin "7") (pinfunction "4_VCC_7") (pintype "power_in"))
      (node (ref "POWER_JP1") (pin "2") (pinfunction "2_2") (pintype "passive"))
      (node (ref "POWER_JP2") (pin "2") (pinfunction "2_2") (pintype "passive"))
      (node (ref "POWER_JP3") (pin "2") (pinfunction "2_2") (pintype "passive"))
      (node (ref "POWER_JP4") (pin "2") (pinfunction "2_2") (pintype "passive"))
    )
    (net (code "629") (name "/VCC_SR") (class "Default")
      (node (ref "POWER_JP1") (pin "1") (pinfunction "1_1") (pintype "passive"))
      (node (ref "POWER_JP2") (pin "1") (pinfunction "1_1") (pintype "passive"))
      (node (ref "POWER_JP3") (pin "1") (pinfunction "1_1") (pintype "passive"))
      (node (ref "POWER_JP4") (pin "1") (pinfunction "1_1") (pintype "passive"))
      (node (ref "SR1") (pin "10") (pinfunction "~{SCLR}_10") (pintype "input"))
      (node (ref "SR1") (pin "16") (pinfunction "VCC_16") (pintype "power_in"))
      (node (ref "SR10") (pin "10") (pinfunction "~{SCLR}_10") (pintype "input"))
      (node (ref "SR10") (pin "16") (pinfunction "VCC_16") (pintype "power_in"))
      (node (ref "SR11") (pin "10") (pinfunction "~{SCLR}_10") (pintype "input"))
      (node (ref "SR11") (pin "16") (pinfunction "VCC_16") (pintype "power_in"))
      (node (ref "SR12") (pin "10") (pinfunction "~{SCLR}_10") (pintype "input"))
      (node (ref "SR12") (pin "16") (pinfunction "VCC_16") (pintype "power_in"))
      (node (ref "SR13") (pin "10") (pinfunction "~{SCLR}_10") (pintype "input"))
      (node (ref "SR13") (pin "16") (pinfunction "VCC_16") (pintype "power_in"))
      (node (ref "SR14") (pin "10") (pinfunction "~{SCLR}_10") (pintype "input"))
      (node (ref "SR14") (pin "16") (pinfunction "VCC_16") (pintype "power_in"))
      (node (ref "SR15") (pin "10") (pinfunction "~{SCLR}_10") (pintype "input"))
      (node (ref "SR15") (pin "16") (pinfunction "VCC_16") (pintype "power_in"))
      (node (ref "SR16") (pin "10") (pinfunction "~{SCLR}_10") (pintype "input"))
      (node (ref "SR16") (pin "16") (pinfunction "VCC_16") (pintype "power_in"))
      (node (ref "SR17") (pin "10") (pinfunction "~{SCLR}_10") (pintype "input"))
      (node (ref "SR17") (pin "16") (pinfunction "VCC_16") (pintype "power_in"))
      (node (ref "SR18") (pin "10") (pinfunction "~{SCLR}_10") (pintype "input"))
      (node (ref "SR18") (pin "16") (pinfunction "VCC_16") (pintype "power_in"))
      (node (ref "SR19") (pin "10") (pinfunction "~{SCLR}_10") (pintype "input"))
      (node (ref "SR19") (pin "16") (pinfunction "VCC_16") (pintype "power_in"))
      (node (ref "SR2") (pin "10") (pinfunction "~{SCLR}_10") (pintype "input"))
      (node (ref "SR2") (pin "16") (pinfunction "VCC_16") (pintype "power_in"))
      (node (ref "SR20") (pin "10") (pinfunction "~{SCLR}_10") (pintype "input"))
      (node (ref "SR20") (pin "16") (pinfunction "VCC_16") (pintype "power_in"))
      (node (ref "SR21") (pin "10") (pinfunction "~{SCLR}_10") (pintype "input"))
      (node (ref "SR21") (pin "16") (pinfunction "VCC_16") (pintype "power_in"))
      (node (ref "SR22") (pin "10") (pinfunction "~{SCLR}_10") (pintype "input"))
      (node (ref "SR22") (pin "16") (pinfunction "VCC_16") (pintype "power_in"))
      (node (ref "SR23") (pin "10") (pinfunction "~{SCLR}_10") (pintype "input"))
      (node (ref "SR23") (pin "16") (pinfunction "VCC_16") (pintype "power_in"))
      (node (ref "SR24") (pin "10") (pinfunction "~{SCLR}_10") (pintype "input"))
      (node (ref "SR24") (pin "16") (pinfunction "VCC_16") (pintype "power_in"))
      (node (ref "SR25") (pin "10") (pinfunction "~{SCLR}_10") (pintype "input"))
      (node (ref "SR25") (pin "16") (pinfunction "VCC_16") (pintype "power_in"))
      (node (ref "SR3") (pin "10") (pinfunction "~{SCLR}_10") (pintype "input"))
      (node (ref "SR3") (pin "16") (pinfunction "VCC_16") (pintype "power_in"))
      (node (ref "SR4") (pin "10") (pinfunction "~{SCLR}_10") (pintype "input"))
      (node (ref "SR4") (pin "16") (pinfunction "VCC_16") (pintype "power_in"))
      (node (ref "SR5") (pin "10") (pinfunction "~{SCLR}_10") (pintype "input"))
      (node (ref "SR5") (pin "16") (pinfunction "VCC_16") (pintype "power_in"))
      (node (ref "SR6") (pin "10") (pinfunction "~{SCLR}_10") (pintype "input"))
      (node (ref "SR6") (pin "16") (pinfunction "VCC_16") (pintype "power_in"))
      (node (ref "SR7") (pin "10") (pinfunction "~{SCLR}_10") (pintype "input"))
      (node (ref "SR7") (pin "16") (pinfunction "VCC_16") (pintype "power_in"))
      (node (ref "SR8") (pin "10") (pinfunction "~{SCLR}_10") (pintype "input"))
      (node (ref "SR8") (pin "16") (pinfunction "VCC_16") (pintype "power_in"))
      (node (ref "SR9") (pin "10") (pinfunction "~{SCLR}_10") (pintype "input"))
      (node (ref "SR9") (pin "16") (pinfunction "VCC_16") (pintype "power_in"))
    )
    (net (code "630") (name "Net-(SR1-QH')") (class "Default")
      (node (ref "SR1") (pin "9") (pinfunction "QH'_9") (pintype "tri_state"))
      (node (ref "SR2") (pin "14") (pinfunction "SER_14") (pintype "input"))
    )
    (net (code "631") (name "Net-(SR2-QH')") (class "Default")
      (node (ref "SR2") (pin "9") (pinfunction "QH'_9") (pintype "tri_state"))
      (node (ref "SR3") (pin "14") (pinfunction "SER_14") (pintype "input"))
    )
    (net (code "632") (name "Net-(SR3-QH')") (class "Default")
      (node (ref "SR3") (pin "9") (pinfunction "QH'_9") (pintype "tri_state"))
      (node (ref "SR4") (pin "14") (pinfunction "SER_14") (pintype "input"))
    )
    (net (code "633") (name "Net-(SR4-QH')") (class "Default")
      (node (ref "SR4") (pin "9") (pinfunction "QH'_9") (pintype "tri_state"))
      (node (ref "SR5") (pin "14") (pinfunction "SER_14") (pintype "input"))
    )
    (net (code "634") (name "Net-(SR6-QH')") (class "Default")
      (node (ref "SR6") (pin "9") (pinfunction "QH'_9") (pintype "tri_state"))
      (node (ref "SR7") (pin "14") (pinfunction "SER_14") (pintype "input"))
    )
    (net (code "635") (name "Net-(SR7-QH')") (class "Default")
      (node (ref "SR7") (pin "9") (pinfunction "QH'_9") (pintype "tri_state"))
      (node (ref "SR8") (pin "14") (pinfunction "SER_14") (pintype "input"))
    )
    (net (code "636") (name "Net-(SR8-QH')") (class "Default")
      (node (ref "SR8") (pin "9") (pinfunction "QH'_9") (pintype "tri_state"))
      (node (ref "SR9") (pin "14") (pinfunction "SER_14") (pintype "input"))
    )
    (net (code "637") (name "Net-(SR10-SER)") (class "Default")
      (node (ref "SR10") (pin "14") (pinfunction "SER_14") (pintype "input"))
      (node (ref "SR9") (pin "9") (pinfunction "QH'_9") (pintype "tri_state"))
    )
    (net (code "638") (name "Net-(SR11-QH')") (class "Default")
      (node (ref "SR11") (pin "9") (pinfunction "QH'_9") (pintype "tri_state"))
      (node (ref "SR12") (pin "14") (pinfunction "SER_14") (pintype "input"))
    )
    (net (code "639") (name "Net-(SR12-QH')") (class "Default")
      (node (ref "SR12") (pin "9") (pinfunction "QH'_9") (pintype "tri_state"))
      (node (ref "SR13") (pin "14") (pinfunction "SER_14") (pintype "input"))
    )
    (net (code "640") (name "Net-(SR13-QH')") (class "Default")
      (node (ref "SR13") (pin "9") (pinfunction "QH'_9") (pintype "tri_state"))
      (node (ref "SR14") (pin "14") (pinfunction "SER_14") (pintype "input"))
    )
    (net (code "641") (name "Net-(SR14-QH')") (class "Default")
      (node (ref "SR14") (pin "9") (pinfunction "QH'_9") (pintype "tri_state"))
      (node (ref "SR15") (pin "14") (pinfunction "SER_14") (pintype "input"))
    )
    (net (code "642") (name "Net-(SR16-QH')") (class "Default")
      (node (ref "SR16") (pin "9") (pinfunction "QH'_9") (pintype "tri_state"))
      (node (ref "SR17") (pin "14") (pinfunction "SER_14") (pintype "input"))
    )
    (net (code "643") (name "Net-(SR17-QH')") (class "Default")
      (node (ref "SR17") (pin "9") (pinfunction "QH'_9") (pintype "tri_state"))
      (node (ref "SR18") (pin "14") (pinfunction "SER_14") (pintype "input"))
    )
    (net (code "644") (name "Net-(SR18-QH')") (class "Default")
      (node (ref "SR18") (pin "9") (pinfunction "QH'_9") (pintype "tri_state"))
      (node (ref "SR19") (pin "14") (pinfunction "SER_14") (pintype "input"))
    )
    (net (code "645") (name "Net-(SR19-QH')") (class "Default")
      (node (ref "SR19") (pin "9") (pinfunction "QH'_9") (pintype "tri_state"))
      (node (ref "SR20") (pin "14") (pinfunction "SER_14") (pintype "input"))
    )
    (net (code "646") (name "Net-(SR21-QH')") (class "Default")
      (node (ref "SR21") (pin "9") (pinfunction "QH'_9") (pintype "tri_state"))
      (node (ref "SR22") (pin "14") (pinfunction "SER_14") (pintype "input"))
    )
    (net (code "647") (name "Net-(SR22-QH')") (class "Default")
      (node (ref "SR22") (pin "9") (pinfunction "QH'_9") (pintype "tri_state"))
      (node (ref "SR23") (pin "14") (pinfunction "SER_14") (pintype "input"))
    )
    (net (code "648") (name "Net-(SR23-QH')") (class "Default")
      (node (ref "SR23") (pin "9") (pinfunction "QH'_9") (pintype "tri_state"))
      (node (ref "SR24") (pin "14") (pinfunction "SER_14") (pintype "input"))
    )
    (net (code "649") (name "Net-(SR24-QH')") (class "Default")
      (node (ref "SR24") (pin "9") (pinfunction "QH'_9") (pintype "tri_state"))
      (node (ref "SR25") (pin "14") (pinfunction "SER_14") (pintype "input"))
    )
  )
)
